# UCirKitBreadboardTop2.net
KiCad netlist of a schematic drawn in EAGLE
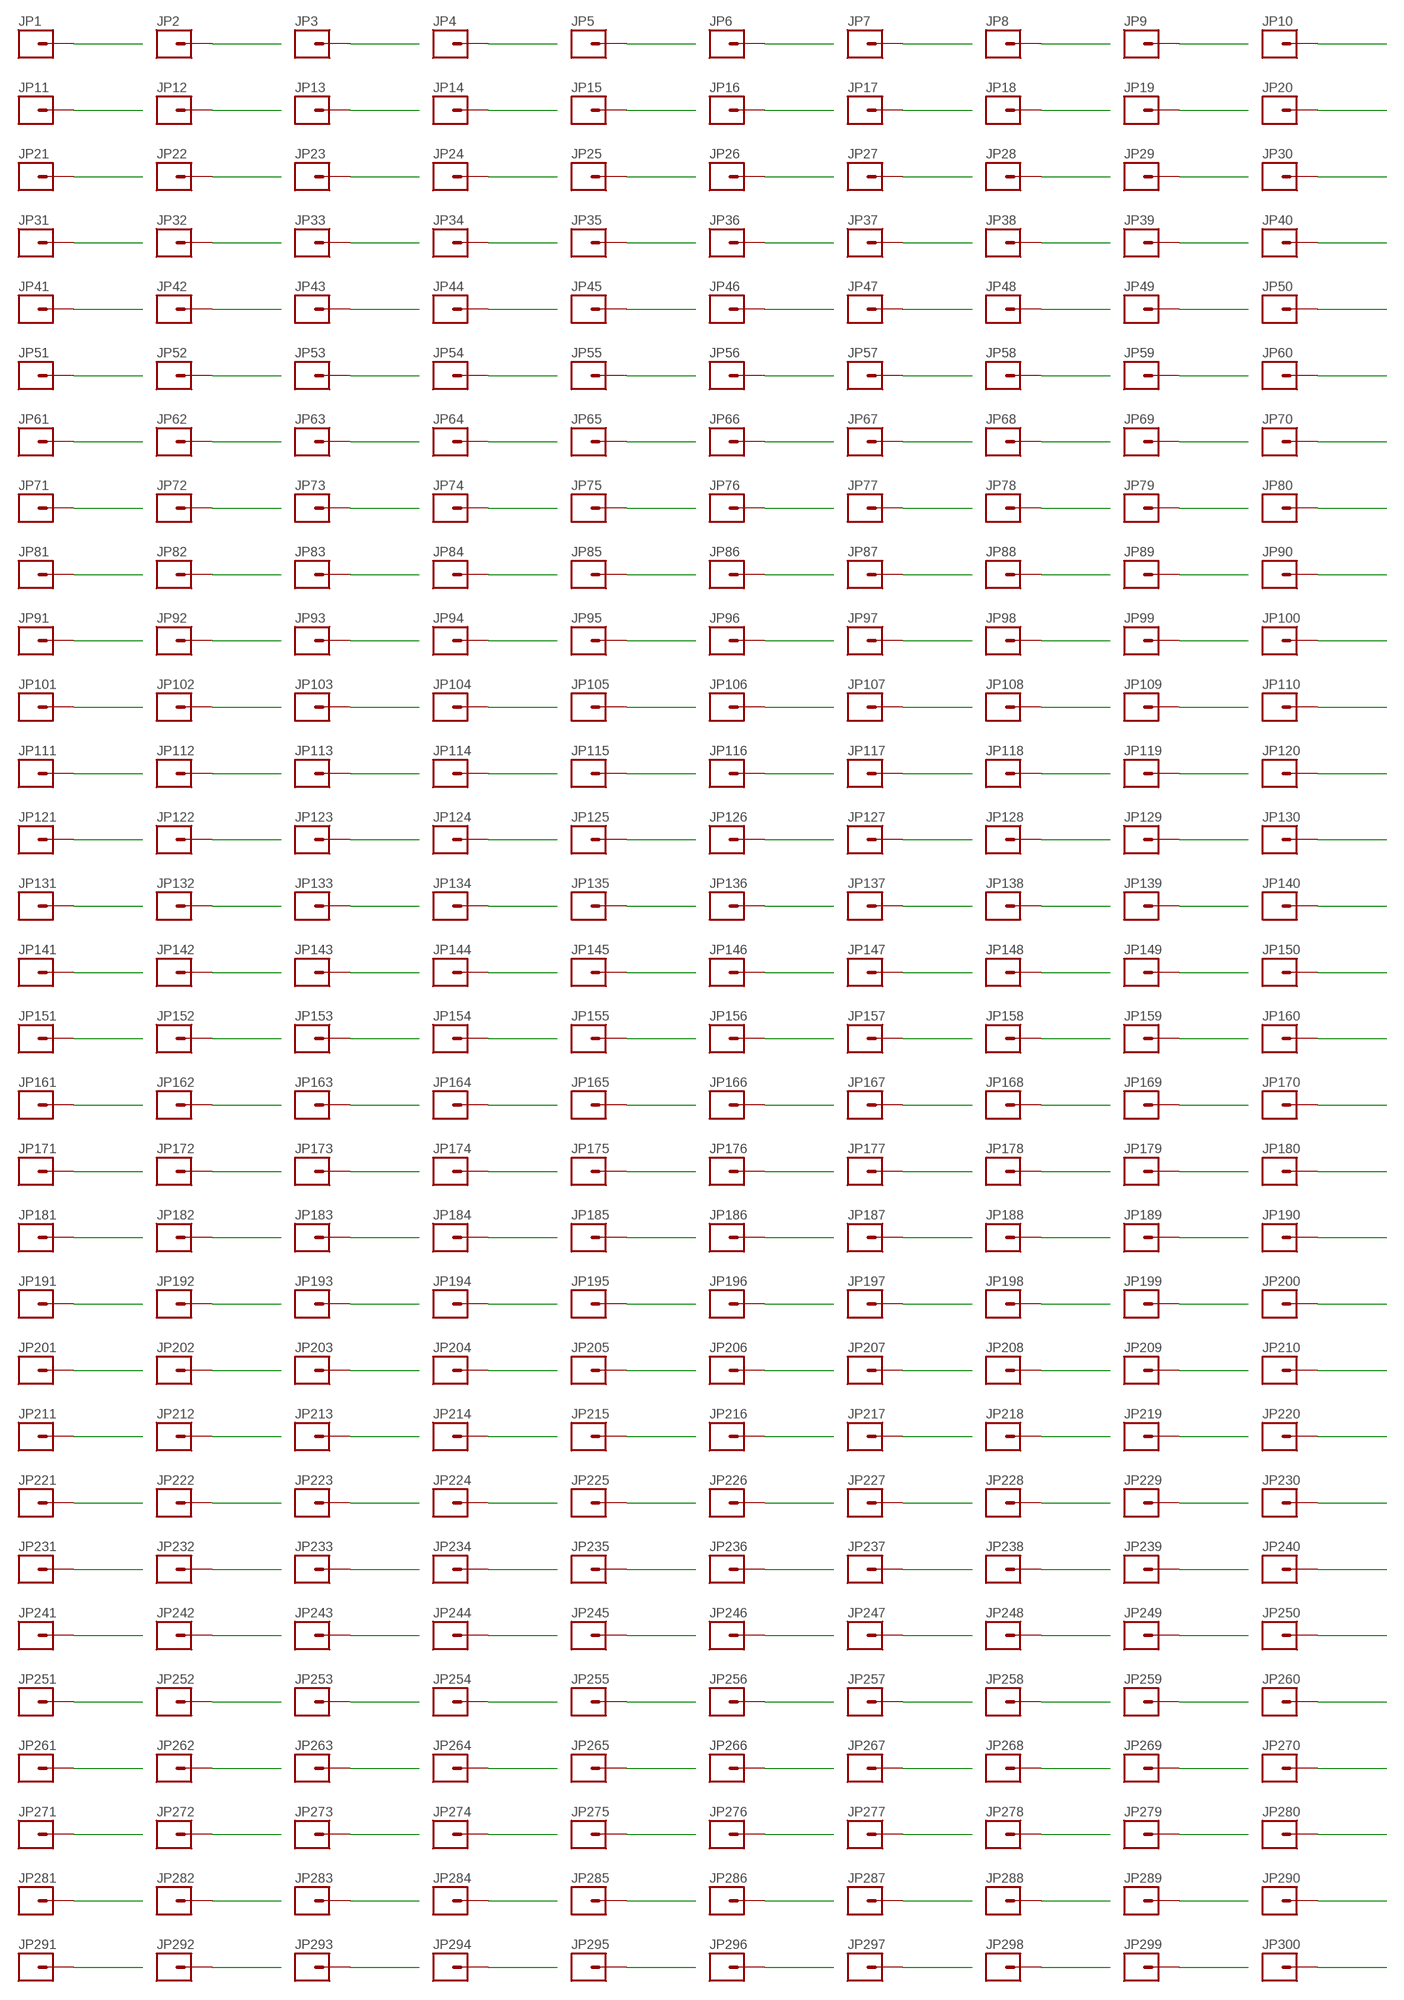
[diagram p0: schematic, sheet 1, part 1 of 2]
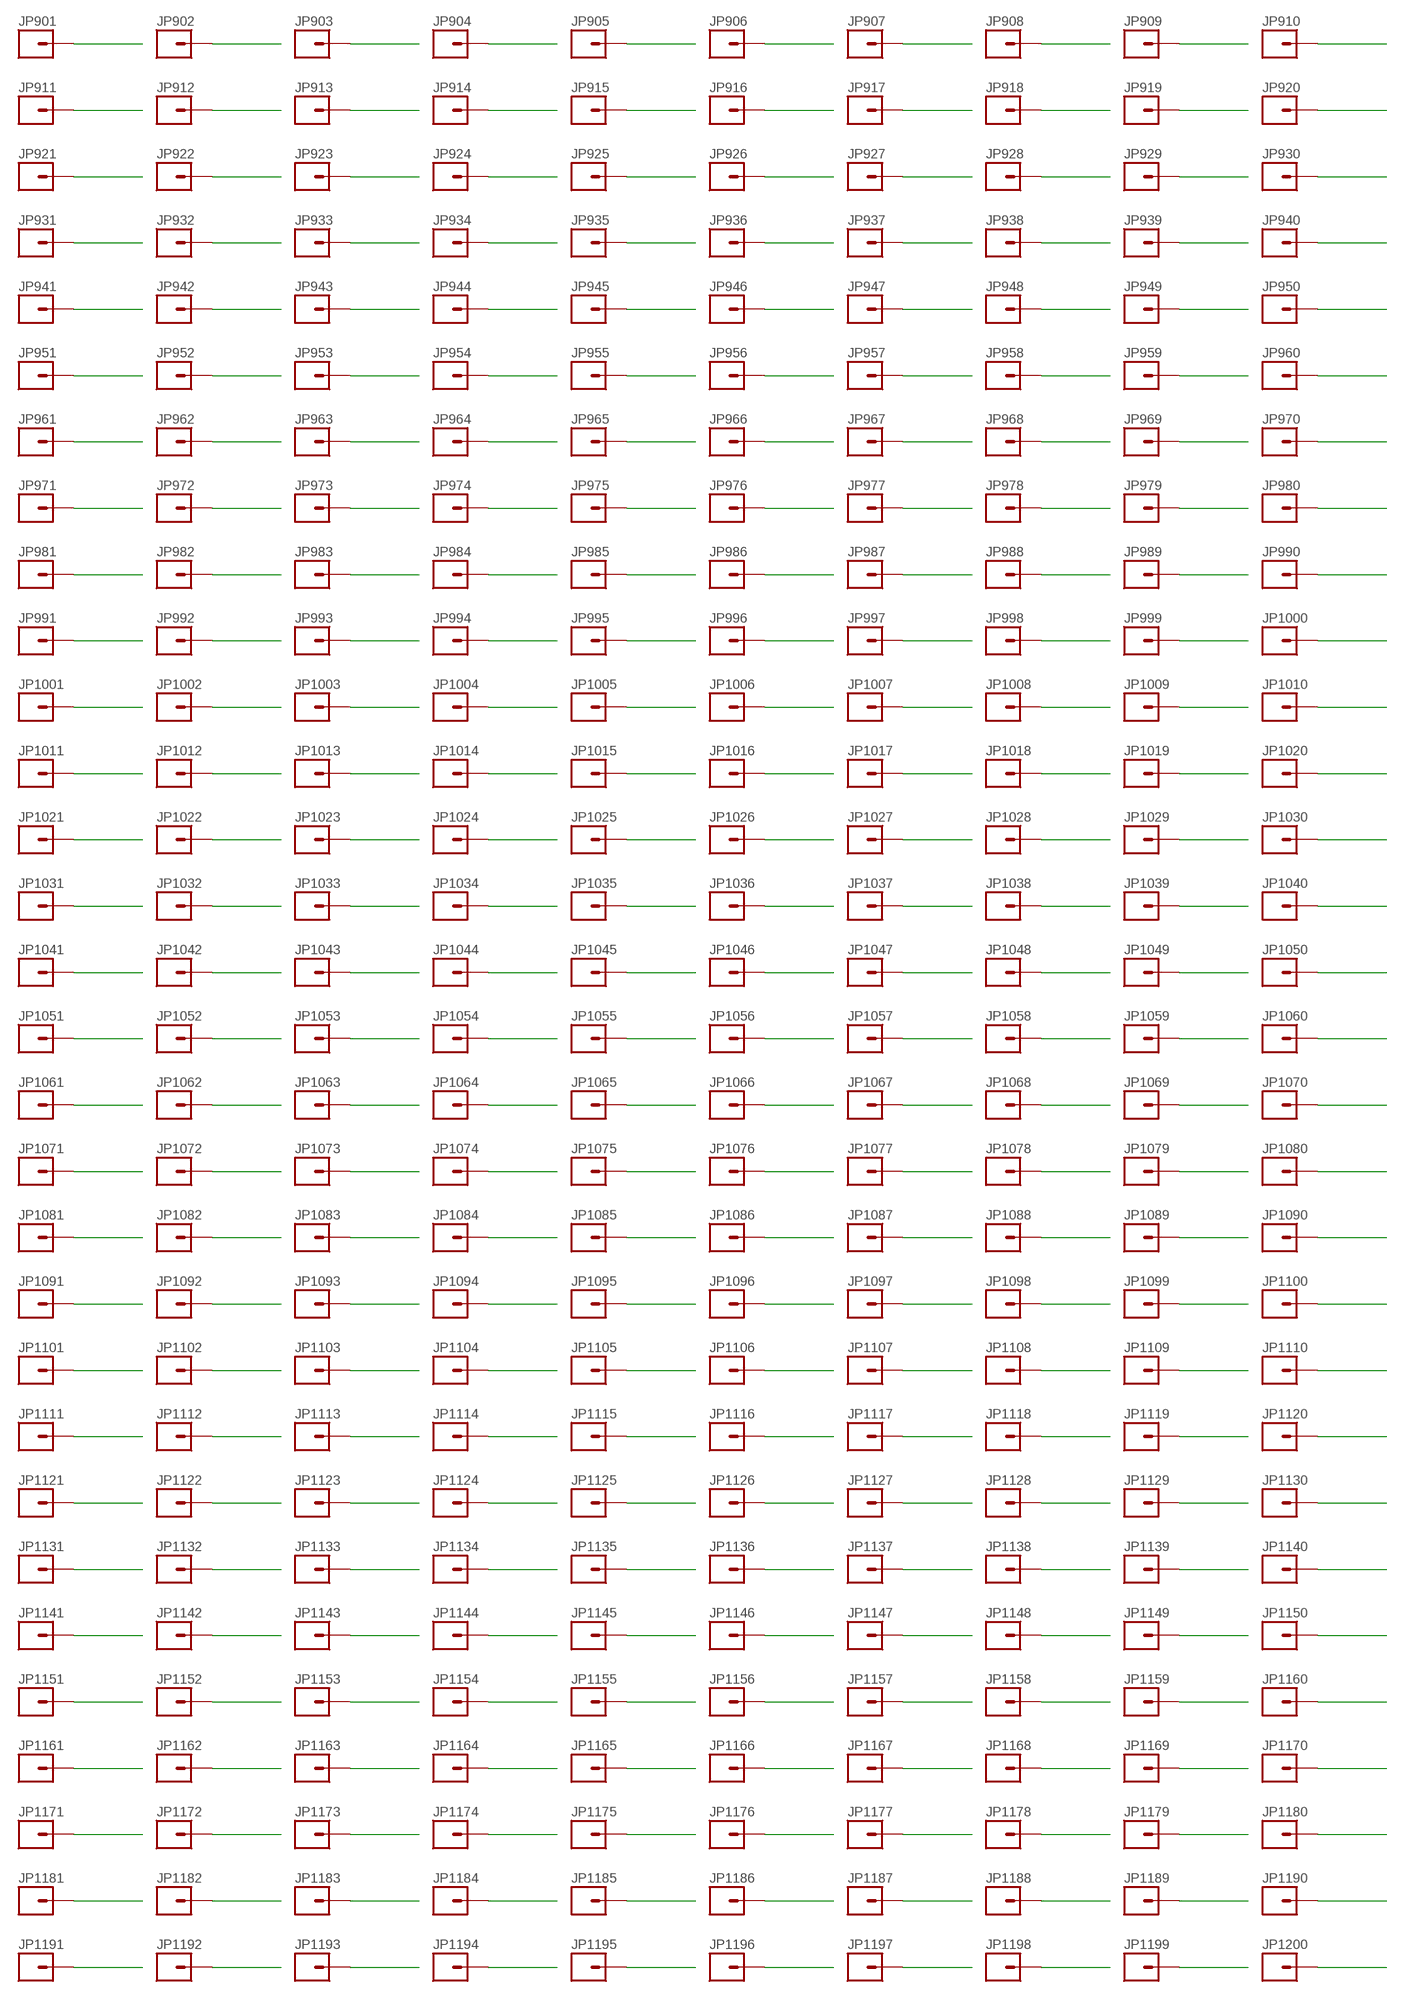
[diagram p1: schematic, sheet 1, part 2 of 2]

(export (version "E")
  (design (tool "Eeschema 10.0.6"))
  (components
    (comp (ref "JP1")
      (value "M01PTH_WITHOUT_TEXT")
      (footprint "eagle-import:1X01_WITHOUT_TEXT")
      (libsource (lib "eagle-import") (part "M01PTH_WITHOUT_TEXT"))
    )
    (comp (ref "JP2")
      (value "M01PTH_WITHOUT_TEXT")
      (footprint "eagle-import:1X01_WITHOUT_TEXT")
      (libsource (lib "eagle-import") (part "M01PTH_WITHOUT_TEXT"))
    )
    (comp (ref "JP3")
      (value "M01PTH_WITHOUT_TEXT")
      (footprint "eagle-import:1X01_WITHOUT_TEXT")
      (libsource (lib "eagle-import") (part "M01PTH_WITHOUT_TEXT"))
    )
    (comp (ref "JP4")
      (value "M01PTH_WITHOUT_TEXT")
      (footprint "eagle-import:1X01_WITHOUT_TEXT")
      (libsource (lib "eagle-import") (part "M01PTH_WITHOUT_TEXT"))
    )
    (comp (ref "JP5")
      (value "M01PTH_WITHOUT_TEXT")
      (footprint "eagle-import:1X01_WITHOUT_TEXT")
      (libsource (lib "eagle-import") (part "M01PTH_WITHOUT_TEXT"))
    )
    (comp (ref "JP6")
      (value "M01PTH_WITHOUT_TEXT")
      (footprint "eagle-import:1X01_WITHOUT_TEXT")
      (libsource (lib "eagle-import") (part "M01PTH_WITHOUT_TEXT"))
    )
    (comp (ref "JP7")
      (value "M01PTH_WITHOUT_TEXT")
      (footprint "eagle-import:1X01_WITHOUT_TEXT")
      (libsource (lib "eagle-import") (part "M01PTH_WITHOUT_TEXT"))
    )
    (comp (ref "JP8")
      (value "M01PTH_WITHOUT_TEXT")
      (footprint "eagle-import:1X01_WITHOUT_TEXT")
      (libsource (lib "eagle-import") (part "M01PTH_WITHOUT_TEXT"))
    )
    (comp (ref "JP9")
      (value "M01PTH_WITHOUT_TEXT")
      (footprint "eagle-import:1X01_WITHOUT_TEXT")
      (libsource (lib "eagle-import") (part "M01PTH_WITHOUT_TEXT"))
    )
    (comp (ref "JP10")
      (value "M01PTH_WITHOUT_TEXT")
      (footprint "eagle-import:1X01_WITHOUT_TEXT")
      (libsource (lib "eagle-import") (part "M01PTH_WITHOUT_TEXT"))
    )
    (comp (ref "JP11")
      (value "M01PTH_WITHOUT_TEXT")
      (footprint "eagle-import:1X01_WITHOUT_TEXT")
      (libsource (lib "eagle-import") (part "M01PTH_WITHOUT_TEXT"))
    )
    (comp (ref "JP12")
      (value "M01PTH_WITHOUT_TEXT")
      (footprint "eagle-import:1X01_WITHOUT_TEXT")
      (libsource (lib "eagle-import") (part "M01PTH_WITHOUT_TEXT"))
    )
    (comp (ref "JP13")
      (value "M01PTH_WITHOUT_TEXT")
      (footprint "eagle-import:1X01_WITHOUT_TEXT")
      (libsource (lib "eagle-import") (part "M01PTH_WITHOUT_TEXT"))
    )
    (comp (ref "JP14")
      (value "M01PTH_WITHOUT_TEXT")
      (footprint "eagle-import:1X01_WITHOUT_TEXT")
      (libsource (lib "eagle-import") (part "M01PTH_WITHOUT_TEXT"))
    )
    (comp (ref "JP15")
      (value "M01PTH_WITHOUT_TEXT")
      (footprint "eagle-import:1X01_WITHOUT_TEXT")
      (libsource (lib "eagle-import") (part "M01PTH_WITHOUT_TEXT"))
    )
    (comp (ref "JP16")
      (value "M01PTH_WITHOUT_TEXT")
      (footprint "eagle-import:1X01_WITHOUT_TEXT")
      (libsource (lib "eagle-import") (part "M01PTH_WITHOUT_TEXT"))
    )
    (comp (ref "JP17")
      (value "M01PTH_WITHOUT_TEXT")
      (footprint "eagle-import:1X01_WITHOUT_TEXT")
      (libsource (lib "eagle-import") (part "M01PTH_WITHOUT_TEXT"))
    )
    (comp (ref "JP18")
      (value "M01PTH_WITHOUT_TEXT")
      (footprint "eagle-import:1X01_WITHOUT_TEXT")
      (libsource (lib "eagle-import") (part "M01PTH_WITHOUT_TEXT"))
    )
    (comp (ref "JP19")
      (value "M01PTH_WITHOUT_TEXT")
      (footprint "eagle-import:1X01_WITHOUT_TEXT")
      (libsource (lib "eagle-import") (part "M01PTH_WITHOUT_TEXT"))
    )
    (comp (ref "JP20")
      (value "M01PTH_WITHOUT_TEXT")
      (footprint "eagle-import:1X01_WITHOUT_TEXT")
      (libsource (lib "eagle-import") (part "M01PTH_WITHOUT_TEXT"))
    )
    (comp (ref "JP21")
      (value "M01PTH_WITHOUT_TEXT")
      (footprint "eagle-import:1X01_WITHOUT_TEXT")
      (libsource (lib "eagle-import") (part "M01PTH_WITHOUT_TEXT"))
    )
    (comp (ref "JP22")
      (value "M01PTH_WITHOUT_TEXT")
      (footprint "eagle-import:1X01_WITHOUT_TEXT")
      (libsource (lib "eagle-import") (part "M01PTH_WITHOUT_TEXT"))
    )
    (comp (ref "JP23")
      (value "M01PTH_WITHOUT_TEXT")
      (footprint "eagle-import:1X01_WITHOUT_TEXT")
      (libsource (lib "eagle-import") (part "M01PTH_WITHOUT_TEXT"))
    )
    (comp (ref "JP24")
      (value "M01PTH_WITHOUT_TEXT")
      (footprint "eagle-import:1X01_WITHOUT_TEXT")
      (libsource (lib "eagle-import") (part "M01PTH_WITHOUT_TEXT"))
    )
    (comp (ref "JP25")
      (value "M01PTH_WITHOUT_TEXT")
      (footprint "eagle-import:1X01_WITHOUT_TEXT")
      (libsource (lib "eagle-import") (part "M01PTH_WITHOUT_TEXT"))
    )
    (comp (ref "JP26")
      (value "M01PTH_WITHOUT_TEXT")
      (footprint "eagle-import:1X01_WITHOUT_TEXT")
      (libsource (lib "eagle-import") (part "M01PTH_WITHOUT_TEXT"))
    )
    (comp (ref "JP27")
      (value "M01PTH_WITHOUT_TEXT")
      (footprint "eagle-import:1X01_WITHOUT_TEXT")
      (libsource (lib "eagle-import") (part "M01PTH_WITHOUT_TEXT"))
    )
    (comp (ref "JP28")
      (value "M01PTH_WITHOUT_TEXT")
      (footprint "eagle-import:1X01_WITHOUT_TEXT")
      (libsource (lib "eagle-import") (part "M01PTH_WITHOUT_TEXT"))
    )
    (comp (ref "JP29")
      (value "M01PTH_WITHOUT_TEXT")
      (footprint "eagle-import:1X01_WITHOUT_TEXT")
      (libsource (lib "eagle-import") (part "M01PTH_WITHOUT_TEXT"))
    )
    (comp (ref "JP30")
      (value "M01PTH_WITHOUT_TEXT")
      (footprint "eagle-import:1X01_WITHOUT_TEXT")
      (libsource (lib "eagle-import") (part "M01PTH_WITHOUT_TEXT"))
    )
    (comp (ref "JP31")
      (value "M01PTH_WITHOUT_TEXT")
      (footprint "eagle-import:1X01_WITHOUT_TEXT")
      (libsource (lib "eagle-import") (part "M01PTH_WITHOUT_TEXT"))
    )
    (comp (ref "JP32")
      (value "M01PTH_WITHOUT_TEXT")
      (footprint "eagle-import:1X01_WITHOUT_TEXT")
      (libsource (lib "eagle-import") (part "M01PTH_WITHOUT_TEXT"))
    )
    (comp (ref "JP33")
      (value "M01PTH_WITHOUT_TEXT")
      (footprint "eagle-import:1X01_WITHOUT_TEXT")
      (libsource (lib "eagle-import") (part "M01PTH_WITHOUT_TEXT"))
    )
    (comp (ref "JP34")
      (value "M01PTH_WITHOUT_TEXT")
      (footprint "eagle-import:1X01_WITHOUT_TEXT")
      (libsource (lib "eagle-import") (part "M01PTH_WITHOUT_TEXT"))
    )
    (comp (ref "JP35")
      (value "M01PTH_WITHOUT_TEXT")
      (footprint "eagle-import:1X01_WITHOUT_TEXT")
      (libsource (lib "eagle-import") (part "M01PTH_WITHOUT_TEXT"))
    )
    (comp (ref "JP36")
      (value "M01PTH_WITHOUT_TEXT")
      (footprint "eagle-import:1X01_WITHOUT_TEXT")
      (libsource (lib "eagle-import") (part "M01PTH_WITHOUT_TEXT"))
    )
    (comp (ref "JP37")
      (value "M01PTH_WITHOUT_TEXT")
      (footprint "eagle-import:1X01_WITHOUT_TEXT")
      (libsource (lib "eagle-import") (part "M01PTH_WITHOUT_TEXT"))
    )
    (comp (ref "JP38")
      (value "M01PTH_WITHOUT_TEXT")
      (footprint "eagle-import:1X01_WITHOUT_TEXT")
      (libsource (lib "eagle-import") (part "M01PTH_WITHOUT_TEXT"))
    )
    (comp (ref "JP39")
      (value "M01PTH_WITHOUT_TEXT")
      (footprint "eagle-import:1X01_WITHOUT_TEXT")
      (libsource (lib "eagle-import") (part "M01PTH_WITHOUT_TEXT"))
    )
    (comp (ref "JP40")
      (value "M01PTH_WITHOUT_TEXT")
      (footprint "eagle-import:1X01_WITHOUT_TEXT")
      (libsource (lib "eagle-import") (part "M01PTH_WITHOUT_TEXT"))
    )
    (comp (ref "JP41")
      (value "M01PTH_WITHOUT_TEXT")
      (footprint "eagle-import:1X01_WITHOUT_TEXT")
      (libsource (lib "eagle-import") (part "M01PTH_WITHOUT_TEXT"))
    )
    (comp (ref "JP42")
      (value "M01PTH_WITHOUT_TEXT")
      (footprint "eagle-import:1X01_WITHOUT_TEXT")
      (libsource (lib "eagle-import") (part "M01PTH_WITHOUT_TEXT"))
    )
    (comp (ref "JP43")
      (value "M01PTH_WITHOUT_TEXT")
      (footprint "eagle-import:1X01_WITHOUT_TEXT")
      (libsource (lib "eagle-import") (part "M01PTH_WITHOUT_TEXT"))
    )
    (comp (ref "JP44")
      (value "M01PTH_WITHOUT_TEXT")
      (footprint "eagle-import:1X01_WITHOUT_TEXT")
      (libsource (lib "eagle-import") (part "M01PTH_WITHOUT_TEXT"))
    )
    (comp (ref "JP45")
      (value "M01PTH_WITHOUT_TEXT")
      (footprint "eagle-import:1X01_WITHOUT_TEXT")
      (libsource (lib "eagle-import") (part "M01PTH_WITHOUT_TEXT"))
    )
    (comp (ref "JP46")
      (value "M01PTH_WITHOUT_TEXT")
      (footprint "eagle-import:1X01_WITHOUT_TEXT")
      (libsource (lib "eagle-import") (part "M01PTH_WITHOUT_TEXT"))
    )
    (comp (ref "JP47")
      (value "M01PTH_WITHOUT_TEXT")
      (footprint "eagle-import:1X01_WITHOUT_TEXT")
      (libsource (lib "eagle-import") (part "M01PTH_WITHOUT_TEXT"))
    )
    (comp (ref "JP48")
      (value "M01PTH_WITHOUT_TEXT")
      (footprint "eagle-import:1X01_WITHOUT_TEXT")
      (libsource (lib "eagle-import") (part "M01PTH_WITHOUT_TEXT"))
    )
    (comp (ref "JP49")
      (value "M01PTH_WITHOUT_TEXT")
      (footprint "eagle-import:1X01_WITHOUT_TEXT")
      (libsource (lib "eagle-import") (part "M01PTH_WITHOUT_TEXT"))
    )
    (comp (ref "JP50")
      (value "M01PTH_WITHOUT_TEXT")
      (footprint "eagle-import:1X01_WITHOUT_TEXT")
      (libsource (lib "eagle-import") (part "M01PTH_WITHOUT_TEXT"))
    )
    (comp (ref "JP51")
      (value "M01PTH_WITHOUT_TEXT")
      (footprint "eagle-import:1X01_WITHOUT_TEXT")
      (libsource (lib "eagle-import") (part "M01PTH_WITHOUT_TEXT"))
    )
    (comp (ref "JP52")
      (value "M01PTH_WITHOUT_TEXT")
      (footprint "eagle-import:1X01_WITHOUT_TEXT")
      (libsource (lib "eagle-import") (part "M01PTH_WITHOUT_TEXT"))
    )
    (comp (ref "JP53")
      (value "M01PTH_WITHOUT_TEXT")
      (footprint "eagle-import:1X01_WITHOUT_TEXT")
      (libsource (lib "eagle-import") (part "M01PTH_WITHOUT_TEXT"))
    )
    (comp (ref "JP54")
      (value "M01PTH_WITHOUT_TEXT")
      (footprint "eagle-import:1X01_WITHOUT_TEXT")
      (libsource (lib "eagle-import") (part "M01PTH_WITHOUT_TEXT"))
    )
    (comp (ref "JP55")
      (value "M01PTH_WITHOUT_TEXT")
      (footprint "eagle-import:1X01_WITHOUT_TEXT")
      (libsource (lib "eagle-import") (part "M01PTH_WITHOUT_TEXT"))
    )
    (comp (ref "JP56")
      (value "M01PTH_WITHOUT_TEXT")
      (footprint "eagle-import:1X01_WITHOUT_TEXT")
      (libsource (lib "eagle-import") (part "M01PTH_WITHOUT_TEXT"))
    )
    (comp (ref "JP57")
      (value "M01PTH_WITHOUT_TEXT")
      (footprint "eagle-import:1X01_WITHOUT_TEXT")
      (libsource (lib "eagle-import") (part "M01PTH_WITHOUT_TEXT"))
    )
    (comp (ref "JP58")
      (value "M01PTH_WITHOUT_TEXT")
      (footprint "eagle-import:1X01_WITHOUT_TEXT")
      (libsource (lib "eagle-import") (part "M01PTH_WITHOUT_TEXT"))
    )
    (comp (ref "JP59")
      (value "M01PTH_WITHOUT_TEXT")
      (footprint "eagle-import:1X01_WITHOUT_TEXT")
      (libsource (lib "eagle-import") (part "M01PTH_WITHOUT_TEXT"))
    )
    (comp (ref "JP60")
      (value "M01PTH_WITHOUT_TEXT")
      (footprint "eagle-import:1X01_WITHOUT_TEXT")
      (libsource (lib "eagle-import") (part "M01PTH_WITHOUT_TEXT"))
    )
    (comp (ref "JP61")
      (value "M01PTH_WITHOUT_TEXT")
      (footprint "eagle-import:1X01_WITHOUT_TEXT")
      (libsource (lib "eagle-import") (part "M01PTH_WITHOUT_TEXT"))
    )
    (comp (ref "JP62")
      (value "M01PTH_WITHOUT_TEXT")
      (footprint "eagle-import:1X01_WITHOUT_TEXT")
      (libsource (lib "eagle-import") (part "M01PTH_WITHOUT_TEXT"))
    )
    (comp (ref "JP63")
      (value "M01PTH_WITHOUT_TEXT")
      (footprint "eagle-import:1X01_WITHOUT_TEXT")
      (libsource (lib "eagle-import") (part "M01PTH_WITHOUT_TEXT"))
    )
    (comp (ref "JP64")
      (value "M01PTH_WITHOUT_TEXT")
      (footprint "eagle-import:1X01_WITHOUT_TEXT")
      (libsource (lib "eagle-import") (part "M01PTH_WITHOUT_TEXT"))
    )
    (comp (ref "JP65")
      (value "M01PTH_WITHOUT_TEXT")
      (footprint "eagle-import:1X01_WITHOUT_TEXT")
      (libsource (lib "eagle-import") (part "M01PTH_WITHOUT_TEXT"))
    )
    (comp (ref "JP66")
      (value "M01PTH_WITHOUT_TEXT")
      (footprint "eagle-import:1X01_WITHOUT_TEXT")
      (libsource (lib "eagle-import") (part "M01PTH_WITHOUT_TEXT"))
    )
    (comp (ref "JP67")
      (value "M01PTH_WITHOUT_TEXT")
      (footprint "eagle-import:1X01_WITHOUT_TEXT")
      (libsource (lib "eagle-import") (part "M01PTH_WITHOUT_TEXT"))
    )
    (comp (ref "JP68")
      (value "M01PTH_WITHOUT_TEXT")
      (footprint "eagle-import:1X01_WITHOUT_TEXT")
      (libsource (lib "eagle-import") (part "M01PTH_WITHOUT_TEXT"))
    )
    (comp (ref "JP69")
      (value "M01PTH_WITHOUT_TEXT")
      (footprint "eagle-import:1X01_WITHOUT_TEXT")
      (libsource (lib "eagle-import") (part "M01PTH_WITHOUT_TEXT"))
    )
    (comp (ref "JP70")
      (value "M01PTH_WITHOUT_TEXT")
      (footprint "eagle-import:1X01_WITHOUT_TEXT")
      (libsource (lib "eagle-import") (part "M01PTH_WITHOUT_TEXT"))
    )
    (comp (ref "JP71")
      (value "M01PTH_WITHOUT_TEXT")
      (footprint "eagle-import:1X01_WITHOUT_TEXT")
      (libsource (lib "eagle-import") (part "M01PTH_WITHOUT_TEXT"))
    )
    (comp (ref "JP72")
      (value "M01PTH_WITHOUT_TEXT")
      (footprint "eagle-import:1X01_WITHOUT_TEXT")
      (libsource (lib "eagle-import") (part "M01PTH_WITHOUT_TEXT"))
    )
    (comp (ref "JP73")
      (value "M01PTH_WITHOUT_TEXT")
      (footprint "eagle-import:1X01_WITHOUT_TEXT")
      (libsource (lib "eagle-import") (part "M01PTH_WITHOUT_TEXT"))
    )
    (comp (ref "JP74")
      (value "M01PTH_WITHOUT_TEXT")
      (footprint "eagle-import:1X01_WITHOUT_TEXT")
      (libsource (lib "eagle-import") (part "M01PTH_WITHOUT_TEXT"))
    )
    (comp (ref "JP75")
      (value "M01PTH_WITHOUT_TEXT")
      (footprint "eagle-import:1X01_WITHOUT_TEXT")
      (libsource (lib "eagle-import") (part "M01PTH_WITHOUT_TEXT"))
    )
    (comp (ref "JP76")
      (value "M01PTH_WITHOUT_TEXT")
      (footprint "eagle-import:1X01_WITHOUT_TEXT")
      (libsource (lib "eagle-import") (part "M01PTH_WITHOUT_TEXT"))
    )
    (comp (ref "JP77")
      (value "M01PTH_WITHOUT_TEXT")
      (footprint "eagle-import:1X01_WITHOUT_TEXT")
      (libsource (lib "eagle-import") (part "M01PTH_WITHOUT_TEXT"))
    )
    (comp (ref "JP78")
      (value "M01PTH_WITHOUT_TEXT")
      (footprint "eagle-import:1X01_WITHOUT_TEXT")
      (libsource (lib "eagle-import") (part "M01PTH_WITHOUT_TEXT"))
    )
    (comp (ref "JP79")
      (value "M01PTH_WITHOUT_TEXT")
      (footprint "eagle-import:1X01_WITHOUT_TEXT")
      (libsource (lib "eagle-import") (part "M01PTH_WITHOUT_TEXT"))
    )
    (comp (ref "JP80")
      (value "M01PTH_WITHOUT_TEXT")
      (footprint "eagle-import:1X01_WITHOUT_TEXT")
      (libsource (lib "eagle-import") (part "M01PTH_WITHOUT_TEXT"))
    )
    (comp (ref "JP81")
      (value "M01PTH_WITHOUT_TEXT")
      (footprint "eagle-import:1X01_WITHOUT_TEXT")
      (libsource (lib "eagle-import") (part "M01PTH_WITHOUT_TEXT"))
    )
    (comp (ref "JP82")
      (value "M01PTH_WITHOUT_TEXT")
      (footprint "eagle-import:1X01_WITHOUT_TEXT")
      (libsource (lib "eagle-import") (part "M01PTH_WITHOUT_TEXT"))
    )
    (comp (ref "JP83")
      (value "M01PTH_WITHOUT_TEXT")
      (footprint "eagle-import:1X01_WITHOUT_TEXT")
      (libsource (lib "eagle-import") (part "M01PTH_WITHOUT_TEXT"))
    )
    (comp (ref "JP84")
      (value "M01PTH_WITHOUT_TEXT")
      (footprint "eagle-import:1X01_WITHOUT_TEXT")
      (libsource (lib "eagle-import") (part "M01PTH_WITHOUT_TEXT"))
    )
    (comp (ref "JP85")
      (value "M01PTH_WITHOUT_TEXT")
      (footprint "eagle-import:1X01_WITHOUT_TEXT")
      (libsource (lib "eagle-import") (part "M01PTH_WITHOUT_TEXT"))
    )
    (comp (ref "JP86")
      (value "M01PTH_WITHOUT_TEXT")
      (footprint "eagle-import:1X01_WITHOUT_TEXT")
      (libsource (lib "eagle-import") (part "M01PTH_WITHOUT_TEXT"))
    )
    (comp (ref "JP87")
      (value "M01PTH_WITHOUT_TEXT")
      (footprint "eagle-import:1X01_WITHOUT_TEXT")
      (libsource (lib "eagle-import") (part "M01PTH_WITHOUT_TEXT"))
    )
    (comp (ref "JP88")
      (value "M01PTH_WITHOUT_TEXT")
      (footprint "eagle-import:1X01_WITHOUT_TEXT")
      (libsource (lib "eagle-import") (part "M01PTH_WITHOUT_TEXT"))
    )
    (comp (ref "JP89")
      (value "M01PTH_WITHOUT_TEXT")
      (footprint "eagle-import:1X01_WITHOUT_TEXT")
      (libsource (lib "eagle-import") (part "M01PTH_WITHOUT_TEXT"))
    )
    (comp (ref "JP90")
      (value "M01PTH_WITHOUT_TEXT")
      (footprint "eagle-import:1X01_WITHOUT_TEXT")
      (libsource (lib "eagle-import") (part "M01PTH_WITHOUT_TEXT"))
    )
    (comp (ref "JP91")
      (value "M01PTH_WITHOUT_TEXT")
      (footprint "eagle-import:1X01_WITHOUT_TEXT")
      (libsource (lib "eagle-import") (part "M01PTH_WITHOUT_TEXT"))
    )
    (comp (ref "JP92")
      (value "M01PTH_WITHOUT_TEXT")
      (footprint "eagle-import:1X01_WITHOUT_TEXT")
      (libsource (lib "eagle-import") (part "M01PTH_WITHOUT_TEXT"))
    )
    (comp (ref "JP93")
      (value "M01PTH_WITHOUT_TEXT")
      (footprint "eagle-import:1X01_WITHOUT_TEXT")
      (libsource (lib "eagle-import") (part "M01PTH_WITHOUT_TEXT"))
    )
    (comp (ref "JP94")
      (value "M01PTH_WITHOUT_TEXT")
      (footprint "eagle-import:1X01_WITHOUT_TEXT")
      (libsource (lib "eagle-import") (part "M01PTH_WITHOUT_TEXT"))
    )
    (comp (ref "JP95")
      (value "M01PTH_WITHOUT_TEXT")
      (footprint "eagle-import:1X01_WITHOUT_TEXT")
      (libsource (lib "eagle-import") (part "M01PTH_WITHOUT_TEXT"))
    )
    (comp (ref "JP96")
      (value "M01PTH_WITHOUT_TEXT")
      (footprint "eagle-import:1X01_WITHOUT_TEXT")
      (libsource (lib "eagle-import") (part "M01PTH_WITHOUT_TEXT"))
    )
    (comp (ref "JP97")
      (value "M01PTH_WITHOUT_TEXT")
      (footprint "eagle-import:1X01_WITHOUT_TEXT")
      (libsource (lib "eagle-import") (part "M01PTH_WITHOUT_TEXT"))
    )
    (comp (ref "JP98")
      (value "M01PTH_WITHOUT_TEXT")
      (footprint "eagle-import:1X01_WITHOUT_TEXT")
      (libsource (lib "eagle-import") (part "M01PTH_WITHOUT_TEXT"))
    )
    (comp (ref "JP99")
      (value "M01PTH_WITHOUT_TEXT")
      (footprint "eagle-import:1X01_WITHOUT_TEXT")
      (libsource (lib "eagle-import") (part "M01PTH_WITHOUT_TEXT"))
    )
    (comp (ref "JP100")
      (value "M01PTH_WITHOUT_TEXT")
      (footprint "eagle-import:1X01_WITHOUT_TEXT")
      (libsource (lib "eagle-import") (part "M01PTH_WITHOUT_TEXT"))
    )
    (comp (ref "JP101")
      (value "M01PTH_WITHOUT_TEXT")
      (footprint "eagle-import:1X01_WITHOUT_TEXT")
      (libsource (lib "eagle-import") (part "M01PTH_WITHOUT_TEXT"))
    )
    (comp (ref "JP102")
      (value "M01PTH_WITHOUT_TEXT")
      (footprint "eagle-import:1X01_WITHOUT_TEXT")
      (libsource (lib "eagle-import") (part "M01PTH_WITHOUT_TEXT"))
    )
    (comp (ref "JP103")
      (value "M01PTH_WITHOUT_TEXT")
      (footprint "eagle-import:1X01_WITHOUT_TEXT")
      (libsource (lib "eagle-import") (part "M01PTH_WITHOUT_TEXT"))
    )
    (comp (ref "JP104")
      (value "M01PTH_WITHOUT_TEXT")
      (footprint "eagle-import:1X01_WITHOUT_TEXT")
      (libsource (lib "eagle-import") (part "M01PTH_WITHOUT_TEXT"))
    )
    (comp (ref "JP105")
      (value "M01PTH_WITHOUT_TEXT")
      (footprint "eagle-import:1X01_WITHOUT_TEXT")
      (libsource (lib "eagle-import") (part "M01PTH_WITHOUT_TEXT"))
    )
    (comp (ref "JP106")
      (value "M01PTH_WITHOUT_TEXT")
      (footprint "eagle-import:1X01_WITHOUT_TEXT")
      (libsource (lib "eagle-import") (part "M01PTH_WITHOUT_TEXT"))
    )
    (comp (ref "JP107")
      (value "M01PTH_WITHOUT_TEXT")
      (footprint "eagle-import:1X01_WITHOUT_TEXT")
      (libsource (lib "eagle-import") (part "M01PTH_WITHOUT_TEXT"))
    )
    (comp (ref "JP108")
      (value "M01PTH_WITHOUT_TEXT")
      (footprint "eagle-import:1X01_WITHOUT_TEXT")
      (libsource (lib "eagle-import") (part "M01PTH_WITHOUT_TEXT"))
    )
    (comp (ref "JP109")
      (value "M01PTH_WITHOUT_TEXT")
      (footprint "eagle-import:1X01_WITHOUT_TEXT")
      (libsource (lib "eagle-import") (part "M01PTH_WITHOUT_TEXT"))
    )
    (comp (ref "JP110")
      (value "M01PTH_WITHOUT_TEXT")
      (footprint "eagle-import:1X01_WITHOUT_TEXT")
      (libsource (lib "eagle-import") (part "M01PTH_WITHOUT_TEXT"))
    )
    (comp (ref "JP111")
      (value "M01PTH_WITHOUT_TEXT")
      (footprint "eagle-import:1X01_WITHOUT_TEXT")
      (libsource (lib "eagle-import") (part "M01PTH_WITHOUT_TEXT"))
    )
    (comp (ref "JP112")
      (value "M01PTH_WITHOUT_TEXT")
      (footprint "eagle-import:1X01_WITHOUT_TEXT")
      (libsource (lib "eagle-import") (part "M01PTH_WITHOUT_TEXT"))
    )
    (comp (ref "JP113")
      (value "M01PTH_WITHOUT_TEXT")
      (footprint "eagle-import:1X01_WITHOUT_TEXT")
      (libsource (lib "eagle-import") (part "M01PTH_WITHOUT_TEXT"))
    )
    (comp (ref "JP114")
      (value "M01PTH_WITHOUT_TEXT")
      (footprint "eagle-import:1X01_WITHOUT_TEXT")
      (libsource (lib "eagle-import") (part "M01PTH_WITHOUT_TEXT"))
    )
    (comp (ref "JP115")
      (value "M01PTH_WITHOUT_TEXT")
      (footprint "eagle-import:1X01_WITHOUT_TEXT")
      (libsource (lib "eagle-import") (part "M01PTH_WITHOUT_TEXT"))
    )
    (comp (ref "JP116")
      (value "M01PTH_WITHOUT_TEXT")
      (footprint "eagle-import:1X01_WITHOUT_TEXT")
      (libsource (lib "eagle-import") (part "M01PTH_WITHOUT_TEXT"))
    )
    (comp (ref "JP117")
      (value "M01PTH_WITHOUT_TEXT")
      (footprint "eagle-import:1X01_WITHOUT_TEXT")
      (libsource (lib "eagle-import") (part "M01PTH_WITHOUT_TEXT"))
    )
    (comp (ref "JP118")
      (value "M01PTH_WITHOUT_TEXT")
      (footprint "eagle-import:1X01_WITHOUT_TEXT")
      (libsource (lib "eagle-import") (part "M01PTH_WITHOUT_TEXT"))
    )
    (comp (ref "JP119")
      (value "M01PTH_WITHOUT_TEXT")
      (footprint "eagle-import:1X01_WITHOUT_TEXT")
      (libsource (lib "eagle-import") (part "M01PTH_WITHOUT_TEXT"))
    )
    (comp (ref "JP120")
      (value "M01PTH_WITHOUT_TEXT")
      (footprint "eagle-import:1X01_WITHOUT_TEXT")
      (libsource (lib "eagle-import") (part "M01PTH_WITHOUT_TEXT"))
    )
    (comp (ref "JP121")
      (value "M01PTH_WITHOUT_TEXT")
      (footprint "eagle-import:1X01_WITHOUT_TEXT")
      (libsource (lib "eagle-import") (part "M01PTH_WITHOUT_TEXT"))
    )
    (comp (ref "JP122")
      (value "M01PTH_WITHOUT_TEXT")
      (footprint "eagle-import:1X01_WITHOUT_TEXT")
      (libsource (lib "eagle-import") (part "M01PTH_WITHOUT_TEXT"))
    )
    (comp (ref "JP123")
      (value "M01PTH_WITHOUT_TEXT")
      (footprint "eagle-import:1X01_WITHOUT_TEXT")
      (libsource (lib "eagle-import") (part "M01PTH_WITHOUT_TEXT"))
    )
    (comp (ref "JP124")
      (value "M01PTH_WITHOUT_TEXT")
      (footprint "eagle-import:1X01_WITHOUT_TEXT")
      (libsource (lib "eagle-import") (part "M01PTH_WITHOUT_TEXT"))
    )
    (comp (ref "JP125")
      (value "M01PTH_WITHOUT_TEXT")
      (footprint "eagle-import:1X01_WITHOUT_TEXT")
      (libsource (lib "eagle-import") (part "M01PTH_WITHOUT_TEXT"))
    )
    (comp (ref "JP126")
      (value "M01PTH_WITHOUT_TEXT")
      (footprint "eagle-import:1X01_WITHOUT_TEXT")
      (libsource (lib "eagle-import") (part "M01PTH_WITHOUT_TEXT"))
    )
    (comp (ref "JP127")
      (value "M01PTH_WITHOUT_TEXT")
      (footprint "eagle-import:1X01_WITHOUT_TEXT")
      (libsource (lib "eagle-import") (part "M01PTH_WITHOUT_TEXT"))
    )
    (comp (ref "JP128")
      (value "M01PTH_WITHOUT_TEXT")
      (footprint "eagle-import:1X01_WITHOUT_TEXT")
      (libsource (lib "eagle-import") (part "M01PTH_WITHOUT_TEXT"))
    )
    (comp (ref "JP129")
      (value "M01PTH_WITHOUT_TEXT")
      (footprint "eagle-import:1X01_WITHOUT_TEXT")
      (libsource (lib "eagle-import") (part "M01PTH_WITHOUT_TEXT"))
    )
    (comp (ref "JP130")
      (value "M01PTH_WITHOUT_TEXT")
      (footprint "eagle-import:1X01_WITHOUT_TEXT")
      (libsource (lib "eagle-import") (part "M01PTH_WITHOUT_TEXT"))
    )
    (comp (ref "JP131")
      (value "M01PTH_WITHOUT_TEXT")
      (footprint "eagle-import:1X01_WITHOUT_TEXT")
      (libsource (lib "eagle-import") (part "M01PTH_WITHOUT_TEXT"))
    )
    (comp (ref "JP132")
      (value "M01PTH_WITHOUT_TEXT")
      (footprint "eagle-import:1X01_WITHOUT_TEXT")
      (libsource (lib "eagle-import") (part "M01PTH_WITHOUT_TEXT"))
    )
    (comp (ref "JP133")
      (value "M01PTH_WITHOUT_TEXT")
      (footprint "eagle-import:1X01_WITHOUT_TEXT")
      (libsource (lib "eagle-import") (part "M01PTH_WITHOUT_TEXT"))
    )
    (comp (ref "JP134")
      (value "M01PTH_WITHOUT_TEXT")
      (footprint "eagle-import:1X01_WITHOUT_TEXT")
      (libsource (lib "eagle-import") (part "M01PTH_WITHOUT_TEXT"))
    )
    (comp (ref "JP135")
      (value "M01PTH_WITHOUT_TEXT")
      (footprint "eagle-import:1X01_WITHOUT_TEXT")
      (libsource (lib "eagle-import") (part "M01PTH_WITHOUT_TEXT"))
    )
    (comp (ref "JP136")
      (value "M01PTH_WITHOUT_TEXT")
      (footprint "eagle-import:1X01_WITHOUT_TEXT")
      (libsource (lib "eagle-import") (part "M01PTH_WITHOUT_TEXT"))
    )
    (comp (ref "JP137")
      (value "M01PTH_WITHOUT_TEXT")
      (footprint "eagle-import:1X01_WITHOUT_TEXT")
      (libsource (lib "eagle-import") (part "M01PTH_WITHOUT_TEXT"))
    )
    (comp (ref "JP138")
      (value "M01PTH_WITHOUT_TEXT")
      (footprint "eagle-import:1X01_WITHOUT_TEXT")
      (libsource (lib "eagle-import") (part "M01PTH_WITHOUT_TEXT"))
    )
    (comp (ref "JP139")
      (value "M01PTH_WITHOUT_TEXT")
      (footprint "eagle-import:1X01_WITHOUT_TEXT")
      (libsource (lib "eagle-import") (part "M01PTH_WITHOUT_TEXT"))
    )
    (comp (ref "JP140")
      (value "M01PTH_WITHOUT_TEXT")
      (footprint "eagle-import:1X01_WITHOUT_TEXT")
      (libsource (lib "eagle-import") (part "M01PTH_WITHOUT_TEXT"))
    )
    (comp (ref "JP141")
      (value "M01PTH_WITHOUT_TEXT")
      (footprint "eagle-import:1X01_WITHOUT_TEXT")
      (libsource (lib "eagle-import") (part "M01PTH_WITHOUT_TEXT"))
    )
    (comp (ref "JP142")
      (value "M01PTH_WITHOUT_TEXT")
      (footprint "eagle-import:1X01_WITHOUT_TEXT")
      (libsource (lib "eagle-import") (part "M01PTH_WITHOUT_TEXT"))
    )
    (comp (ref "JP143")
      (value "M01PTH_WITHOUT_TEXT")
      (footprint "eagle-import:1X01_WITHOUT_TEXT")
      (libsource (lib "eagle-import") (part "M01PTH_WITHOUT_TEXT"))
    )
    (comp (ref "JP144")
      (value "M01PTH_WITHOUT_TEXT")
      (footprint "eagle-import:1X01_WITHOUT_TEXT")
      (libsource (lib "eagle-import") (part "M01PTH_WITHOUT_TEXT"))
    )
    (comp (ref "JP145")
      (value "M01PTH_WITHOUT_TEXT")
      (footprint "eagle-import:1X01_WITHOUT_TEXT")
      (libsource (lib "eagle-import") (part "M01PTH_WITHOUT_TEXT"))
    )
    (comp (ref "JP146")
      (value "M01PTH_WITHOUT_TEXT")
      (footprint "eagle-import:1X01_WITHOUT_TEXT")
      (libsource (lib "eagle-import") (part "M01PTH_WITHOUT_TEXT"))
    )
    (comp (ref "JP147")
      (value "M01PTH_WITHOUT_TEXT")
      (footprint "eagle-import:1X01_WITHOUT_TEXT")
      (libsource (lib "eagle-import") (part "M01PTH_WITHOUT_TEXT"))
    )
    (comp (ref "JP148")
      (value "M01PTH_WITHOUT_TEXT")
      (footprint "eagle-import:1X01_WITHOUT_TEXT")
      (libsource (lib "eagle-import") (part "M01PTH_WITHOUT_TEXT"))
    )
    (comp (ref "JP149")
      (value "M01PTH_WITHOUT_TEXT")
      (footprint "eagle-import:1X01_WITHOUT_TEXT")
      (libsource (lib "eagle-import") (part "M01PTH_WITHOUT_TEXT"))
    )
    (comp (ref "JP150")
      (value "M01PTH_WITHOUT_TEXT")
      (footprint "eagle-import:1X01_WITHOUT_TEXT")
      (libsource (lib "eagle-import") (part "M01PTH_WITHOUT_TEXT"))
    )
    (comp (ref "JP151")
      (value "M01PTH_WITHOUT_TEXT")
      (footprint "eagle-import:1X01_WITHOUT_TEXT")
      (libsource (lib "eagle-import") (part "M01PTH_WITHOUT_TEXT"))
    )
    (comp (ref "JP152")
      (value "M01PTH_WITHOUT_TEXT")
      (footprint "eagle-import:1X01_WITHOUT_TEXT")
      (libsource (lib "eagle-import") (part "M01PTH_WITHOUT_TEXT"))
    )
    (comp (ref "JP153")
      (value "M01PTH_WITHOUT_TEXT")
      (footprint "eagle-import:1X01_WITHOUT_TEXT")
      (libsource (lib "eagle-import") (part "M01PTH_WITHOUT_TEXT"))
    )
    (comp (ref "JP154")
      (value "M01PTH_WITHOUT_TEXT")
      (footprint "eagle-import:1X01_WITHOUT_TEXT")
      (libsource (lib "eagle-import") (part "M01PTH_WITHOUT_TEXT"))
    )
    (comp (ref "JP155")
      (value "M01PTH_WITHOUT_TEXT")
      (footprint "eagle-import:1X01_WITHOUT_TEXT")
      (libsource (lib "eagle-import") (part "M01PTH_WITHOUT_TEXT"))
    )
    (comp (ref "JP156")
      (value "M01PTH_WITHOUT_TEXT")
      (footprint "eagle-import:1X01_WITHOUT_TEXT")
      (libsource (lib "eagle-import") (part "M01PTH_WITHOUT_TEXT"))
    )
    (comp (ref "JP157")
      (value "M01PTH_WITHOUT_TEXT")
      (footprint "eagle-import:1X01_WITHOUT_TEXT")
      (libsource (lib "eagle-import") (part "M01PTH_WITHOUT_TEXT"))
    )
    (comp (ref "JP158")
      (value "M01PTH_WITHOUT_TEXT")
      (footprint "eagle-import:1X01_WITHOUT_TEXT")
      (libsource (lib "eagle-import") (part "M01PTH_WITHOUT_TEXT"))
    )
    (comp (ref "JP159")
      (value "M01PTH_WITHOUT_TEXT")
      (footprint "eagle-import:1X01_WITHOUT_TEXT")
      (libsource (lib "eagle-import") (part "M01PTH_WITHOUT_TEXT"))
    )
    (comp (ref "JP160")
      (value "M01PTH_WITHOUT_TEXT")
      (footprint "eagle-import:1X01_WITHOUT_TEXT")
      (libsource (lib "eagle-import") (part "M01PTH_WITHOUT_TEXT"))
    )
    (comp (ref "JP161")
      (value "M01PTH_WITHOUT_TEXT")
      (footprint "eagle-import:1X01_WITHOUT_TEXT")
      (libsource (lib "eagle-import") (part "M01PTH_WITHOUT_TEXT"))
    )
    (comp (ref "JP162")
      (value "M01PTH_WITHOUT_TEXT")
      (footprint "eagle-import:1X01_WITHOUT_TEXT")
      (libsource (lib "eagle-import") (part "M01PTH_WITHOUT_TEXT"))
    )
    (comp (ref "JP163")
      (value "M01PTH_WITHOUT_TEXT")
      (footprint "eagle-import:1X01_WITHOUT_TEXT")
      (libsource (lib "eagle-import") (part "M01PTH_WITHOUT_TEXT"))
    )
    (comp (ref "JP164")
      (value "M01PTH_WITHOUT_TEXT")
      (footprint "eagle-import:1X01_WITHOUT_TEXT")
      (libsource (lib "eagle-import") (part "M01PTH_WITHOUT_TEXT"))
    )
    (comp (ref "JP165")
      (value "M01PTH_WITHOUT_TEXT")
      (footprint "eagle-import:1X01_WITHOUT_TEXT")
      (libsource (lib "eagle-import") (part "M01PTH_WITHOUT_TEXT"))
    )
    (comp (ref "JP166")
      (value "M01PTH_WITHOUT_TEXT")
      (footprint "eagle-import:1X01_WITHOUT_TEXT")
      (libsource (lib "eagle-import") (part "M01PTH_WITHOUT_TEXT"))
    )
    (comp (ref "JP167")
      (value "M01PTH_WITHOUT_TEXT")
      (footprint "eagle-import:1X01_WITHOUT_TEXT")
      (libsource (lib "eagle-import") (part "M01PTH_WITHOUT_TEXT"))
    )
    (comp (ref "JP168")
      (value "M01PTH_WITHOUT_TEXT")
      (footprint "eagle-import:1X01_WITHOUT_TEXT")
      (libsource (lib "eagle-import") (part "M01PTH_WITHOUT_TEXT"))
    )
    (comp (ref "JP169")
      (value "M01PTH_WITHOUT_TEXT")
      (footprint "eagle-import:1X01_WITHOUT_TEXT")
      (libsource (lib "eagle-import") (part "M01PTH_WITHOUT_TEXT"))
    )
    (comp (ref "JP170")
      (value "M01PTH_WITHOUT_TEXT")
      (footprint "eagle-import:1X01_WITHOUT_TEXT")
      (libsource (lib "eagle-import") (part "M01PTH_WITHOUT_TEXT"))
    )
    (comp (ref "JP171")
      (value "M01PTH_WITHOUT_TEXT")
      (footprint "eagle-import:1X01_WITHOUT_TEXT")
      (libsource (lib "eagle-import") (part "M01PTH_WITHOUT_TEXT"))
    )
    (comp (ref "JP172")
      (value "M01PTH_WITHOUT_TEXT")
      (footprint "eagle-import:1X01_WITHOUT_TEXT")
      (libsource (lib "eagle-import") (part "M01PTH_WITHOUT_TEXT"))
    )
    (comp (ref "JP173")
      (value "M01PTH_WITHOUT_TEXT")
      (footprint "eagle-import:1X01_WITHOUT_TEXT")
      (libsource (lib "eagle-import") (part "M01PTH_WITHOUT_TEXT"))
    )
    (comp (ref "JP174")
      (value "M01PTH_WITHOUT_TEXT")
      (footprint "eagle-import:1X01_WITHOUT_TEXT")
      (libsource (lib "eagle-import") (part "M01PTH_WITHOUT_TEXT"))
    )
    (comp (ref "JP175")
      (value "M01PTH_WITHOUT_TEXT")
      (footprint "eagle-import:1X01_WITHOUT_TEXT")
      (libsource (lib "eagle-import") (part "M01PTH_WITHOUT_TEXT"))
    )
    (comp (ref "JP176")
      (value "M01PTH_WITHOUT_TEXT")
      (footprint "eagle-import:1X01_WITHOUT_TEXT")
      (libsource (lib "eagle-import") (part "M01PTH_WITHOUT_TEXT"))
    )
    (comp (ref "JP177")
      (value "M01PTH_WITHOUT_TEXT")
      (footprint "eagle-import:1X01_WITHOUT_TEXT")
      (libsource (lib "eagle-import") (part "M01PTH_WITHOUT_TEXT"))
    )
    (comp (ref "JP178")
      (value "M01PTH_WITHOUT_TEXT")
      (footprint "eagle-import:1X01_WITHOUT_TEXT")
      (libsource (lib "eagle-import") (part "M01PTH_WITHOUT_TEXT"))
    )
    (comp (ref "JP179")
      (value "M01PTH_WITHOUT_TEXT")
      (footprint "eagle-import:1X01_WITHOUT_TEXT")
      (libsource (lib "eagle-import") (part "M01PTH_WITHOUT_TEXT"))
    )
    (comp (ref "JP180")
      (value "M01PTH_WITHOUT_TEXT")
      (footprint "eagle-import:1X01_WITHOUT_TEXT")
      (libsource (lib "eagle-import") (part "M01PTH_WITHOUT_TEXT"))
    )
    (comp (ref "JP181")
      (value "M01PTH_WITHOUT_TEXT")
      (footprint "eagle-import:1X01_WITHOUT_TEXT")
      (libsource (lib "eagle-import") (part "M01PTH_WITHOUT_TEXT"))
    )
    (comp (ref "JP182")
      (value "M01PTH_WITHOUT_TEXT")
      (footprint "eagle-import:1X01_WITHOUT_TEXT")
      (libsource (lib "eagle-import") (part "M01PTH_WITHOUT_TEXT"))
    )
    (comp (ref "JP183")
      (value "M01PTH_WITHOUT_TEXT")
      (footprint "eagle-import:1X01_WITHOUT_TEXT")
      (libsource (lib "eagle-import") (part "M01PTH_WITHOUT_TEXT"))
    )
    (comp (ref "JP184")
      (value "M01PTH_WITHOUT_TEXT")
      (footprint "eagle-import:1X01_WITHOUT_TEXT")
      (libsource (lib "eagle-import") (part "M01PTH_WITHOUT_TEXT"))
    )
    (comp (ref "JP185")
      (value "M01PTH_WITHOUT_TEXT")
      (footprint "eagle-import:1X01_WITHOUT_TEXT")
      (libsource (lib "eagle-import") (part "M01PTH_WITHOUT_TEXT"))
    )
    (comp (ref "JP186")
      (value "M01PTH_WITHOUT_TEXT")
      (footprint "eagle-import:1X01_WITHOUT_TEXT")
      (libsource (lib "eagle-import") (part "M01PTH_WITHOUT_TEXT"))
    )
    (comp (ref "JP187")
      (value "M01PTH_WITHOUT_TEXT")
      (footprint "eagle-import:1X01_WITHOUT_TEXT")
      (libsource (lib "eagle-import") (part "M01PTH_WITHOUT_TEXT"))
    )
    (comp (ref "JP188")
      (value "M01PTH_WITHOUT_TEXT")
      (footprint "eagle-import:1X01_WITHOUT_TEXT")
      (libsource (lib "eagle-import") (part "M01PTH_WITHOUT_TEXT"))
    )
    (comp (ref "JP189")
      (value "M01PTH_WITHOUT_TEXT")
      (footprint "eagle-import:1X01_WITHOUT_TEXT")
      (libsource (lib "eagle-import") (part "M01PTH_WITHOUT_TEXT"))
    )
    (comp (ref "JP190")
      (value "M01PTH_WITHOUT_TEXT")
      (footprint "eagle-import:1X01_WITHOUT_TEXT")
      (libsource (lib "eagle-import") (part "M01PTH_WITHOUT_TEXT"))
    )
    (comp (ref "JP191")
      (value "M01PTH_WITHOUT_TEXT")
      (footprint "eagle-import:1X01_WITHOUT_TEXT")
      (libsource (lib "eagle-import") (part "M01PTH_WITHOUT_TEXT"))
    )
    (comp (ref "JP192")
      (value "M01PTH_WITHOUT_TEXT")
      (footprint "eagle-import:1X01_WITHOUT_TEXT")
      (libsource (lib "eagle-import") (part "M01PTH_WITHOUT_TEXT"))
    )
    (comp (ref "JP193")
      (value "M01PTH_WITHOUT_TEXT")
      (footprint "eagle-import:1X01_WITHOUT_TEXT")
      (libsource (lib "eagle-import") (part "M01PTH_WITHOUT_TEXT"))
    )
    (comp (ref "JP194")
      (value "M01PTH_WITHOUT_TEXT")
      (footprint "eagle-import:1X01_WITHOUT_TEXT")
      (libsource (lib "eagle-import") (part "M01PTH_WITHOUT_TEXT"))
    )
    (comp (ref "JP195")
      (value "M01PTH_WITHOUT_TEXT")
      (footprint "eagle-import:1X01_WITHOUT_TEXT")
      (libsource (lib "eagle-import") (part "M01PTH_WITHOUT_TEXT"))
    )
    (comp (ref "JP196")
      (value "M01PTH_WITHOUT_TEXT")
      (footprint "eagle-import:1X01_WITHOUT_TEXT")
      (libsource (lib "eagle-import") (part "M01PTH_WITHOUT_TEXT"))
    )
    (comp (ref "JP197")
      (value "M01PTH_WITHOUT_TEXT")
      (footprint "eagle-import:1X01_WITHOUT_TEXT")
      (libsource (lib "eagle-import") (part "M01PTH_WITHOUT_TEXT"))
    )
    (comp (ref "JP198")
      (value "M01PTH_WITHOUT_TEXT")
      (footprint "eagle-import:1X01_WITHOUT_TEXT")
      (libsource (lib "eagle-import") (part "M01PTH_WITHOUT_TEXT"))
    )
    (comp (ref "JP199")
      (value "M01PTH_WITHOUT_TEXT")
      (footprint "eagle-import:1X01_WITHOUT_TEXT")
      (libsource (lib "eagle-import") (part "M01PTH_WITHOUT_TEXT"))
    )
    (comp (ref "JP200")
      (value "M01PTH_WITHOUT_TEXT")
      (footprint "eagle-import:1X01_WITHOUT_TEXT")
      (libsource (lib "eagle-import") (part "M01PTH_WITHOUT_TEXT"))
    )
    (comp (ref "JP201")
      (value "M01PTH_WITHOUT_TEXT")
      (footprint "eagle-import:1X01_WITHOUT_TEXT")
      (libsource (lib "eagle-import") (part "M01PTH_WITHOUT_TEXT"))
    )
    (comp (ref "JP202")
      (value "M01PTH_WITHOUT_TEXT")
      (footprint "eagle-import:1X01_WITHOUT_TEXT")
      (libsource (lib "eagle-import") (part "M01PTH_WITHOUT_TEXT"))
    )
    (comp (ref "JP203")
      (value "M01PTH_WITHOUT_TEXT")
      (footprint "eagle-import:1X01_WITHOUT_TEXT")
      (libsource (lib "eagle-import") (part "M01PTH_WITHOUT_TEXT"))
    )
    (comp (ref "JP204")
      (value "M01PTH_WITHOUT_TEXT")
      (footprint "eagle-import:1X01_WITHOUT_TEXT")
      (libsource (lib "eagle-import") (part "M01PTH_WITHOUT_TEXT"))
    )
    (comp (ref "JP205")
      (value "M01PTH_WITHOUT_TEXT")
      (footprint "eagle-import:1X01_WITHOUT_TEXT")
      (libsource (lib "eagle-import") (part "M01PTH_WITHOUT_TEXT"))
    )
    (comp (ref "JP206")
      (value "M01PTH_WITHOUT_TEXT")
      (footprint "eagle-import:1X01_WITHOUT_TEXT")
      (libsource (lib "eagle-import") (part "M01PTH_WITHOUT_TEXT"))
    )
    (comp (ref "JP207")
      (value "M01PTH_WITHOUT_TEXT")
      (footprint "eagle-import:1X01_WITHOUT_TEXT")
      (libsource (lib "eagle-import") (part "M01PTH_WITHOUT_TEXT"))
    )
    (comp (ref "JP208")
      (value "M01PTH_WITHOUT_TEXT")
      (footprint "eagle-import:1X01_WITHOUT_TEXT")
      (libsource (lib "eagle-import") (part "M01PTH_WITHOUT_TEXT"))
    )
    (comp (ref "JP209")
      (value "M01PTH_WITHOUT_TEXT")
      (footprint "eagle-import:1X01_WITHOUT_TEXT")
      (libsource (lib "eagle-import") (part "M01PTH_WITHOUT_TEXT"))
    )
    (comp (ref "JP210")
      (value "M01PTH_WITHOUT_TEXT")
      (footprint "eagle-import:1X01_WITHOUT_TEXT")
      (libsource (lib "eagle-import") (part "M01PTH_WITHOUT_TEXT"))
    )
    (comp (ref "JP211")
      (value "M01PTH_WITHOUT_TEXT")
      (footprint "eagle-import:1X01_WITHOUT_TEXT")
      (libsource (lib "eagle-import") (part "M01PTH_WITHOUT_TEXT"))
    )
    (comp (ref "JP212")
      (value "M01PTH_WITHOUT_TEXT")
      (footprint "eagle-import:1X01_WITHOUT_TEXT")
      (libsource (lib "eagle-import") (part "M01PTH_WITHOUT_TEXT"))
    )
    (comp (ref "JP213")
      (value "M01PTH_WITHOUT_TEXT")
      (footprint "eagle-import:1X01_WITHOUT_TEXT")
      (libsource (lib "eagle-import") (part "M01PTH_WITHOUT_TEXT"))
    )
    (comp (ref "JP214")
      (value "M01PTH_WITHOUT_TEXT")
      (footprint "eagle-import:1X01_WITHOUT_TEXT")
      (libsource (lib "eagle-import") (part "M01PTH_WITHOUT_TEXT"))
    )
    (comp (ref "JP215")
      (value "M01PTH_WITHOUT_TEXT")
      (footprint "eagle-import:1X01_WITHOUT_TEXT")
      (libsource (lib "eagle-import") (part "M01PTH_WITHOUT_TEXT"))
    )
    (comp (ref "JP216")
      (value "M01PTH_WITHOUT_TEXT")
      (footprint "eagle-import:1X01_WITHOUT_TEXT")
      (libsource (lib "eagle-import") (part "M01PTH_WITHOUT_TEXT"))
    )
    (comp (ref "JP217")
      (value "M01PTH_WITHOUT_TEXT")
      (footprint "eagle-import:1X01_WITHOUT_TEXT")
      (libsource (lib "eagle-import") (part "M01PTH_WITHOUT_TEXT"))
    )
    (comp (ref "JP218")
      (value "M01PTH_WITHOUT_TEXT")
      (footprint "eagle-import:1X01_WITHOUT_TEXT")
      (libsource (lib "eagle-import") (part "M01PTH_WITHOUT_TEXT"))
    )
    (comp (ref "JP219")
      (value "M01PTH_WITHOUT_TEXT")
      (footprint "eagle-import:1X01_WITHOUT_TEXT")
      (libsource (lib "eagle-import") (part "M01PTH_WITHOUT_TEXT"))
    )
    (comp (ref "JP220")
      (value "M01PTH_WITHOUT_TEXT")
      (footprint "eagle-import:1X01_WITHOUT_TEXT")
      (libsource (lib "eagle-import") (part "M01PTH_WITHOUT_TEXT"))
    )
    (comp (ref "JP221")
      (value "M01PTH_WITHOUT_TEXT")
      (footprint "eagle-import:1X01_WITHOUT_TEXT")
      (libsource (lib "eagle-import") (part "M01PTH_WITHOUT_TEXT"))
    )
    (comp (ref "JP222")
      (value "M01PTH_WITHOUT_TEXT")
      (footprint "eagle-import:1X01_WITHOUT_TEXT")
      (libsource (lib "eagle-import") (part "M01PTH_WITHOUT_TEXT"))
    )
    (comp (ref "JP223")
      (value "M01PTH_WITHOUT_TEXT")
      (footprint "eagle-import:1X01_WITHOUT_TEXT")
      (libsource (lib "eagle-import") (part "M01PTH_WITHOUT_TEXT"))
    )
    (comp (ref "JP224")
      (value "M01PTH_WITHOUT_TEXT")
      (footprint "eagle-import:1X01_WITHOUT_TEXT")
      (libsource (lib "eagle-import") (part "M01PTH_WITHOUT_TEXT"))
    )
    (comp (ref "JP225")
      (value "M01PTH_WITHOUT_TEXT")
      (footprint "eagle-import:1X01_WITHOUT_TEXT")
      (libsource (lib "eagle-import") (part "M01PTH_WITHOUT_TEXT"))
    )
    (comp (ref "JP226")
      (value "M01PTH_WITHOUT_TEXT")
      (footprint "eagle-import:1X01_WITHOUT_TEXT")
      (libsource (lib "eagle-import") (part "M01PTH_WITHOUT_TEXT"))
    )
    (comp (ref "JP227")
      (value "M01PTH_WITHOUT_TEXT")
      (footprint "eagle-import:1X01_WITHOUT_TEXT")
      (libsource (lib "eagle-import") (part "M01PTH_WITHOUT_TEXT"))
    )
    (comp (ref "JP228")
      (value "M01PTH_WITHOUT_TEXT")
      (footprint "eagle-import:1X01_WITHOUT_TEXT")
      (libsource (lib "eagle-import") (part "M01PTH_WITHOUT_TEXT"))
    )
    (comp (ref "JP229")
      (value "M01PTH_WITHOUT_TEXT")
      (footprint "eagle-import:1X01_WITHOUT_TEXT")
      (libsource (lib "eagle-import") (part "M01PTH_WITHOUT_TEXT"))
    )
    (comp (ref "JP230")
      (value "M01PTH_WITHOUT_TEXT")
      (footprint "eagle-import:1X01_WITHOUT_TEXT")
      (libsource (lib "eagle-import") (part "M01PTH_WITHOUT_TEXT"))
    )
    (comp (ref "JP231")
      (value "M01PTH_WITHOUT_TEXT")
      (footprint "eagle-import:1X01_WITHOUT_TEXT")
      (libsource (lib "eagle-import") (part "M01PTH_WITHOUT_TEXT"))
    )
    (comp (ref "JP232")
      (value "M01PTH_WITHOUT_TEXT")
      (footprint "eagle-import:1X01_WITHOUT_TEXT")
      (libsource (lib "eagle-import") (part "M01PTH_WITHOUT_TEXT"))
    )
    (comp (ref "JP233")
      (value "M01PTH_WITHOUT_TEXT")
      (footprint "eagle-import:1X01_WITHOUT_TEXT")
      (libsource (lib "eagle-import") (part "M01PTH_WITHOUT_TEXT"))
    )
    (comp (ref "JP234")
      (value "M01PTH_WITHOUT_TEXT")
      (footprint "eagle-import:1X01_WITHOUT_TEXT")
      (libsource (lib "eagle-import") (part "M01PTH_WITHOUT_TEXT"))
    )
    (comp (ref "JP235")
      (value "M01PTH_WITHOUT_TEXT")
      (footprint "eagle-import:1X01_WITHOUT_TEXT")
      (libsource (lib "eagle-import") (part "M01PTH_WITHOUT_TEXT"))
    )
    (comp (ref "JP236")
      (value "M01PTH_WITHOUT_TEXT")
      (footprint "eagle-import:1X01_WITHOUT_TEXT")
      (libsource (lib "eagle-import") (part "M01PTH_WITHOUT_TEXT"))
    )
    (comp (ref "JP237")
      (value "M01PTH_WITHOUT_TEXT")
      (footprint "eagle-import:1X01_WITHOUT_TEXT")
      (libsource (lib "eagle-import") (part "M01PTH_WITHOUT_TEXT"))
    )
    (comp (ref "JP238")
      (value "M01PTH_WITHOUT_TEXT")
      (footprint "eagle-import:1X01_WITHOUT_TEXT")
      (libsource (lib "eagle-import") (part "M01PTH_WITHOUT_TEXT"))
    )
    (comp (ref "JP239")
      (value "M01PTH_WITHOUT_TEXT")
      (footprint "eagle-import:1X01_WITHOUT_TEXT")
      (libsource (lib "eagle-import") (part "M01PTH_WITHOUT_TEXT"))
    )
    (comp (ref "JP240")
      (value "M01PTH_WITHOUT_TEXT")
      (footprint "eagle-import:1X01_WITHOUT_TEXT")
      (libsource (lib "eagle-import") (part "M01PTH_WITHOUT_TEXT"))
    )
    (comp (ref "JP241")
      (value "M01PTH_WITHOUT_TEXT")
      (footprint "eagle-import:1X01_WITHOUT_TEXT")
      (libsource (lib "eagle-import") (part "M01PTH_WITHOUT_TEXT"))
    )
    (comp (ref "JP242")
      (value "M01PTH_WITHOUT_TEXT")
      (footprint "eagle-import:1X01_WITHOUT_TEXT")
      (libsource (lib "eagle-import") (part "M01PTH_WITHOUT_TEXT"))
    )
    (comp (ref "JP243")
      (value "M01PTH_WITHOUT_TEXT")
      (footprint "eagle-import:1X01_WITHOUT_TEXT")
      (libsource (lib "eagle-import") (part "M01PTH_WITHOUT_TEXT"))
    )
    (comp (ref "JP244")
      (value "M01PTH_WITHOUT_TEXT")
      (footprint "eagle-import:1X01_WITHOUT_TEXT")
      (libsource (lib "eagle-import") (part "M01PTH_WITHOUT_TEXT"))
    )
    (comp (ref "JP245")
      (value "M01PTH_WITHOUT_TEXT")
      (footprint "eagle-import:1X01_WITHOUT_TEXT")
      (libsource (lib "eagle-import") (part "M01PTH_WITHOUT_TEXT"))
    )
    (comp (ref "JP246")
      (value "M01PTH_WITHOUT_TEXT")
      (footprint "eagle-import:1X01_WITHOUT_TEXT")
      (libsource (lib "eagle-import") (part "M01PTH_WITHOUT_TEXT"))
    )
    (comp (ref "JP247")
      (value "M01PTH_WITHOUT_TEXT")
      (footprint "eagle-import:1X01_WITHOUT_TEXT")
      (libsource (lib "eagle-import") (part "M01PTH_WITHOUT_TEXT"))
    )
    (comp (ref "JP248")
      (value "M01PTH_WITHOUT_TEXT")
      (footprint "eagle-import:1X01_WITHOUT_TEXT")
      (libsource (lib "eagle-import") (part "M01PTH_WITHOUT_TEXT"))
    )
    (comp (ref "JP249")
      (value "M01PTH_WITHOUT_TEXT")
      (footprint "eagle-import:1X01_WITHOUT_TEXT")
      (libsource (lib "eagle-import") (part "M01PTH_WITHOUT_TEXT"))
    )
    (comp (ref "JP250")
      (value "M01PTH_WITHOUT_TEXT")
      (footprint "eagle-import:1X01_WITHOUT_TEXT")
      (libsource (lib "eagle-import") (part "M01PTH_WITHOUT_TEXT"))
    )
    (comp (ref "JP251")
      (value "M01PTH_WITHOUT_TEXT")
      (footprint "eagle-import:1X01_WITHOUT_TEXT")
      (libsource (lib "eagle-import") (part "M01PTH_WITHOUT_TEXT"))
    )
    (comp (ref "JP252")
      (value "M01PTH_WITHOUT_TEXT")
      (footprint "eagle-import:1X01_WITHOUT_TEXT")
      (libsource (lib "eagle-import") (part "M01PTH_WITHOUT_TEXT"))
    )
    (comp (ref "JP253")
      (value "M01PTH_WITHOUT_TEXT")
      (footprint "eagle-import:1X01_WITHOUT_TEXT")
      (libsource (lib "eagle-import") (part "M01PTH_WITHOUT_TEXT"))
    )
    (comp (ref "JP254")
      (value "M01PTH_WITHOUT_TEXT")
      (footprint "eagle-import:1X01_WITHOUT_TEXT")
      (libsource (lib "eagle-import") (part "M01PTH_WITHOUT_TEXT"))
    )
    (comp (ref "JP255")
      (value "M01PTH_WITHOUT_TEXT")
      (footprint "eagle-import:1X01_WITHOUT_TEXT")
      (libsource (lib "eagle-import") (part "M01PTH_WITHOUT_TEXT"))
    )
    (comp (ref "JP256")
      (value "M01PTH_WITHOUT_TEXT")
      (footprint "eagle-import:1X01_WITHOUT_TEXT")
      (libsource (lib "eagle-import") (part "M01PTH_WITHOUT_TEXT"))
    )
    (comp (ref "JP257")
      (value "M01PTH_WITHOUT_TEXT")
      (footprint "eagle-import:1X01_WITHOUT_TEXT")
      (libsource (lib "eagle-import") (part "M01PTH_WITHOUT_TEXT"))
    )
    (comp (ref "JP258")
      (value "M01PTH_WITHOUT_TEXT")
      (footprint "eagle-import:1X01_WITHOUT_TEXT")
      (libsource (lib "eagle-import") (part "M01PTH_WITHOUT_TEXT"))
    )
    (comp (ref "JP259")
      (value "M01PTH_WITHOUT_TEXT")
      (footprint "eagle-import:1X01_WITHOUT_TEXT")
      (libsource (lib "eagle-import") (part "M01PTH_WITHOUT_TEXT"))
    )
    (comp (ref "JP260")
      (value "M01PTH_WITHOUT_TEXT")
      (footprint "eagle-import:1X01_WITHOUT_TEXT")
      (libsource (lib "eagle-import") (part "M01PTH_WITHOUT_TEXT"))
    )
    (comp (ref "JP261")
      (value "M01PTH_WITHOUT_TEXT")
      (footprint "eagle-import:1X01_WITHOUT_TEXT")
      (libsource (lib "eagle-import") (part "M01PTH_WITHOUT_TEXT"))
    )
    (comp (ref "JP262")
      (value "M01PTH_WITHOUT_TEXT")
      (footprint "eagle-import:1X01_WITHOUT_TEXT")
      (libsource (lib "eagle-import") (part "M01PTH_WITHOUT_TEXT"))
    )
    (comp (ref "JP263")
      (value "M01PTH_WITHOUT_TEXT")
      (footprint "eagle-import:1X01_WITHOUT_TEXT")
      (libsource (lib "eagle-import") (part "M01PTH_WITHOUT_TEXT"))
    )
    (comp (ref "JP264")
      (value "M01PTH_WITHOUT_TEXT")
      (footprint "eagle-import:1X01_WITHOUT_TEXT")
      (libsource (lib "eagle-import") (part "M01PTH_WITHOUT_TEXT"))
    )
    (comp (ref "JP265")
      (value "M01PTH_WITHOUT_TEXT")
      (footprint "eagle-import:1X01_WITHOUT_TEXT")
      (libsource (lib "eagle-import") (part "M01PTH_WITHOUT_TEXT"))
    )
    (comp (ref "JP266")
      (value "M01PTH_WITHOUT_TEXT")
      (footprint "eagle-import:1X01_WITHOUT_TEXT")
      (libsource (lib "eagle-import") (part "M01PTH_WITHOUT_TEXT"))
    )
    (comp (ref "JP267")
      (value "M01PTH_WITHOUT_TEXT")
      (footprint "eagle-import:1X01_WITHOUT_TEXT")
      (libsource (lib "eagle-import") (part "M01PTH_WITHOUT_TEXT"))
    )
    (comp (ref "JP268")
      (value "M01PTH_WITHOUT_TEXT")
      (footprint "eagle-import:1X01_WITHOUT_TEXT")
      (libsource (lib "eagle-import") (part "M01PTH_WITHOUT_TEXT"))
    )
    (comp (ref "JP269")
      (value "M01PTH_WITHOUT_TEXT")
      (footprint "eagle-import:1X01_WITHOUT_TEXT")
      (libsource (lib "eagle-import") (part "M01PTH_WITHOUT_TEXT"))
    )
    (comp (ref "JP270")
      (value "M01PTH_WITHOUT_TEXT")
      (footprint "eagle-import:1X01_WITHOUT_TEXT")
      (libsource (lib "eagle-import") (part "M01PTH_WITHOUT_TEXT"))
    )
    (comp (ref "JP271")
      (value "M01PTH_WITHOUT_TEXT")
      (footprint "eagle-import:1X01_WITHOUT_TEXT")
      (libsource (lib "eagle-import") (part "M01PTH_WITHOUT_TEXT"))
    )
    (comp (ref "JP272")
      (value "M01PTH_WITHOUT_TEXT")
      (footprint "eagle-import:1X01_WITHOUT_TEXT")
      (libsource (lib "eagle-import") (part "M01PTH_WITHOUT_TEXT"))
    )
    (comp (ref "JP273")
      (value "M01PTH_WITHOUT_TEXT")
      (footprint "eagle-import:1X01_WITHOUT_TEXT")
      (libsource (lib "eagle-import") (part "M01PTH_WITHOUT_TEXT"))
    )
    (comp (ref "JP274")
      (value "M01PTH_WITHOUT_TEXT")
      (footprint "eagle-import:1X01_WITHOUT_TEXT")
      (libsource (lib "eagle-import") (part "M01PTH_WITHOUT_TEXT"))
    )
    (comp (ref "JP275")
      (value "M01PTH_WITHOUT_TEXT")
      (footprint "eagle-import:1X01_WITHOUT_TEXT")
      (libsource (lib "eagle-import") (part "M01PTH_WITHOUT_TEXT"))
    )
    (comp (ref "JP276")
      (value "M01PTH_WITHOUT_TEXT")
      (footprint "eagle-import:1X01_WITHOUT_TEXT")
      (libsource (lib "eagle-import") (part "M01PTH_WITHOUT_TEXT"))
    )
    (comp (ref "JP277")
      (value "M01PTH_WITHOUT_TEXT")
      (footprint "eagle-import:1X01_WITHOUT_TEXT")
      (libsource (lib "eagle-import") (part "M01PTH_WITHOUT_TEXT"))
    )
    (comp (ref "JP278")
      (value "M01PTH_WITHOUT_TEXT")
      (footprint "eagle-import:1X01_WITHOUT_TEXT")
      (libsource (lib "eagle-import") (part "M01PTH_WITHOUT_TEXT"))
    )
    (comp (ref "JP279")
      (value "M01PTH_WITHOUT_TEXT")
      (footprint "eagle-import:1X01_WITHOUT_TEXT")
      (libsource (lib "eagle-import") (part "M01PTH_WITHOUT_TEXT"))
    )
    (comp (ref "JP280")
      (value "M01PTH_WITHOUT_TEXT")
      (footprint "eagle-import:1X01_WITHOUT_TEXT")
      (libsource (lib "eagle-import") (part "M01PTH_WITHOUT_TEXT"))
    )
    (comp (ref "JP281")
      (value "M01PTH_WITHOUT_TEXT")
      (footprint "eagle-import:1X01_WITHOUT_TEXT")
      (libsource (lib "eagle-import") (part "M01PTH_WITHOUT_TEXT"))
    )
    (comp (ref "JP282")
      (value "M01PTH_WITHOUT_TEXT")
      (footprint "eagle-import:1X01_WITHOUT_TEXT")
      (libsource (lib "eagle-import") (part "M01PTH_WITHOUT_TEXT"))
    )
    (comp (ref "JP283")
      (value "M01PTH_WITHOUT_TEXT")
      (footprint "eagle-import:1X01_WITHOUT_TEXT")
      (libsource (lib "eagle-import") (part "M01PTH_WITHOUT_TEXT"))
    )
    (comp (ref "JP284")
      (value "M01PTH_WITHOUT_TEXT")
      (footprint "eagle-import:1X01_WITHOUT_TEXT")
      (libsource (lib "eagle-import") (part "M01PTH_WITHOUT_TEXT"))
    )
    (comp (ref "JP285")
      (value "M01PTH_WITHOUT_TEXT")
      (footprint "eagle-import:1X01_WITHOUT_TEXT")
      (libsource (lib "eagle-import") (part "M01PTH_WITHOUT_TEXT"))
    )
    (comp (ref "JP286")
      (value "M01PTH_WITHOUT_TEXT")
      (footprint "eagle-import:1X01_WITHOUT_TEXT")
      (libsource (lib "eagle-import") (part "M01PTH_WITHOUT_TEXT"))
    )
    (comp (ref "JP287")
      (value "M01PTH_WITHOUT_TEXT")
      (footprint "eagle-import:1X01_WITHOUT_TEXT")
      (libsource (lib "eagle-import") (part "M01PTH_WITHOUT_TEXT"))
    )
    (comp (ref "JP288")
      (value "M01PTH_WITHOUT_TEXT")
      (footprint "eagle-import:1X01_WITHOUT_TEXT")
      (libsource (lib "eagle-import") (part "M01PTH_WITHOUT_TEXT"))
    )
    (comp (ref "JP289")
      (value "M01PTH_WITHOUT_TEXT")
      (footprint "eagle-import:1X01_WITHOUT_TEXT")
      (libsource (lib "eagle-import") (part "M01PTH_WITHOUT_TEXT"))
    )
    (comp (ref "JP290")
      (value "M01PTH_WITHOUT_TEXT")
      (footprint "eagle-import:1X01_WITHOUT_TEXT")
      (libsource (lib "eagle-import") (part "M01PTH_WITHOUT_TEXT"))
    )
    (comp (ref "JP291")
      (value "M01PTH_WITHOUT_TEXT")
      (footprint "eagle-import:1X01_WITHOUT_TEXT")
      (libsource (lib "eagle-import") (part "M01PTH_WITHOUT_TEXT"))
    )
    (comp (ref "JP292")
      (value "M01PTH_WITHOUT_TEXT")
      (footprint "eagle-import:1X01_WITHOUT_TEXT")
      (libsource (lib "eagle-import") (part "M01PTH_WITHOUT_TEXT"))
    )
    (comp (ref "JP293")
      (value "M01PTH_WITHOUT_TEXT")
      (footprint "eagle-import:1X01_WITHOUT_TEXT")
      (libsource (lib "eagle-import") (part "M01PTH_WITHOUT_TEXT"))
    )
    (comp (ref "JP294")
      (value "M01PTH_WITHOUT_TEXT")
      (footprint "eagle-import:1X01_WITHOUT_TEXT")
      (libsource (lib "eagle-import") (part "M01PTH_WITHOUT_TEXT"))
    )
    (comp (ref "JP295")
      (value "M01PTH_WITHOUT_TEXT")
      (footprint "eagle-import:1X01_WITHOUT_TEXT")
      (libsource (lib "eagle-import") (part "M01PTH_WITHOUT_TEXT"))
    )
    (comp (ref "JP296")
      (value "M01PTH_WITHOUT_TEXT")
      (footprint "eagle-import:1X01_WITHOUT_TEXT")
      (libsource (lib "eagle-import") (part "M01PTH_WITHOUT_TEXT"))
    )
    (comp (ref "JP297")
      (value "M01PTH_WITHOUT_TEXT")
      (footprint "eagle-import:1X01_WITHOUT_TEXT")
      (libsource (lib "eagle-import") (part "M01PTH_WITHOUT_TEXT"))
    )
    (comp (ref "JP298")
      (value "M01PTH_WITHOUT_TEXT")
      (footprint "eagle-import:1X01_WITHOUT_TEXT")
      (libsource (lib "eagle-import") (part "M01PTH_WITHOUT_TEXT"))
    )
    (comp (ref "JP299")
      (value "M01PTH_WITHOUT_TEXT")
      (footprint "eagle-import:1X01_WITHOUT_TEXT")
      (libsource (lib "eagle-import") (part "M01PTH_WITHOUT_TEXT"))
    )
    (comp (ref "JP300")
      (value "M01PTH_WITHOUT_TEXT")
      (footprint "eagle-import:1X01_WITHOUT_TEXT")
      (libsource (lib "eagle-import") (part "M01PTH_WITHOUT_TEXT"))
    )
    (comp (ref "JP901")
      (value "M01PTH_SMD_1.27X0.635MM_NO_SILK")
      (footprint "eagle-import:1X01_SMD_1.27X0.635MM_NO_SILK")
      (libsource (lib "eagle-import") (part "M01PTH_SMD_1.27X0.635MM_NO_SILK"))
    )
    (comp (ref "JP902")
      (value "M01PTH_SMD_1.27X0.635MM_NO_SILK")
      (footprint "eagle-import:1X01_SMD_1.27X0.635MM_NO_SILK")
      (libsource (lib "eagle-import") (part "M01PTH_SMD_1.27X0.635MM_NO_SILK"))
    )
    (comp (ref "JP903")
      (value "M01PTH_SMD_1.27X0.635MM_NO_SILK")
      (footprint "eagle-import:1X01_SMD_1.27X0.635MM_NO_SILK")
      (libsource (lib "eagle-import") (part "M01PTH_SMD_1.27X0.635MM_NO_SILK"))
    )
    (comp (ref "JP904")
      (value "M01PTH_SMD_1.27X0.635MM_NO_SILK")
      (footprint "eagle-import:1X01_SMD_1.27X0.635MM_NO_SILK")
      (libsource (lib "eagle-import") (part "M01PTH_SMD_1.27X0.635MM_NO_SILK"))
    )
    (comp (ref "JP905")
      (value "M01PTH_SMD_1.27X0.635MM_NO_SILK")
      (footprint "eagle-import:1X01_SMD_1.27X0.635MM_NO_SILK")
      (libsource (lib "eagle-import") (part "M01PTH_SMD_1.27X0.635MM_NO_SILK"))
    )
    (comp (ref "JP906")
      (value "M01PTH_SMD_1.27X0.635MM_NO_SILK")
      (footprint "eagle-import:1X01_SMD_1.27X0.635MM_NO_SILK")
      (libsource (lib "eagle-import") (part "M01PTH_SMD_1.27X0.635MM_NO_SILK"))
    )
    (comp (ref "JP907")
      (value "M01PTH_SMD_1.27X0.635MM_NO_SILK")
      (footprint "eagle-import:1X01_SMD_1.27X0.635MM_NO_SILK")
      (libsource (lib "eagle-import") (part "M01PTH_SMD_1.27X0.635MM_NO_SILK"))
    )
    (comp (ref "JP908")
      (value "M01PTH_SMD_1.27X0.635MM_NO_SILK")
      (footprint "eagle-import:1X01_SMD_1.27X0.635MM_NO_SILK")
      (libsource (lib "eagle-import") (part "M01PTH_SMD_1.27X0.635MM_NO_SILK"))
    )
    (comp (ref "JP909")
      (value "M01PTH_SMD_1.27X0.635MM_NO_SILK")
      (footprint "eagle-import:1X01_SMD_1.27X0.635MM_NO_SILK")
      (libsource (lib "eagle-import") (part "M01PTH_SMD_1.27X0.635MM_NO_SILK"))
    )
    (comp (ref "JP910")
      (value "M01PTH_SMD_1.27X0.635MM_NO_SILK")
      (footprint "eagle-import:1X01_SMD_1.27X0.635MM_NO_SILK")
      (libsource (lib "eagle-import") (part "M01PTH_SMD_1.27X0.635MM_NO_SILK"))
    )
    (comp (ref "JP911")
      (value "M01PTH_SMD_1.27X0.635MM_NO_SILK")
      (footprint "eagle-import:1X01_SMD_1.27X0.635MM_NO_SILK")
      (libsource (lib "eagle-import") (part "M01PTH_SMD_1.27X0.635MM_NO_SILK"))
    )
    (comp (ref "JP912")
      (value "M01PTH_SMD_1.27X0.635MM_NO_SILK")
      (footprint "eagle-import:1X01_SMD_1.27X0.635MM_NO_SILK")
      (libsource (lib "eagle-import") (part "M01PTH_SMD_1.27X0.635MM_NO_SILK"))
    )
    (comp (ref "JP913")
      (value "M01PTH_SMD_1.27X0.635MM_NO_SILK")
      (footprint "eagle-import:1X01_SMD_1.27X0.635MM_NO_SILK")
      (libsource (lib "eagle-import") (part "M01PTH_SMD_1.27X0.635MM_NO_SILK"))
    )
    (comp (ref "JP914")
      (value "M01PTH_SMD_1.27X0.635MM_NO_SILK")
      (footprint "eagle-import:1X01_SMD_1.27X0.635MM_NO_SILK")
      (libsource (lib "eagle-import") (part "M01PTH_SMD_1.27X0.635MM_NO_SILK"))
    )
    (comp (ref "JP915")
      (value "M01PTH_SMD_1.27X0.635MM_NO_SILK")
      (footprint "eagle-import:1X01_SMD_1.27X0.635MM_NO_SILK")
      (libsource (lib "eagle-import") (part "M01PTH_SMD_1.27X0.635MM_NO_SILK"))
    )
    (comp (ref "JP916")
      (value "M01PTH_SMD_1.27X0.635MM_NO_SILK")
      (footprint "eagle-import:1X01_SMD_1.27X0.635MM_NO_SILK")
      (libsource (lib "eagle-import") (part "M01PTH_SMD_1.27X0.635MM_NO_SILK"))
    )
    (comp (ref "JP917")
      (value "M01PTH_SMD_1.27X0.635MM_NO_SILK")
      (footprint "eagle-import:1X01_SMD_1.27X0.635MM_NO_SILK")
      (libsource (lib "eagle-import") (part "M01PTH_SMD_1.27X0.635MM_NO_SILK"))
    )
    (comp (ref "JP918")
      (value "M01PTH_SMD_1.27X0.635MM_NO_SILK")
      (footprint "eagle-import:1X01_SMD_1.27X0.635MM_NO_SILK")
      (libsource (lib "eagle-import") (part "M01PTH_SMD_1.27X0.635MM_NO_SILK"))
    )
    (comp (ref "JP919")
      (value "M01PTH_SMD_1.27X0.635MM_NO_SILK")
      (footprint "eagle-import:1X01_SMD_1.27X0.635MM_NO_SILK")
      (libsource (lib "eagle-import") (part "M01PTH_SMD_1.27X0.635MM_NO_SILK"))
    )
    (comp (ref "JP920")
      (value "M01PTH_SMD_1.27X0.635MM_NO_SILK")
      (footprint "eagle-import:1X01_SMD_1.27X0.635MM_NO_SILK")
      (libsource (lib "eagle-import") (part "M01PTH_SMD_1.27X0.635MM_NO_SILK"))
    )
    (comp (ref "JP921")
      (value "M01PTH_SMD_1.27X0.635MM_NO_SILK")
      (footprint "eagle-import:1X01_SMD_1.27X0.635MM_NO_SILK")
      (libsource (lib "eagle-import") (part "M01PTH_SMD_1.27X0.635MM_NO_SILK"))
    )
    (comp (ref "JP922")
      (value "M01PTH_SMD_1.27X0.635MM_NO_SILK")
      (footprint "eagle-import:1X01_SMD_1.27X0.635MM_NO_SILK")
      (libsource (lib "eagle-import") (part "M01PTH_SMD_1.27X0.635MM_NO_SILK"))
    )
    (comp (ref "JP923")
      (value "M01PTH_SMD_1.27X0.635MM_NO_SILK")
      (footprint "eagle-import:1X01_SMD_1.27X0.635MM_NO_SILK")
      (libsource (lib "eagle-import") (part "M01PTH_SMD_1.27X0.635MM_NO_SILK"))
    )
    (comp (ref "JP924")
      (value "M01PTH_SMD_1.27X0.635MM_NO_SILK")
      (footprint "eagle-import:1X01_SMD_1.27X0.635MM_NO_SILK")
      (libsource (lib "eagle-import") (part "M01PTH_SMD_1.27X0.635MM_NO_SILK"))
    )
    (comp (ref "JP925")
      (value "M01PTH_SMD_1.27X0.635MM_NO_SILK")
      (footprint "eagle-import:1X01_SMD_1.27X0.635MM_NO_SILK")
      (libsource (lib "eagle-import") (part "M01PTH_SMD_1.27X0.635MM_NO_SILK"))
    )
    (comp (ref "JP926")
      (value "M01PTH_SMD_1.27X0.635MM_NO_SILK")
      (footprint "eagle-import:1X01_SMD_1.27X0.635MM_NO_SILK")
      (libsource (lib "eagle-import") (part "M01PTH_SMD_1.27X0.635MM_NO_SILK"))
    )
    (comp (ref "JP927")
      (value "M01PTH_SMD_1.27X0.635MM_NO_SILK")
      (footprint "eagle-import:1X01_SMD_1.27X0.635MM_NO_SILK")
      (libsource (lib "eagle-import") (part "M01PTH_SMD_1.27X0.635MM_NO_SILK"))
    )
    (comp (ref "JP928")
      (value "M01PTH_SMD_1.27X0.635MM_NO_SILK")
      (footprint "eagle-import:1X01_SMD_1.27X0.635MM_NO_SILK")
      (libsource (lib "eagle-import") (part "M01PTH_SMD_1.27X0.635MM_NO_SILK"))
    )
    (comp (ref "JP929")
      (value "M01PTH_SMD_1.27X0.635MM_NO_SILK")
      (footprint "eagle-import:1X01_SMD_1.27X0.635MM_NO_SILK")
      (libsource (lib "eagle-import") (part "M01PTH_SMD_1.27X0.635MM_NO_SILK"))
    )
    (comp (ref "JP930")
      (value "M01PTH_SMD_1.27X0.635MM_NO_SILK")
      (footprint "eagle-import:1X01_SMD_1.27X0.635MM_NO_SILK")
      (libsource (lib "eagle-import") (part "M01PTH_SMD_1.27X0.635MM_NO_SILK"))
    )
    (comp (ref "JP931")
      (value "M01PTH_SMD_1.27X0.635MM_NO_SILK")
      (footprint "eagle-import:1X01_SMD_1.27X0.635MM_NO_SILK")
      (libsource (lib "eagle-import") (part "M01PTH_SMD_1.27X0.635MM_NO_SILK"))
    )
    (comp (ref "JP932")
      (value "M01PTH_SMD_1.27X0.635MM_NO_SILK")
      (footprint "eagle-import:1X01_SMD_1.27X0.635MM_NO_SILK")
      (libsource (lib "eagle-import") (part "M01PTH_SMD_1.27X0.635MM_NO_SILK"))
    )
    (comp (ref "JP933")
      (value "M01PTH_SMD_1.27X0.635MM_NO_SILK")
      (footprint "eagle-import:1X01_SMD_1.27X0.635MM_NO_SILK")
      (libsource (lib "eagle-import") (part "M01PTH_SMD_1.27X0.635MM_NO_SILK"))
    )
    (comp (ref "JP934")
      (value "M01PTH_SMD_1.27X0.635MM_NO_SILK")
      (footprint "eagle-import:1X01_SMD_1.27X0.635MM_NO_SILK")
      (libsource (lib "eagle-import") (part "M01PTH_SMD_1.27X0.635MM_NO_SILK"))
    )
    (comp (ref "JP935")
      (value "M01PTH_SMD_1.27X0.635MM_NO_SILK")
      (footprint "eagle-import:1X01_SMD_1.27X0.635MM_NO_SILK")
      (libsource (lib "eagle-import") (part "M01PTH_SMD_1.27X0.635MM_NO_SILK"))
    )
    (comp (ref "JP936")
      (value "M01PTH_SMD_1.27X0.635MM_NO_SILK")
      (footprint "eagle-import:1X01_SMD_1.27X0.635MM_NO_SILK")
      (libsource (lib "eagle-import") (part "M01PTH_SMD_1.27X0.635MM_NO_SILK"))
    )
    (comp (ref "JP937")
      (value "M01PTH_SMD_1.27X0.635MM_NO_SILK")
      (footprint "eagle-import:1X01_SMD_1.27X0.635MM_NO_SILK")
      (libsource (lib "eagle-import") (part "M01PTH_SMD_1.27X0.635MM_NO_SILK"))
    )
    (comp (ref "JP938")
      (value "M01PTH_SMD_1.27X0.635MM_NO_SILK")
      (footprint "eagle-import:1X01_SMD_1.27X0.635MM_NO_SILK")
      (libsource (lib "eagle-import") (part "M01PTH_SMD_1.27X0.635MM_NO_SILK"))
    )
    (comp (ref "JP939")
      (value "M01PTH_SMD_1.27X0.635MM_NO_SILK")
      (footprint "eagle-import:1X01_SMD_1.27X0.635MM_NO_SILK")
      (libsource (lib "eagle-import") (part "M01PTH_SMD_1.27X0.635MM_NO_SILK"))
    )
    (comp (ref "JP940")
      (value "M01PTH_SMD_1.27X0.635MM_NO_SILK")
      (footprint "eagle-import:1X01_SMD_1.27X0.635MM_NO_SILK")
      (libsource (lib "eagle-import") (part "M01PTH_SMD_1.27X0.635MM_NO_SILK"))
    )
    (comp (ref "JP941")
      (value "M01PTH_SMD_1.27X0.635MM_NO_SILK")
      (footprint "eagle-import:1X01_SMD_1.27X0.635MM_NO_SILK")
      (libsource (lib "eagle-import") (part "M01PTH_SMD_1.27X0.635MM_NO_SILK"))
    )
    (comp (ref "JP942")
      (value "M01PTH_SMD_1.27X0.635MM_NO_SILK")
      (footprint "eagle-import:1X01_SMD_1.27X0.635MM_NO_SILK")
      (libsource (lib "eagle-import") (part "M01PTH_SMD_1.27X0.635MM_NO_SILK"))
    )
    (comp (ref "JP943")
      (value "M01PTH_SMD_1.27X0.635MM_NO_SILK")
      (footprint "eagle-import:1X01_SMD_1.27X0.635MM_NO_SILK")
      (libsource (lib "eagle-import") (part "M01PTH_SMD_1.27X0.635MM_NO_SILK"))
    )
    (comp (ref "JP944")
      (value "M01PTH_SMD_1.27X0.635MM_NO_SILK")
      (footprint "eagle-import:1X01_SMD_1.27X0.635MM_NO_SILK")
      (libsource (lib "eagle-import") (part "M01PTH_SMD_1.27X0.635MM_NO_SILK"))
    )
    (comp (ref "JP945")
      (value "M01PTH_SMD_1.27X0.635MM_NO_SILK")
      (footprint "eagle-import:1X01_SMD_1.27X0.635MM_NO_SILK")
      (libsource (lib "eagle-import") (part "M01PTH_SMD_1.27X0.635MM_NO_SILK"))
    )
    (comp (ref "JP946")
      (value "M01PTH_SMD_1.27X0.635MM_NO_SILK")
      (footprint "eagle-import:1X01_SMD_1.27X0.635MM_NO_SILK")
      (libsource (lib "eagle-import") (part "M01PTH_SMD_1.27X0.635MM_NO_SILK"))
    )
    (comp (ref "JP947")
      (value "M01PTH_SMD_1.27X0.635MM_NO_SILK")
      (footprint "eagle-import:1X01_SMD_1.27X0.635MM_NO_SILK")
      (libsource (lib "eagle-import") (part "M01PTH_SMD_1.27X0.635MM_NO_SILK"))
    )
    (comp (ref "JP948")
      (value "M01PTH_SMD_1.27X0.635MM_NO_SILK")
      (footprint "eagle-import:1X01_SMD_1.27X0.635MM_NO_SILK")
      (libsource (lib "eagle-import") (part "M01PTH_SMD_1.27X0.635MM_NO_SILK"))
    )
    (comp (ref "JP949")
      (value "M01PTH_SMD_1.27X0.635MM_NO_SILK")
      (footprint "eagle-import:1X01_SMD_1.27X0.635MM_NO_SILK")
      (libsource (lib "eagle-import") (part "M01PTH_SMD_1.27X0.635MM_NO_SILK"))
    )
    (comp (ref "JP950")
      (value "M01PTH_SMD_1.27X0.635MM_NO_SILK")
      (footprint "eagle-import:1X01_SMD_1.27X0.635MM_NO_SILK")
      (libsource (lib "eagle-import") (part "M01PTH_SMD_1.27X0.635MM_NO_SILK"))
    )
    (comp (ref "JP951")
      (value "M01PTH_SMD_1.27X0.635MM_NO_SILK")
      (footprint "eagle-import:1X01_SMD_1.27X0.635MM_NO_SILK")
      (libsource (lib "eagle-import") (part "M01PTH_SMD_1.27X0.635MM_NO_SILK"))
    )
    (comp (ref "JP952")
      (value "M01PTH_SMD_1.27X0.635MM_NO_SILK")
      (footprint "eagle-import:1X01_SMD_1.27X0.635MM_NO_SILK")
      (libsource (lib "eagle-import") (part "M01PTH_SMD_1.27X0.635MM_NO_SILK"))
    )
    (comp (ref "JP953")
      (value "M01PTH_SMD_1.27X0.635MM_NO_SILK")
      (footprint "eagle-import:1X01_SMD_1.27X0.635MM_NO_SILK")
      (libsource (lib "eagle-import") (part "M01PTH_SMD_1.27X0.635MM_NO_SILK"))
    )
    (comp (ref "JP954")
      (value "M01PTH_SMD_1.27X0.635MM_NO_SILK")
      (footprint "eagle-import:1X01_SMD_1.27X0.635MM_NO_SILK")
      (libsource (lib "eagle-import") (part "M01PTH_SMD_1.27X0.635MM_NO_SILK"))
    )
    (comp (ref "JP955")
      (value "M01PTH_SMD_1.27X0.635MM_NO_SILK")
      (footprint "eagle-import:1X01_SMD_1.27X0.635MM_NO_SILK")
      (libsource (lib "eagle-import") (part "M01PTH_SMD_1.27X0.635MM_NO_SILK"))
    )
    (comp (ref "JP956")
      (value "M01PTH_SMD_1.27X0.635MM_NO_SILK")
      (footprint "eagle-import:1X01_SMD_1.27X0.635MM_NO_SILK")
      (libsource (lib "eagle-import") (part "M01PTH_SMD_1.27X0.635MM_NO_SILK"))
    )
    (comp (ref "JP957")
      (value "M01PTH_SMD_1.27X0.635MM_NO_SILK")
      (footprint "eagle-import:1X01_SMD_1.27X0.635MM_NO_SILK")
      (libsource (lib "eagle-import") (part "M01PTH_SMD_1.27X0.635MM_NO_SILK"))
    )
    (comp (ref "JP958")
      (value "M01PTH_SMD_1.27X0.635MM_NO_SILK")
      (footprint "eagle-import:1X01_SMD_1.27X0.635MM_NO_SILK")
      (libsource (lib "eagle-import") (part "M01PTH_SMD_1.27X0.635MM_NO_SILK"))
    )
    (comp (ref "JP959")
      (value "M01PTH_SMD_1.27X0.635MM_NO_SILK")
      (footprint "eagle-import:1X01_SMD_1.27X0.635MM_NO_SILK")
      (libsource (lib "eagle-import") (part "M01PTH_SMD_1.27X0.635MM_NO_SILK"))
    )
    (comp (ref "JP960")
      (value "M01PTH_SMD_1.27X0.635MM_NO_SILK")
      (footprint "eagle-import:1X01_SMD_1.27X0.635MM_NO_SILK")
      (libsource (lib "eagle-import") (part "M01PTH_SMD_1.27X0.635MM_NO_SILK"))
    )
    (comp (ref "JP961")
      (value "M01PTH_SMD_1.27X0.635MM_NO_SILK")
      (footprint "eagle-import:1X01_SMD_1.27X0.635MM_NO_SILK")
      (libsource (lib "eagle-import") (part "M01PTH_SMD_1.27X0.635MM_NO_SILK"))
    )
    (comp (ref "JP962")
      (value "M01PTH_SMD_1.27X0.635MM_NO_SILK")
      (footprint "eagle-import:1X01_SMD_1.27X0.635MM_NO_SILK")
      (libsource (lib "eagle-import") (part "M01PTH_SMD_1.27X0.635MM_NO_SILK"))
    )
    (comp (ref "JP963")
      (value "M01PTH_SMD_1.27X0.635MM_NO_SILK")
      (footprint "eagle-import:1X01_SMD_1.27X0.635MM_NO_SILK")
      (libsource (lib "eagle-import") (part "M01PTH_SMD_1.27X0.635MM_NO_SILK"))
    )
    (comp (ref "JP964")
      (value "M01PTH_SMD_1.27X0.635MM_NO_SILK")
      (footprint "eagle-import:1X01_SMD_1.27X0.635MM_NO_SILK")
      (libsource (lib "eagle-import") (part "M01PTH_SMD_1.27X0.635MM_NO_SILK"))
    )
    (comp (ref "JP965")
      (value "M01PTH_SMD_1.27X0.635MM_NO_SILK")
      (footprint "eagle-import:1X01_SMD_1.27X0.635MM_NO_SILK")
      (libsource (lib "eagle-import") (part "M01PTH_SMD_1.27X0.635MM_NO_SILK"))
    )
    (comp (ref "JP966")
      (value "M01PTH_SMD_1.27X0.635MM_NO_SILK")
      (footprint "eagle-import:1X01_SMD_1.27X0.635MM_NO_SILK")
      (libsource (lib "eagle-import") (part "M01PTH_SMD_1.27X0.635MM_NO_SILK"))
    )
    (comp (ref "JP967")
      (value "M01PTH_SMD_1.27X0.635MM_NO_SILK")
      (footprint "eagle-import:1X01_SMD_1.27X0.635MM_NO_SILK")
      (libsource (lib "eagle-import") (part "M01PTH_SMD_1.27X0.635MM_NO_SILK"))
    )
    (comp (ref "JP968")
      (value "M01PTH_SMD_1.27X0.635MM_NO_SILK")
      (footprint "eagle-import:1X01_SMD_1.27X0.635MM_NO_SILK")
      (libsource (lib "eagle-import") (part "M01PTH_SMD_1.27X0.635MM_NO_SILK"))
    )
    (comp (ref "JP969")
      (value "M01PTH_SMD_1.27X0.635MM_NO_SILK")
      (footprint "eagle-import:1X01_SMD_1.27X0.635MM_NO_SILK")
      (libsource (lib "eagle-import") (part "M01PTH_SMD_1.27X0.635MM_NO_SILK"))
    )
    (comp (ref "JP970")
      (value "M01PTH_SMD_1.27X0.635MM_NO_SILK")
      (footprint "eagle-import:1X01_SMD_1.27X0.635MM_NO_SILK")
      (libsource (lib "eagle-import") (part "M01PTH_SMD_1.27X0.635MM_NO_SILK"))
    )
    (comp (ref "JP971")
      (value "M01PTH_SMD_1.27X0.635MM_NO_SILK")
      (footprint "eagle-import:1X01_SMD_1.27X0.635MM_NO_SILK")
      (libsource (lib "eagle-import") (part "M01PTH_SMD_1.27X0.635MM_NO_SILK"))
    )
    (comp (ref "JP972")
      (value "M01PTH_SMD_1.27X0.635MM_NO_SILK")
      (footprint "eagle-import:1X01_SMD_1.27X0.635MM_NO_SILK")
      (libsource (lib "eagle-import") (part "M01PTH_SMD_1.27X0.635MM_NO_SILK"))
    )
    (comp (ref "JP973")
      (value "M01PTH_SMD_1.27X0.635MM_NO_SILK")
      (footprint "eagle-import:1X01_SMD_1.27X0.635MM_NO_SILK")
      (libsource (lib "eagle-import") (part "M01PTH_SMD_1.27X0.635MM_NO_SILK"))
    )
    (comp (ref "JP974")
      (value "M01PTH_SMD_1.27X0.635MM_NO_SILK")
      (footprint "eagle-import:1X01_SMD_1.27X0.635MM_NO_SILK")
      (libsource (lib "eagle-import") (part "M01PTH_SMD_1.27X0.635MM_NO_SILK"))
    )
    (comp (ref "JP975")
      (value "M01PTH_SMD_1.27X0.635MM_NO_SILK")
      (footprint "eagle-import:1X01_SMD_1.27X0.635MM_NO_SILK")
      (libsource (lib "eagle-import") (part "M01PTH_SMD_1.27X0.635MM_NO_SILK"))
    )
    (comp (ref "JP976")
      (value "M01PTH_SMD_1.27X0.635MM_NO_SILK")
      (footprint "eagle-import:1X01_SMD_1.27X0.635MM_NO_SILK")
      (libsource (lib "eagle-import") (part "M01PTH_SMD_1.27X0.635MM_NO_SILK"))
    )
    (comp (ref "JP977")
      (value "M01PTH_SMD_1.27X0.635MM_NO_SILK")
      (footprint "eagle-import:1X01_SMD_1.27X0.635MM_NO_SILK")
      (libsource (lib "eagle-import") (part "M01PTH_SMD_1.27X0.635MM_NO_SILK"))
    )
    (comp (ref "JP978")
      (value "M01PTH_SMD_1.27X0.635MM_NO_SILK")
      (footprint "eagle-import:1X01_SMD_1.27X0.635MM_NO_SILK")
      (libsource (lib "eagle-import") (part "M01PTH_SMD_1.27X0.635MM_NO_SILK"))
    )
    (comp (ref "JP979")
      (value "M01PTH_SMD_1.27X0.635MM_NO_SILK")
      (footprint "eagle-import:1X01_SMD_1.27X0.635MM_NO_SILK")
      (libsource (lib "eagle-import") (part "M01PTH_SMD_1.27X0.635MM_NO_SILK"))
    )
    (comp (ref "JP980")
      (value "M01PTH_SMD_1.27X0.635MM_NO_SILK")
      (footprint "eagle-import:1X01_SMD_1.27X0.635MM_NO_SILK")
      (libsource (lib "eagle-import") (part "M01PTH_SMD_1.27X0.635MM_NO_SILK"))
    )
    (comp (ref "JP981")
      (value "M01PTH_SMD_1.27X0.635MM_NO_SILK")
      (footprint "eagle-import:1X01_SMD_1.27X0.635MM_NO_SILK")
      (libsource (lib "eagle-import") (part "M01PTH_SMD_1.27X0.635MM_NO_SILK"))
    )
    (comp (ref "JP982")
      (value "M01PTH_SMD_1.27X0.635MM_NO_SILK")
      (footprint "eagle-import:1X01_SMD_1.27X0.635MM_NO_SILK")
      (libsource (lib "eagle-import") (part "M01PTH_SMD_1.27X0.635MM_NO_SILK"))
    )
    (comp (ref "JP983")
      (value "M01PTH_SMD_1.27X0.635MM_NO_SILK")
      (footprint "eagle-import:1X01_SMD_1.27X0.635MM_NO_SILK")
      (libsource (lib "eagle-import") (part "M01PTH_SMD_1.27X0.635MM_NO_SILK"))
    )
    (comp (ref "JP984")
      (value "M01PTH_SMD_1.27X0.635MM_NO_SILK")
      (footprint "eagle-import:1X01_SMD_1.27X0.635MM_NO_SILK")
      (libsource (lib "eagle-import") (part "M01PTH_SMD_1.27X0.635MM_NO_SILK"))
    )
    (comp (ref "JP985")
      (value "M01PTH_SMD_1.27X0.635MM_NO_SILK")
      (footprint "eagle-import:1X01_SMD_1.27X0.635MM_NO_SILK")
      (libsource (lib "eagle-import") (part "M01PTH_SMD_1.27X0.635MM_NO_SILK"))
    )
    (comp (ref "JP986")
      (value "M01PTH_SMD_1.27X0.635MM_NO_SILK")
      (footprint "eagle-import:1X01_SMD_1.27X0.635MM_NO_SILK")
      (libsource (lib "eagle-import") (part "M01PTH_SMD_1.27X0.635MM_NO_SILK"))
    )
    (comp (ref "JP987")
      (value "M01PTH_SMD_1.27X0.635MM_NO_SILK")
      (footprint "eagle-import:1X01_SMD_1.27X0.635MM_NO_SILK")
      (libsource (lib "eagle-import") (part "M01PTH_SMD_1.27X0.635MM_NO_SILK"))
    )
    (comp (ref "JP988")
      (value "M01PTH_SMD_1.27X0.635MM_NO_SILK")
      (footprint "eagle-import:1X01_SMD_1.27X0.635MM_NO_SILK")
      (libsource (lib "eagle-import") (part "M01PTH_SMD_1.27X0.635MM_NO_SILK"))
    )
    (comp (ref "JP989")
      (value "M01PTH_SMD_1.27X0.635MM_NO_SILK")
      (footprint "eagle-import:1X01_SMD_1.27X0.635MM_NO_SILK")
      (libsource (lib "eagle-import") (part "M01PTH_SMD_1.27X0.635MM_NO_SILK"))
    )
    (comp (ref "JP990")
      (value "M01PTH_SMD_1.27X0.635MM_NO_SILK")
      (footprint "eagle-import:1X01_SMD_1.27X0.635MM_NO_SILK")
      (libsource (lib "eagle-import") (part "M01PTH_SMD_1.27X0.635MM_NO_SILK"))
    )
    (comp (ref "JP991")
      (value "M01PTH_SMD_1.27X0.635MM_NO_SILK")
      (footprint "eagle-import:1X01_SMD_1.27X0.635MM_NO_SILK")
      (libsource (lib "eagle-import") (part "M01PTH_SMD_1.27X0.635MM_NO_SILK"))
    )
    (comp (ref "JP992")
      (value "M01PTH_SMD_1.27X0.635MM_NO_SILK")
      (footprint "eagle-import:1X01_SMD_1.27X0.635MM_NO_SILK")
      (libsource (lib "eagle-import") (part "M01PTH_SMD_1.27X0.635MM_NO_SILK"))
    )
    (comp (ref "JP993")
      (value "M01PTH_SMD_1.27X0.635MM_NO_SILK")
      (footprint "eagle-import:1X01_SMD_1.27X0.635MM_NO_SILK")
      (libsource (lib "eagle-import") (part "M01PTH_SMD_1.27X0.635MM_NO_SILK"))
    )
    (comp (ref "JP994")
      (value "M01PTH_SMD_1.27X0.635MM_NO_SILK")
      (footprint "eagle-import:1X01_SMD_1.27X0.635MM_NO_SILK")
      (libsource (lib "eagle-import") (part "M01PTH_SMD_1.27X0.635MM_NO_SILK"))
    )
    (comp (ref "JP995")
      (value "M01PTH_SMD_1.27X0.635MM_NO_SILK")
      (footprint "eagle-import:1X01_SMD_1.27X0.635MM_NO_SILK")
      (libsource (lib "eagle-import") (part "M01PTH_SMD_1.27X0.635MM_NO_SILK"))
    )
    (comp (ref "JP996")
      (value "M01PTH_SMD_1.27X0.635MM_NO_SILK")
      (footprint "eagle-import:1X01_SMD_1.27X0.635MM_NO_SILK")
      (libsource (lib "eagle-import") (part "M01PTH_SMD_1.27X0.635MM_NO_SILK"))
    )
    (comp (ref "JP997")
      (value "M01PTH_SMD_1.27X0.635MM_NO_SILK")
      (footprint "eagle-import:1X01_SMD_1.27X0.635MM_NO_SILK")
      (libsource (lib "eagle-import") (part "M01PTH_SMD_1.27X0.635MM_NO_SILK"))
    )
    (comp (ref "JP998")
      (value "M01PTH_SMD_1.27X0.635MM_NO_SILK")
      (footprint "eagle-import:1X01_SMD_1.27X0.635MM_NO_SILK")
      (libsource (lib "eagle-import") (part "M01PTH_SMD_1.27X0.635MM_NO_SILK"))
    )
    (comp (ref "JP999")
      (value "M01PTH_SMD_1.27X0.635MM_NO_SILK")
      (footprint "eagle-import:1X01_SMD_1.27X0.635MM_NO_SILK")
      (libsource (lib "eagle-import") (part "M01PTH_SMD_1.27X0.635MM_NO_SILK"))
    )
    (comp (ref "JP1000")
      (value "M01PTH_SMD_1.27X0.635MM_NO_SILK")
      (footprint "eagle-import:1X01_SMD_1.27X0.635MM_NO_SILK")
      (libsource (lib "eagle-import") (part "M01PTH_SMD_1.27X0.635MM_NO_SILK"))
    )
    (comp (ref "JP1001")
      (value "M01PTH_SMD_1.27X0.635MM_NO_SILK")
      (footprint "eagle-import:1X01_SMD_1.27X0.635MM_NO_SILK")
      (libsource (lib "eagle-import") (part "M01PTH_SMD_1.27X0.635MM_NO_SILK"))
    )
    (comp (ref "JP1002")
      (value "M01PTH_SMD_1.27X0.635MM_NO_SILK")
      (footprint "eagle-import:1X01_SMD_1.27X0.635MM_NO_SILK")
      (libsource (lib "eagle-import") (part "M01PTH_SMD_1.27X0.635MM_NO_SILK"))
    )
    (comp (ref "JP1003")
      (value "M01PTH_SMD_1.27X0.635MM_NO_SILK")
      (footprint "eagle-import:1X01_SMD_1.27X0.635MM_NO_SILK")
      (libsource (lib "eagle-import") (part "M01PTH_SMD_1.27X0.635MM_NO_SILK"))
    )
    (comp (ref "JP1004")
      (value "M01PTH_SMD_1.27X0.635MM_NO_SILK")
      (footprint "eagle-import:1X01_SMD_1.27X0.635MM_NO_SILK")
      (libsource (lib "eagle-import") (part "M01PTH_SMD_1.27X0.635MM_NO_SILK"))
    )
    (comp (ref "JP1005")
      (value "M01PTH_SMD_1.27X0.635MM_NO_SILK")
      (footprint "eagle-import:1X01_SMD_1.27X0.635MM_NO_SILK")
      (libsource (lib "eagle-import") (part "M01PTH_SMD_1.27X0.635MM_NO_SILK"))
    )
    (comp (ref "JP1006")
      (value "M01PTH_SMD_1.27X0.635MM_NO_SILK")
      (footprint "eagle-import:1X01_SMD_1.27X0.635MM_NO_SILK")
      (libsource (lib "eagle-import") (part "M01PTH_SMD_1.27X0.635MM_NO_SILK"))
    )
    (comp (ref "JP1007")
      (value "M01PTH_SMD_1.27X0.635MM_NO_SILK")
      (footprint "eagle-import:1X01_SMD_1.27X0.635MM_NO_SILK")
      (libsource (lib "eagle-import") (part "M01PTH_SMD_1.27X0.635MM_NO_SILK"))
    )
    (comp (ref "JP1008")
      (value "M01PTH_SMD_1.27X0.635MM_NO_SILK")
      (footprint "eagle-import:1X01_SMD_1.27X0.635MM_NO_SILK")
      (libsource (lib "eagle-import") (part "M01PTH_SMD_1.27X0.635MM_NO_SILK"))
    )
    (comp (ref "JP1009")
      (value "M01PTH_SMD_1.27X0.635MM_NO_SILK")
      (footprint "eagle-import:1X01_SMD_1.27X0.635MM_NO_SILK")
      (libsource (lib "eagle-import") (part "M01PTH_SMD_1.27X0.635MM_NO_SILK"))
    )
    (comp (ref "JP1010")
      (value "M01PTH_SMD_1.27X0.635MM_NO_SILK")
      (footprint "eagle-import:1X01_SMD_1.27X0.635MM_NO_SILK")
      (libsource (lib "eagle-import") (part "M01PTH_SMD_1.27X0.635MM_NO_SILK"))
    )
    (comp (ref "JP1011")
      (value "M01PTH_SMD_1.27X0.635MM_NO_SILK")
      (footprint "eagle-import:1X01_SMD_1.27X0.635MM_NO_SILK")
      (libsource (lib "eagle-import") (part "M01PTH_SMD_1.27X0.635MM_NO_SILK"))
    )
    (comp (ref "JP1012")
      (value "M01PTH_SMD_1.27X0.635MM_NO_SILK")
      (footprint "eagle-import:1X01_SMD_1.27X0.635MM_NO_SILK")
      (libsource (lib "eagle-import") (part "M01PTH_SMD_1.27X0.635MM_NO_SILK"))
    )
    (comp (ref "JP1013")
      (value "M01PTH_SMD_1.27X0.635MM_NO_SILK")
      (footprint "eagle-import:1X01_SMD_1.27X0.635MM_NO_SILK")
      (libsource (lib "eagle-import") (part "M01PTH_SMD_1.27X0.635MM_NO_SILK"))
    )
    (comp (ref "JP1014")
      (value "M01PTH_SMD_1.27X0.635MM_NO_SILK")
      (footprint "eagle-import:1X01_SMD_1.27X0.635MM_NO_SILK")
      (libsource (lib "eagle-import") (part "M01PTH_SMD_1.27X0.635MM_NO_SILK"))
    )
    (comp (ref "JP1015")
      (value "M01PTH_SMD_1.27X0.635MM_NO_SILK")
      (footprint "eagle-import:1X01_SMD_1.27X0.635MM_NO_SILK")
      (libsource (lib "eagle-import") (part "M01PTH_SMD_1.27X0.635MM_NO_SILK"))
    )
    (comp (ref "JP1016")
      (value "M01PTH_SMD_1.27X0.635MM_NO_SILK")
      (footprint "eagle-import:1X01_SMD_1.27X0.635MM_NO_SILK")
      (libsource (lib "eagle-import") (part "M01PTH_SMD_1.27X0.635MM_NO_SILK"))
    )
    (comp (ref "JP1017")
      (value "M01PTH_SMD_1.27X0.635MM_NO_SILK")
      (footprint "eagle-import:1X01_SMD_1.27X0.635MM_NO_SILK")
      (libsource (lib "eagle-import") (part "M01PTH_SMD_1.27X0.635MM_NO_SILK"))
    )
    (comp (ref "JP1018")
      (value "M01PTH_SMD_1.27X0.635MM_NO_SILK")
      (footprint "eagle-import:1X01_SMD_1.27X0.635MM_NO_SILK")
      (libsource (lib "eagle-import") (part "M01PTH_SMD_1.27X0.635MM_NO_SILK"))
    )
    (comp (ref "JP1019")
      (value "M01PTH_SMD_1.27X0.635MM_NO_SILK")
      (footprint "eagle-import:1X01_SMD_1.27X0.635MM_NO_SILK")
      (libsource (lib "eagle-import") (part "M01PTH_SMD_1.27X0.635MM_NO_SILK"))
    )
    (comp (ref "JP1020")
      (value "M01PTH_SMD_1.27X0.635MM_NO_SILK")
      (footprint "eagle-import:1X01_SMD_1.27X0.635MM_NO_SILK")
      (libsource (lib "eagle-import") (part "M01PTH_SMD_1.27X0.635MM_NO_SILK"))
    )
    (comp (ref "JP1021")
      (value "M01PTH_SMD_1.27X0.635MM_NO_SILK")
      (footprint "eagle-import:1X01_SMD_1.27X0.635MM_NO_SILK")
      (libsource (lib "eagle-import") (part "M01PTH_SMD_1.27X0.635MM_NO_SILK"))
    )
    (comp (ref "JP1022")
      (value "M01PTH_SMD_1.27X0.635MM_NO_SILK")
      (footprint "eagle-import:1X01_SMD_1.27X0.635MM_NO_SILK")
      (libsource (lib "eagle-import") (part "M01PTH_SMD_1.27X0.635MM_NO_SILK"))
    )
    (comp (ref "JP1023")
      (value "M01PTH_SMD_1.27X0.635MM_NO_SILK")
      (footprint "eagle-import:1X01_SMD_1.27X0.635MM_NO_SILK")
      (libsource (lib "eagle-import") (part "M01PTH_SMD_1.27X0.635MM_NO_SILK"))
    )
    (comp (ref "JP1024")
      (value "M01PTH_SMD_1.27X0.635MM_NO_SILK")
      (footprint "eagle-import:1X01_SMD_1.27X0.635MM_NO_SILK")
      (libsource (lib "eagle-import") (part "M01PTH_SMD_1.27X0.635MM_NO_SILK"))
    )
    (comp (ref "JP1025")
      (value "M01PTH_SMD_1.27X0.635MM_NO_SILK")
      (footprint "eagle-import:1X01_SMD_1.27X0.635MM_NO_SILK")
      (libsource (lib "eagle-import") (part "M01PTH_SMD_1.27X0.635MM_NO_SILK"))
    )
    (comp (ref "JP1026")
      (value "M01PTH_SMD_1.27X0.635MM_NO_SILK")
      (footprint "eagle-import:1X01_SMD_1.27X0.635MM_NO_SILK")
      (libsource (lib "eagle-import") (part "M01PTH_SMD_1.27X0.635MM_NO_SILK"))
    )
    (comp (ref "JP1027")
      (value "M01PTH_SMD_1.27X0.635MM_NO_SILK")
      (footprint "eagle-import:1X01_SMD_1.27X0.635MM_NO_SILK")
      (libsource (lib "eagle-import") (part "M01PTH_SMD_1.27X0.635MM_NO_SILK"))
    )
    (comp (ref "JP1028")
      (value "M01PTH_SMD_1.27X0.635MM_NO_SILK")
      (footprint "eagle-import:1X01_SMD_1.27X0.635MM_NO_SILK")
      (libsource (lib "eagle-import") (part "M01PTH_SMD_1.27X0.635MM_NO_SILK"))
    )
    (comp (ref "JP1029")
      (value "M01PTH_SMD_1.27X0.635MM_NO_SILK")
      (footprint "eagle-import:1X01_SMD_1.27X0.635MM_NO_SILK")
      (libsource (lib "eagle-import") (part "M01PTH_SMD_1.27X0.635MM_NO_SILK"))
    )
    (comp (ref "JP1030")
      (value "M01PTH_SMD_1.27X0.635MM_NO_SILK")
      (footprint "eagle-import:1X01_SMD_1.27X0.635MM_NO_SILK")
      (libsource (lib "eagle-import") (part "M01PTH_SMD_1.27X0.635MM_NO_SILK"))
    )
    (comp (ref "JP1031")
      (value "M01PTH_SMD_1.27X0.635MM_NO_SILK")
      (footprint "eagle-import:1X01_SMD_1.27X0.635MM_NO_SILK")
      (libsource (lib "eagle-import") (part "M01PTH_SMD_1.27X0.635MM_NO_SILK"))
    )
    (comp (ref "JP1032")
      (value "M01PTH_SMD_1.27X0.635MM_NO_SILK")
      (footprint "eagle-import:1X01_SMD_1.27X0.635MM_NO_SILK")
      (libsource (lib "eagle-import") (part "M01PTH_SMD_1.27X0.635MM_NO_SILK"))
    )
    (comp (ref "JP1033")
      (value "M01PTH_SMD_1.27X0.635MM_NO_SILK")
      (footprint "eagle-import:1X01_SMD_1.27X0.635MM_NO_SILK")
      (libsource (lib "eagle-import") (part "M01PTH_SMD_1.27X0.635MM_NO_SILK"))
    )
    (comp (ref "JP1034")
      (value "M01PTH_SMD_1.27X0.635MM_NO_SILK")
      (footprint "eagle-import:1X01_SMD_1.27X0.635MM_NO_SILK")
      (libsource (lib "eagle-import") (part "M01PTH_SMD_1.27X0.635MM_NO_SILK"))
    )
    (comp (ref "JP1035")
      (value "M01PTH_SMD_1.27X0.635MM_NO_SILK")
      (footprint "eagle-import:1X01_SMD_1.27X0.635MM_NO_SILK")
      (libsource (lib "eagle-import") (part "M01PTH_SMD_1.27X0.635MM_NO_SILK"))
    )
    (comp (ref "JP1036")
      (value "M01PTH_SMD_1.27X0.635MM_NO_SILK")
      (footprint "eagle-import:1X01_SMD_1.27X0.635MM_NO_SILK")
      (libsource (lib "eagle-import") (part "M01PTH_SMD_1.27X0.635MM_NO_SILK"))
    )
    (comp (ref "JP1037")
      (value "M01PTH_SMD_1.27X0.635MM_NO_SILK")
      (footprint "eagle-import:1X01_SMD_1.27X0.635MM_NO_SILK")
      (libsource (lib "eagle-import") (part "M01PTH_SMD_1.27X0.635MM_NO_SILK"))
    )
    (comp (ref "JP1038")
      (value "M01PTH_SMD_1.27X0.635MM_NO_SILK")
      (footprint "eagle-import:1X01_SMD_1.27X0.635MM_NO_SILK")
      (libsource (lib "eagle-import") (part "M01PTH_SMD_1.27X0.635MM_NO_SILK"))
    )
    (comp (ref "JP1039")
      (value "M01PTH_SMD_1.27X0.635MM_NO_SILK")
      (footprint "eagle-import:1X01_SMD_1.27X0.635MM_NO_SILK")
      (libsource (lib "eagle-import") (part "M01PTH_SMD_1.27X0.635MM_NO_SILK"))
    )
    (comp (ref "JP1040")
      (value "M01PTH_SMD_1.27X0.635MM_NO_SILK")
      (footprint "eagle-import:1X01_SMD_1.27X0.635MM_NO_SILK")
      (libsource (lib "eagle-import") (part "M01PTH_SMD_1.27X0.635MM_NO_SILK"))
    )
    (comp (ref "JP1041")
      (value "M01PTH_SMD_1.27X0.635MM_NO_SILK")
      (footprint "eagle-import:1X01_SMD_1.27X0.635MM_NO_SILK")
      (libsource (lib "eagle-import") (part "M01PTH_SMD_1.27X0.635MM_NO_SILK"))
    )
    (comp (ref "JP1042")
      (value "M01PTH_SMD_1.27X0.635MM_NO_SILK")
      (footprint "eagle-import:1X01_SMD_1.27X0.635MM_NO_SILK")
      (libsource (lib "eagle-import") (part "M01PTH_SMD_1.27X0.635MM_NO_SILK"))
    )
    (comp (ref "JP1043")
      (value "M01PTH_SMD_1.27X0.635MM_NO_SILK")
      (footprint "eagle-import:1X01_SMD_1.27X0.635MM_NO_SILK")
      (libsource (lib "eagle-import") (part "M01PTH_SMD_1.27X0.635MM_NO_SILK"))
    )
    (comp (ref "JP1044")
      (value "M01PTH_SMD_1.27X0.635MM_NO_SILK")
      (footprint "eagle-import:1X01_SMD_1.27X0.635MM_NO_SILK")
      (libsource (lib "eagle-import") (part "M01PTH_SMD_1.27X0.635MM_NO_SILK"))
    )
    (comp (ref "JP1045")
      (value "M01PTH_SMD_1.27X0.635MM_NO_SILK")
      (footprint "eagle-import:1X01_SMD_1.27X0.635MM_NO_SILK")
      (libsource (lib "eagle-import") (part "M01PTH_SMD_1.27X0.635MM_NO_SILK"))
    )
    (comp (ref "JP1046")
      (value "M01PTH_SMD_1.27X0.635MM_NO_SILK")
      (footprint "eagle-import:1X01_SMD_1.27X0.635MM_NO_SILK")
      (libsource (lib "eagle-import") (part "M01PTH_SMD_1.27X0.635MM_NO_SILK"))
    )
    (comp (ref "JP1047")
      (value "M01PTH_SMD_1.27X0.635MM_NO_SILK")
      (footprint "eagle-import:1X01_SMD_1.27X0.635MM_NO_SILK")
      (libsource (lib "eagle-import") (part "M01PTH_SMD_1.27X0.635MM_NO_SILK"))
    )
    (comp (ref "JP1048")
      (value "M01PTH_SMD_1.27X0.635MM_NO_SILK")
      (footprint "eagle-import:1X01_SMD_1.27X0.635MM_NO_SILK")
      (libsource (lib "eagle-import") (part "M01PTH_SMD_1.27X0.635MM_NO_SILK"))
    )
    (comp (ref "JP1049")
      (value "M01PTH_SMD_1.27X0.635MM_NO_SILK")
      (footprint "eagle-import:1X01_SMD_1.27X0.635MM_NO_SILK")
      (libsource (lib "eagle-import") (part "M01PTH_SMD_1.27X0.635MM_NO_SILK"))
    )
    (comp (ref "JP1050")
      (value "M01PTH_SMD_1.27X0.635MM_NO_SILK")
      (footprint "eagle-import:1X01_SMD_1.27X0.635MM_NO_SILK")
      (libsource (lib "eagle-import") (part "M01PTH_SMD_1.27X0.635MM_NO_SILK"))
    )
    (comp (ref "JP1051")
      (value "M01PTH_SMD_1.27X0.635MM_NO_SILK")
      (footprint "eagle-import:1X01_SMD_1.27X0.635MM_NO_SILK")
      (libsource (lib "eagle-import") (part "M01PTH_SMD_1.27X0.635MM_NO_SILK"))
    )
    (comp (ref "JP1052")
      (value "M01PTH_SMD_1.27X0.635MM_NO_SILK")
      (footprint "eagle-import:1X01_SMD_1.27X0.635MM_NO_SILK")
      (libsource (lib "eagle-import") (part "M01PTH_SMD_1.27X0.635MM_NO_SILK"))
    )
    (comp (ref "JP1053")
      (value "M01PTH_SMD_1.27X0.635MM_NO_SILK")
      (footprint "eagle-import:1X01_SMD_1.27X0.635MM_NO_SILK")
      (libsource (lib "eagle-import") (part "M01PTH_SMD_1.27X0.635MM_NO_SILK"))
    )
    (comp (ref "JP1054")
      (value "M01PTH_SMD_1.27X0.635MM_NO_SILK")
      (footprint "eagle-import:1X01_SMD_1.27X0.635MM_NO_SILK")
      (libsource (lib "eagle-import") (part "M01PTH_SMD_1.27X0.635MM_NO_SILK"))
    )
    (comp (ref "JP1055")
      (value "M01PTH_SMD_1.27X0.635MM_NO_SILK")
      (footprint "eagle-import:1X01_SMD_1.27X0.635MM_NO_SILK")
      (libsource (lib "eagle-import") (part "M01PTH_SMD_1.27X0.635MM_NO_SILK"))
    )
    (comp (ref "JP1056")
      (value "M01PTH_SMD_1.27X0.635MM_NO_SILK")
      (footprint "eagle-import:1X01_SMD_1.27X0.635MM_NO_SILK")
      (libsource (lib "eagle-import") (part "M01PTH_SMD_1.27X0.635MM_NO_SILK"))
    )
    (comp (ref "JP1057")
      (value "M01PTH_SMD_1.27X0.635MM_NO_SILK")
      (footprint "eagle-import:1X01_SMD_1.27X0.635MM_NO_SILK")
      (libsource (lib "eagle-import") (part "M01PTH_SMD_1.27X0.635MM_NO_SILK"))
    )
    (comp (ref "JP1058")
      (value "M01PTH_SMD_1.27X0.635MM_NO_SILK")
      (footprint "eagle-import:1X01_SMD_1.27X0.635MM_NO_SILK")
      (libsource (lib "eagle-import") (part "M01PTH_SMD_1.27X0.635MM_NO_SILK"))
    )
    (comp (ref "JP1059")
      (value "M01PTH_SMD_1.27X0.635MM_NO_SILK")
      (footprint "eagle-import:1X01_SMD_1.27X0.635MM_NO_SILK")
      (libsource (lib "eagle-import") (part "M01PTH_SMD_1.27X0.635MM_NO_SILK"))
    )
    (comp (ref "JP1060")
      (value "M01PTH_SMD_1.27X0.635MM_NO_SILK")
      (footprint "eagle-import:1X01_SMD_1.27X0.635MM_NO_SILK")
      (libsource (lib "eagle-import") (part "M01PTH_SMD_1.27X0.635MM_NO_SILK"))
    )
    (comp (ref "JP1061")
      (value "M01PTH_SMD_1.27X0.635MM_NO_SILK")
      (footprint "eagle-import:1X01_SMD_1.27X0.635MM_NO_SILK")
      (libsource (lib "eagle-import") (part "M01PTH_SMD_1.27X0.635MM_NO_SILK"))
    )
    (comp (ref "JP1062")
      (value "M01PTH_SMD_1.27X0.635MM_NO_SILK")
      (footprint "eagle-import:1X01_SMD_1.27X0.635MM_NO_SILK")
      (libsource (lib "eagle-import") (part "M01PTH_SMD_1.27X0.635MM_NO_SILK"))
    )
    (comp (ref "JP1063")
      (value "M01PTH_SMD_1.27X0.635MM_NO_SILK")
      (footprint "eagle-import:1X01_SMD_1.27X0.635MM_NO_SILK")
      (libsource (lib "eagle-import") (part "M01PTH_SMD_1.27X0.635MM_NO_SILK"))
    )
    (comp (ref "JP1064")
      (value "M01PTH_SMD_1.27X0.635MM_NO_SILK")
      (footprint "eagle-import:1X01_SMD_1.27X0.635MM_NO_SILK")
      (libsource (lib "eagle-import") (part "M01PTH_SMD_1.27X0.635MM_NO_SILK"))
    )
    (comp (ref "JP1065")
      (value "M01PTH_SMD_1.27X0.635MM_NO_SILK")
      (footprint "eagle-import:1X01_SMD_1.27X0.635MM_NO_SILK")
      (libsource (lib "eagle-import") (part "M01PTH_SMD_1.27X0.635MM_NO_SILK"))
    )
    (comp (ref "JP1066")
      (value "M01PTH_SMD_1.27X0.635MM_NO_SILK")
      (footprint "eagle-import:1X01_SMD_1.27X0.635MM_NO_SILK")
      (libsource (lib "eagle-import") (part "M01PTH_SMD_1.27X0.635MM_NO_SILK"))
    )
    (comp (ref "JP1067")
      (value "M01PTH_SMD_1.27X0.635MM_NO_SILK")
      (footprint "eagle-import:1X01_SMD_1.27X0.635MM_NO_SILK")
      (libsource (lib "eagle-import") (part "M01PTH_SMD_1.27X0.635MM_NO_SILK"))
    )
    (comp (ref "JP1068")
      (value "M01PTH_SMD_1.27X0.635MM_NO_SILK")
      (footprint "eagle-import:1X01_SMD_1.27X0.635MM_NO_SILK")
      (libsource (lib "eagle-import") (part "M01PTH_SMD_1.27X0.635MM_NO_SILK"))
    )
    (comp (ref "JP1069")
      (value "M01PTH_SMD_1.27X0.635MM_NO_SILK")
      (footprint "eagle-import:1X01_SMD_1.27X0.635MM_NO_SILK")
      (libsource (lib "eagle-import") (part "M01PTH_SMD_1.27X0.635MM_NO_SILK"))
    )
    (comp (ref "JP1070")
      (value "M01PTH_SMD_1.27X0.635MM_NO_SILK")
      (footprint "eagle-import:1X01_SMD_1.27X0.635MM_NO_SILK")
      (libsource (lib "eagle-import") (part "M01PTH_SMD_1.27X0.635MM_NO_SILK"))
    )
    (comp (ref "JP1071")
      (value "M01PTH_SMD_1.27X0.635MM_NO_SILK")
      (footprint "eagle-import:1X01_SMD_1.27X0.635MM_NO_SILK")
      (libsource (lib "eagle-import") (part "M01PTH_SMD_1.27X0.635MM_NO_SILK"))
    )
    (comp (ref "JP1072")
      (value "M01PTH_SMD_1.27X0.635MM_NO_SILK")
      (footprint "eagle-import:1X01_SMD_1.27X0.635MM_NO_SILK")
      (libsource (lib "eagle-import") (part "M01PTH_SMD_1.27X0.635MM_NO_SILK"))
    )
    (comp (ref "JP1073")
      (value "M01PTH_SMD_1.27X0.635MM_NO_SILK")
      (footprint "eagle-import:1X01_SMD_1.27X0.635MM_NO_SILK")
      (libsource (lib "eagle-import") (part "M01PTH_SMD_1.27X0.635MM_NO_SILK"))
    )
    (comp (ref "JP1074")
      (value "M01PTH_SMD_1.27X0.635MM_NO_SILK")
      (footprint "eagle-import:1X01_SMD_1.27X0.635MM_NO_SILK")
      (libsource (lib "eagle-import") (part "M01PTH_SMD_1.27X0.635MM_NO_SILK"))
    )
    (comp (ref "JP1075")
      (value "M01PTH_SMD_1.27X0.635MM_NO_SILK")
      (footprint "eagle-import:1X01_SMD_1.27X0.635MM_NO_SILK")
      (libsource (lib "eagle-import") (part "M01PTH_SMD_1.27X0.635MM_NO_SILK"))
    )
    (comp (ref "JP1076")
      (value "M01PTH_SMD_1.27X0.635MM_NO_SILK")
      (footprint "eagle-import:1X01_SMD_1.27X0.635MM_NO_SILK")
      (libsource (lib "eagle-import") (part "M01PTH_SMD_1.27X0.635MM_NO_SILK"))
    )
    (comp (ref "JP1077")
      (value "M01PTH_SMD_1.27X0.635MM_NO_SILK")
      (footprint "eagle-import:1X01_SMD_1.27X0.635MM_NO_SILK")
      (libsource (lib "eagle-import") (part "M01PTH_SMD_1.27X0.635MM_NO_SILK"))
    )
    (comp (ref "JP1078")
      (value "M01PTH_SMD_1.27X0.635MM_NO_SILK")
      (footprint "eagle-import:1X01_SMD_1.27X0.635MM_NO_SILK")
      (libsource (lib "eagle-import") (part "M01PTH_SMD_1.27X0.635MM_NO_SILK"))
    )
    (comp (ref "JP1079")
      (value "M01PTH_SMD_1.27X0.635MM_NO_SILK")
      (footprint "eagle-import:1X01_SMD_1.27X0.635MM_NO_SILK")
      (libsource (lib "eagle-import") (part "M01PTH_SMD_1.27X0.635MM_NO_SILK"))
    )
    (comp (ref "JP1080")
      (value "M01PTH_SMD_1.27X0.635MM_NO_SILK")
      (footprint "eagle-import:1X01_SMD_1.27X0.635MM_NO_SILK")
      (libsource (lib "eagle-import") (part "M01PTH_SMD_1.27X0.635MM_NO_SILK"))
    )
    (comp (ref "JP1081")
      (value "M01PTH_SMD_1.27X0.635MM_NO_SILK")
      (footprint "eagle-import:1X01_SMD_1.27X0.635MM_NO_SILK")
      (libsource (lib "eagle-import") (part "M01PTH_SMD_1.27X0.635MM_NO_SILK"))
    )
    (comp (ref "JP1082")
      (value "M01PTH_SMD_1.27X0.635MM_NO_SILK")
      (footprint "eagle-import:1X01_SMD_1.27X0.635MM_NO_SILK")
      (libsource (lib "eagle-import") (part "M01PTH_SMD_1.27X0.635MM_NO_SILK"))
    )
    (comp (ref "JP1083")
      (value "M01PTH_SMD_1.27X0.635MM_NO_SILK")
      (footprint "eagle-import:1X01_SMD_1.27X0.635MM_NO_SILK")
      (libsource (lib "eagle-import") (part "M01PTH_SMD_1.27X0.635MM_NO_SILK"))
    )
    (comp (ref "JP1084")
      (value "M01PTH_SMD_1.27X0.635MM_NO_SILK")
      (footprint "eagle-import:1X01_SMD_1.27X0.635MM_NO_SILK")
      (libsource (lib "eagle-import") (part "M01PTH_SMD_1.27X0.635MM_NO_SILK"))
    )
    (comp (ref "JP1085")
      (value "M01PTH_SMD_1.27X0.635MM_NO_SILK")
      (footprint "eagle-import:1X01_SMD_1.27X0.635MM_NO_SILK")
      (libsource (lib "eagle-import") (part "M01PTH_SMD_1.27X0.635MM_NO_SILK"))
    )
    (comp (ref "JP1086")
      (value "M01PTH_SMD_1.27X0.635MM_NO_SILK")
      (footprint "eagle-import:1X01_SMD_1.27X0.635MM_NO_SILK")
      (libsource (lib "eagle-import") (part "M01PTH_SMD_1.27X0.635MM_NO_SILK"))
    )
    (comp (ref "JP1087")
      (value "M01PTH_SMD_1.27X0.635MM_NO_SILK")
      (footprint "eagle-import:1X01_SMD_1.27X0.635MM_NO_SILK")
      (libsource (lib "eagle-import") (part "M01PTH_SMD_1.27X0.635MM_NO_SILK"))
    )
    (comp (ref "JP1088")
      (value "M01PTH_SMD_1.27X0.635MM_NO_SILK")
      (footprint "eagle-import:1X01_SMD_1.27X0.635MM_NO_SILK")
      (libsource (lib "eagle-import") (part "M01PTH_SMD_1.27X0.635MM_NO_SILK"))
    )
    (comp (ref "JP1089")
      (value "M01PTH_SMD_1.27X0.635MM_NO_SILK")
      (footprint "eagle-import:1X01_SMD_1.27X0.635MM_NO_SILK")
      (libsource (lib "eagle-import") (part "M01PTH_SMD_1.27X0.635MM_NO_SILK"))
    )
    (comp (ref "JP1090")
      (value "M01PTH_SMD_1.27X0.635MM_NO_SILK")
      (footprint "eagle-import:1X01_SMD_1.27X0.635MM_NO_SILK")
      (libsource (lib "eagle-import") (part "M01PTH_SMD_1.27X0.635MM_NO_SILK"))
    )
    (comp (ref "JP1091")
      (value "M01PTH_SMD_1.27X0.635MM_NO_SILK")
      (footprint "eagle-import:1X01_SMD_1.27X0.635MM_NO_SILK")
      (libsource (lib "eagle-import") (part "M01PTH_SMD_1.27X0.635MM_NO_SILK"))
    )
    (comp (ref "JP1092")
      (value "M01PTH_SMD_1.27X0.635MM_NO_SILK")
      (footprint "eagle-import:1X01_SMD_1.27X0.635MM_NO_SILK")
      (libsource (lib "eagle-import") (part "M01PTH_SMD_1.27X0.635MM_NO_SILK"))
    )
    (comp (ref "JP1093")
      (value "M01PTH_SMD_1.27X0.635MM_NO_SILK")
      (footprint "eagle-import:1X01_SMD_1.27X0.635MM_NO_SILK")
      (libsource (lib "eagle-import") (part "M01PTH_SMD_1.27X0.635MM_NO_SILK"))
    )
    (comp (ref "JP1094")
      (value "M01PTH_SMD_1.27X0.635MM_NO_SILK")
      (footprint "eagle-import:1X01_SMD_1.27X0.635MM_NO_SILK")
      (libsource (lib "eagle-import") (part "M01PTH_SMD_1.27X0.635MM_NO_SILK"))
    )
    (comp (ref "JP1095")
      (value "M01PTH_SMD_1.27X0.635MM_NO_SILK")
      (footprint "eagle-import:1X01_SMD_1.27X0.635MM_NO_SILK")
      (libsource (lib "eagle-import") (part "M01PTH_SMD_1.27X0.635MM_NO_SILK"))
    )
    (comp (ref "JP1096")
      (value "M01PTH_SMD_1.27X0.635MM_NO_SILK")
      (footprint "eagle-import:1X01_SMD_1.27X0.635MM_NO_SILK")
      (libsource (lib "eagle-import") (part "M01PTH_SMD_1.27X0.635MM_NO_SILK"))
    )
    (comp (ref "JP1097")
      (value "M01PTH_SMD_1.27X0.635MM_NO_SILK")
      (footprint "eagle-import:1X01_SMD_1.27X0.635MM_NO_SILK")
      (libsource (lib "eagle-import") (part "M01PTH_SMD_1.27X0.635MM_NO_SILK"))
    )
    (comp (ref "JP1098")
      (value "M01PTH_SMD_1.27X0.635MM_NO_SILK")
      (footprint "eagle-import:1X01_SMD_1.27X0.635MM_NO_SILK")
      (libsource (lib "eagle-import") (part "M01PTH_SMD_1.27X0.635MM_NO_SILK"))
    )
    (comp (ref "JP1099")
      (value "M01PTH_SMD_1.27X0.635MM_NO_SILK")
      (footprint "eagle-import:1X01_SMD_1.27X0.635MM_NO_SILK")
      (libsource (lib "eagle-import") (part "M01PTH_SMD_1.27X0.635MM_NO_SILK"))
    )
    (comp (ref "JP1100")
      (value "M01PTH_SMD_1.27X0.635MM_NO_SILK")
      (footprint "eagle-import:1X01_SMD_1.27X0.635MM_NO_SILK")
      (libsource (lib "eagle-import") (part "M01PTH_SMD_1.27X0.635MM_NO_SILK"))
    )
    (comp (ref "JP1101")
      (value "M01PTH_SMD_1.27X0.635MM_NO_SILK")
      (footprint "eagle-import:1X01_SMD_1.27X0.635MM_NO_SILK")
      (libsource (lib "eagle-import") (part "M01PTH_SMD_1.27X0.635MM_NO_SILK"))
    )
    (comp (ref "JP1102")
      (value "M01PTH_SMD_1.27X0.635MM_NO_SILK")
      (footprint "eagle-import:1X01_SMD_1.27X0.635MM_NO_SILK")
      (libsource (lib "eagle-import") (part "M01PTH_SMD_1.27X0.635MM_NO_SILK"))
    )
    (comp (ref "JP1103")
      (value "M01PTH_SMD_1.27X0.635MM_NO_SILK")
      (footprint "eagle-import:1X01_SMD_1.27X0.635MM_NO_SILK")
      (libsource (lib "eagle-import") (part "M01PTH_SMD_1.27X0.635MM_NO_SILK"))
    )
    (comp (ref "JP1104")
      (value "M01PTH_SMD_1.27X0.635MM_NO_SILK")
      (footprint "eagle-import:1X01_SMD_1.27X0.635MM_NO_SILK")
      (libsource (lib "eagle-import") (part "M01PTH_SMD_1.27X0.635MM_NO_SILK"))
    )
    (comp (ref "JP1105")
      (value "M01PTH_SMD_1.27X0.635MM_NO_SILK")
      (footprint "eagle-import:1X01_SMD_1.27X0.635MM_NO_SILK")
      (libsource (lib "eagle-import") (part "M01PTH_SMD_1.27X0.635MM_NO_SILK"))
    )
    (comp (ref "JP1106")
      (value "M01PTH_SMD_1.27X0.635MM_NO_SILK")
      (footprint "eagle-import:1X01_SMD_1.27X0.635MM_NO_SILK")
      (libsource (lib "eagle-import") (part "M01PTH_SMD_1.27X0.635MM_NO_SILK"))
    )
    (comp (ref "JP1107")
      (value "M01PTH_SMD_1.27X0.635MM_NO_SILK")
      (footprint "eagle-import:1X01_SMD_1.27X0.635MM_NO_SILK")
      (libsource (lib "eagle-import") (part "M01PTH_SMD_1.27X0.635MM_NO_SILK"))
    )
    (comp (ref "JP1108")
      (value "M01PTH_SMD_1.27X0.635MM_NO_SILK")
      (footprint "eagle-import:1X01_SMD_1.27X0.635MM_NO_SILK")
      (libsource (lib "eagle-import") (part "M01PTH_SMD_1.27X0.635MM_NO_SILK"))
    )
    (comp (ref "JP1109")
      (value "M01PTH_SMD_1.27X0.635MM_NO_SILK")
      (footprint "eagle-import:1X01_SMD_1.27X0.635MM_NO_SILK")
      (libsource (lib "eagle-import") (part "M01PTH_SMD_1.27X0.635MM_NO_SILK"))
    )
    (comp (ref "JP1110")
      (value "M01PTH_SMD_1.27X0.635MM_NO_SILK")
      (footprint "eagle-import:1X01_SMD_1.27X0.635MM_NO_SILK")
      (libsource (lib "eagle-import") (part "M01PTH_SMD_1.27X0.635MM_NO_SILK"))
    )
    (comp (ref "JP1111")
      (value "M01PTH_SMD_1.27X0.635MM_NO_SILK")
      (footprint "eagle-import:1X01_SMD_1.27X0.635MM_NO_SILK")
      (libsource (lib "eagle-import") (part "M01PTH_SMD_1.27X0.635MM_NO_SILK"))
    )
    (comp (ref "JP1112")
      (value "M01PTH_SMD_1.27X0.635MM_NO_SILK")
      (footprint "eagle-import:1X01_SMD_1.27X0.635MM_NO_SILK")
      (libsource (lib "eagle-import") (part "M01PTH_SMD_1.27X0.635MM_NO_SILK"))
    )
    (comp (ref "JP1113")
      (value "M01PTH_SMD_1.27X0.635MM_NO_SILK")
      (footprint "eagle-import:1X01_SMD_1.27X0.635MM_NO_SILK")
      (libsource (lib "eagle-import") (part "M01PTH_SMD_1.27X0.635MM_NO_SILK"))
    )
    (comp (ref "JP1114")
      (value "M01PTH_SMD_1.27X0.635MM_NO_SILK")
      (footprint "eagle-import:1X01_SMD_1.27X0.635MM_NO_SILK")
      (libsource (lib "eagle-import") (part "M01PTH_SMD_1.27X0.635MM_NO_SILK"))
    )
    (comp (ref "JP1115")
      (value "M01PTH_SMD_1.27X0.635MM_NO_SILK")
      (footprint "eagle-import:1X01_SMD_1.27X0.635MM_NO_SILK")
      (libsource (lib "eagle-import") (part "M01PTH_SMD_1.27X0.635MM_NO_SILK"))
    )
    (comp (ref "JP1116")
      (value "M01PTH_SMD_1.27X0.635MM_NO_SILK")
      (footprint "eagle-import:1X01_SMD_1.27X0.635MM_NO_SILK")
      (libsource (lib "eagle-import") (part "M01PTH_SMD_1.27X0.635MM_NO_SILK"))
    )
    (comp (ref "JP1117")
      (value "M01PTH_SMD_1.27X0.635MM_NO_SILK")
      (footprint "eagle-import:1X01_SMD_1.27X0.635MM_NO_SILK")
      (libsource (lib "eagle-import") (part "M01PTH_SMD_1.27X0.635MM_NO_SILK"))
    )
    (comp (ref "JP1118")
      (value "M01PTH_SMD_1.27X0.635MM_NO_SILK")
      (footprint "eagle-import:1X01_SMD_1.27X0.635MM_NO_SILK")
      (libsource (lib "eagle-import") (part "M01PTH_SMD_1.27X0.635MM_NO_SILK"))
    )
    (comp (ref "JP1119")
      (value "M01PTH_SMD_1.27X0.635MM_NO_SILK")
      (footprint "eagle-import:1X01_SMD_1.27X0.635MM_NO_SILK")
      (libsource (lib "eagle-import") (part "M01PTH_SMD_1.27X0.635MM_NO_SILK"))
    )
    (comp (ref "JP1120")
      (value "M01PTH_SMD_1.27X0.635MM_NO_SILK")
      (footprint "eagle-import:1X01_SMD_1.27X0.635MM_NO_SILK")
      (libsource (lib "eagle-import") (part "M01PTH_SMD_1.27X0.635MM_NO_SILK"))
    )
    (comp (ref "JP1121")
      (value "M01PTH_SMD_1.27X0.635MM_NO_SILK")
      (footprint "eagle-import:1X01_SMD_1.27X0.635MM_NO_SILK")
      (libsource (lib "eagle-import") (part "M01PTH_SMD_1.27X0.635MM_NO_SILK"))
    )
    (comp (ref "JP1122")
      (value "M01PTH_SMD_1.27X0.635MM_NO_SILK")
      (footprint "eagle-import:1X01_SMD_1.27X0.635MM_NO_SILK")
      (libsource (lib "eagle-import") (part "M01PTH_SMD_1.27X0.635MM_NO_SILK"))
    )
    (comp (ref "JP1123")
      (value "M01PTH_SMD_1.27X0.635MM_NO_SILK")
      (footprint "eagle-import:1X01_SMD_1.27X0.635MM_NO_SILK")
      (libsource (lib "eagle-import") (part "M01PTH_SMD_1.27X0.635MM_NO_SILK"))
    )
    (comp (ref "JP1124")
      (value "M01PTH_SMD_1.27X0.635MM_NO_SILK")
      (footprint "eagle-import:1X01_SMD_1.27X0.635MM_NO_SILK")
      (libsource (lib "eagle-import") (part "M01PTH_SMD_1.27X0.635MM_NO_SILK"))
    )
    (comp (ref "JP1125")
      (value "M01PTH_SMD_1.27X0.635MM_NO_SILK")
      (footprint "eagle-import:1X01_SMD_1.27X0.635MM_NO_SILK")
      (libsource (lib "eagle-import") (part "M01PTH_SMD_1.27X0.635MM_NO_SILK"))
    )
    (comp (ref "JP1126")
      (value "M01PTH_SMD_1.27X0.635MM_NO_SILK")
      (footprint "eagle-import:1X01_SMD_1.27X0.635MM_NO_SILK")
      (libsource (lib "eagle-import") (part "M01PTH_SMD_1.27X0.635MM_NO_SILK"))
    )
    (comp (ref "JP1127")
      (value "M01PTH_SMD_1.27X0.635MM_NO_SILK")
      (footprint "eagle-import:1X01_SMD_1.27X0.635MM_NO_SILK")
      (libsource (lib "eagle-import") (part "M01PTH_SMD_1.27X0.635MM_NO_SILK"))
    )
    (comp (ref "JP1128")
      (value "M01PTH_SMD_1.27X0.635MM_NO_SILK")
      (footprint "eagle-import:1X01_SMD_1.27X0.635MM_NO_SILK")
      (libsource (lib "eagle-import") (part "M01PTH_SMD_1.27X0.635MM_NO_SILK"))
    )
    (comp (ref "JP1129")
      (value "M01PTH_SMD_1.27X0.635MM_NO_SILK")
      (footprint "eagle-import:1X01_SMD_1.27X0.635MM_NO_SILK")
      (libsource (lib "eagle-import") (part "M01PTH_SMD_1.27X0.635MM_NO_SILK"))
    )
    (comp (ref "JP1130")
      (value "M01PTH_SMD_1.27X0.635MM_NO_SILK")
      (footprint "eagle-import:1X01_SMD_1.27X0.635MM_NO_SILK")
      (libsource (lib "eagle-import") (part "M01PTH_SMD_1.27X0.635MM_NO_SILK"))
    )
    (comp (ref "JP1131")
      (value "M01PTH_SMD_1.27X0.635MM_NO_SILK")
      (footprint "eagle-import:1X01_SMD_1.27X0.635MM_NO_SILK")
      (libsource (lib "eagle-import") (part "M01PTH_SMD_1.27X0.635MM_NO_SILK"))
    )
    (comp (ref "JP1132")
      (value "M01PTH_SMD_1.27X0.635MM_NO_SILK")
      (footprint "eagle-import:1X01_SMD_1.27X0.635MM_NO_SILK")
      (libsource (lib "eagle-import") (part "M01PTH_SMD_1.27X0.635MM_NO_SILK"))
    )
    (comp (ref "JP1133")
      (value "M01PTH_SMD_1.27X0.635MM_NO_SILK")
      (footprint "eagle-import:1X01_SMD_1.27X0.635MM_NO_SILK")
      (libsource (lib "eagle-import") (part "M01PTH_SMD_1.27X0.635MM_NO_SILK"))
    )
    (comp (ref "JP1134")
      (value "M01PTH_SMD_1.27X0.635MM_NO_SILK")
      (footprint "eagle-import:1X01_SMD_1.27X0.635MM_NO_SILK")
      (libsource (lib "eagle-import") (part "M01PTH_SMD_1.27X0.635MM_NO_SILK"))
    )
    (comp (ref "JP1135")
      (value "M01PTH_SMD_1.27X0.635MM_NO_SILK")
      (footprint "eagle-import:1X01_SMD_1.27X0.635MM_NO_SILK")
      (libsource (lib "eagle-import") (part "M01PTH_SMD_1.27X0.635MM_NO_SILK"))
    )
    (comp (ref "JP1136")
      (value "M01PTH_SMD_1.27X0.635MM_NO_SILK")
      (footprint "eagle-import:1X01_SMD_1.27X0.635MM_NO_SILK")
      (libsource (lib "eagle-import") (part "M01PTH_SMD_1.27X0.635MM_NO_SILK"))
    )
    (comp (ref "JP1137")
      (value "M01PTH_SMD_1.27X0.635MM_NO_SILK")
      (footprint "eagle-import:1X01_SMD_1.27X0.635MM_NO_SILK")
      (libsource (lib "eagle-import") (part "M01PTH_SMD_1.27X0.635MM_NO_SILK"))
    )
    (comp (ref "JP1138")
      (value "M01PTH_SMD_1.27X0.635MM_NO_SILK")
      (footprint "eagle-import:1X01_SMD_1.27X0.635MM_NO_SILK")
      (libsource (lib "eagle-import") (part "M01PTH_SMD_1.27X0.635MM_NO_SILK"))
    )
    (comp (ref "JP1139")
      (value "M01PTH_SMD_1.27X0.635MM_NO_SILK")
      (footprint "eagle-import:1X01_SMD_1.27X0.635MM_NO_SILK")
      (libsource (lib "eagle-import") (part "M01PTH_SMD_1.27X0.635MM_NO_SILK"))
    )
    (comp (ref "JP1140")
      (value "M01PTH_SMD_1.27X0.635MM_NO_SILK")
      (footprint "eagle-import:1X01_SMD_1.27X0.635MM_NO_SILK")
      (libsource (lib "eagle-import") (part "M01PTH_SMD_1.27X0.635MM_NO_SILK"))
    )
    (comp (ref "JP1141")
      (value "M01PTH_SMD_1.27X0.635MM_NO_SILK")
      (footprint "eagle-import:1X01_SMD_1.27X0.635MM_NO_SILK")
      (libsource (lib "eagle-import") (part "M01PTH_SMD_1.27X0.635MM_NO_SILK"))
    )
    (comp (ref "JP1142")
      (value "M01PTH_SMD_1.27X0.635MM_NO_SILK")
      (footprint "eagle-import:1X01_SMD_1.27X0.635MM_NO_SILK")
      (libsource (lib "eagle-import") (part "M01PTH_SMD_1.27X0.635MM_NO_SILK"))
    )
    (comp (ref "JP1143")
      (value "M01PTH_SMD_1.27X0.635MM_NO_SILK")
      (footprint "eagle-import:1X01_SMD_1.27X0.635MM_NO_SILK")
      (libsource (lib "eagle-import") (part "M01PTH_SMD_1.27X0.635MM_NO_SILK"))
    )
    (comp (ref "JP1144")
      (value "M01PTH_SMD_1.27X0.635MM_NO_SILK")
      (footprint "eagle-import:1X01_SMD_1.27X0.635MM_NO_SILK")
      (libsource (lib "eagle-import") (part "M01PTH_SMD_1.27X0.635MM_NO_SILK"))
    )
    (comp (ref "JP1145")
      (value "M01PTH_SMD_1.27X0.635MM_NO_SILK")
      (footprint "eagle-import:1X01_SMD_1.27X0.635MM_NO_SILK")
      (libsource (lib "eagle-import") (part "M01PTH_SMD_1.27X0.635MM_NO_SILK"))
    )
    (comp (ref "JP1146")
      (value "M01PTH_SMD_1.27X0.635MM_NO_SILK")
      (footprint "eagle-import:1X01_SMD_1.27X0.635MM_NO_SILK")
      (libsource (lib "eagle-import") (part "M01PTH_SMD_1.27X0.635MM_NO_SILK"))
    )
    (comp (ref "JP1147")
      (value "M01PTH_SMD_1.27X0.635MM_NO_SILK")
      (footprint "eagle-import:1X01_SMD_1.27X0.635MM_NO_SILK")
      (libsource (lib "eagle-import") (part "M01PTH_SMD_1.27X0.635MM_NO_SILK"))
    )
    (comp (ref "JP1148")
      (value "M01PTH_SMD_1.27X0.635MM_NO_SILK")
      (footprint "eagle-import:1X01_SMD_1.27X0.635MM_NO_SILK")
      (libsource (lib "eagle-import") (part "M01PTH_SMD_1.27X0.635MM_NO_SILK"))
    )
    (comp (ref "JP1149")
      (value "M01PTH_SMD_1.27X0.635MM_NO_SILK")
      (footprint "eagle-import:1X01_SMD_1.27X0.635MM_NO_SILK")
      (libsource (lib "eagle-import") (part "M01PTH_SMD_1.27X0.635MM_NO_SILK"))
    )
    (comp (ref "JP1150")
      (value "M01PTH_SMD_1.27X0.635MM_NO_SILK")
      (footprint "eagle-import:1X01_SMD_1.27X0.635MM_NO_SILK")
      (libsource (lib "eagle-import") (part "M01PTH_SMD_1.27X0.635MM_NO_SILK"))
    )
    (comp (ref "JP1151")
      (value "M01PTH_SMD_1.27X0.635MM_NO_SILK")
      (footprint "eagle-import:1X01_SMD_1.27X0.635MM_NO_SILK")
      (libsource (lib "eagle-import") (part "M01PTH_SMD_1.27X0.635MM_NO_SILK"))
    )
    (comp (ref "JP1152")
      (value "M01PTH_SMD_1.27X0.635MM_NO_SILK")
      (footprint "eagle-import:1X01_SMD_1.27X0.635MM_NO_SILK")
      (libsource (lib "eagle-import") (part "M01PTH_SMD_1.27X0.635MM_NO_SILK"))
    )
    (comp (ref "JP1153")
      (value "M01PTH_SMD_1.27X0.635MM_NO_SILK")
      (footprint "eagle-import:1X01_SMD_1.27X0.635MM_NO_SILK")
      (libsource (lib "eagle-import") (part "M01PTH_SMD_1.27X0.635MM_NO_SILK"))
    )
    (comp (ref "JP1154")
      (value "M01PTH_SMD_1.27X0.635MM_NO_SILK")
      (footprint "eagle-import:1X01_SMD_1.27X0.635MM_NO_SILK")
      (libsource (lib "eagle-import") (part "M01PTH_SMD_1.27X0.635MM_NO_SILK"))
    )
    (comp (ref "JP1155")
      (value "M01PTH_SMD_1.27X0.635MM_NO_SILK")
      (footprint "eagle-import:1X01_SMD_1.27X0.635MM_NO_SILK")
      (libsource (lib "eagle-import") (part "M01PTH_SMD_1.27X0.635MM_NO_SILK"))
    )
    (comp (ref "JP1156")
      (value "M01PTH_SMD_1.27X0.635MM_NO_SILK")
      (footprint "eagle-import:1X01_SMD_1.27X0.635MM_NO_SILK")
      (libsource (lib "eagle-import") (part "M01PTH_SMD_1.27X0.635MM_NO_SILK"))
    )
    (comp (ref "JP1157")
      (value "M01PTH_SMD_1.27X0.635MM_NO_SILK")
      (footprint "eagle-import:1X01_SMD_1.27X0.635MM_NO_SILK")
      (libsource (lib "eagle-import") (part "M01PTH_SMD_1.27X0.635MM_NO_SILK"))
    )
    (comp (ref "JP1158")
      (value "M01PTH_SMD_1.27X0.635MM_NO_SILK")
      (footprint "eagle-import:1X01_SMD_1.27X0.635MM_NO_SILK")
      (libsource (lib "eagle-import") (part "M01PTH_SMD_1.27X0.635MM_NO_SILK"))
    )
    (comp (ref "JP1159")
      (value "M01PTH_SMD_1.27X0.635MM_NO_SILK")
      (footprint "eagle-import:1X01_SMD_1.27X0.635MM_NO_SILK")
      (libsource (lib "eagle-import") (part "M01PTH_SMD_1.27X0.635MM_NO_SILK"))
    )
    (comp (ref "JP1160")
      (value "M01PTH_SMD_1.27X0.635MM_NO_SILK")
      (footprint "eagle-import:1X01_SMD_1.27X0.635MM_NO_SILK")
      (libsource (lib "eagle-import") (part "M01PTH_SMD_1.27X0.635MM_NO_SILK"))
    )
    (comp (ref "JP1161")
      (value "M01PTH_SMD_1.27X0.635MM_NO_SILK")
      (footprint "eagle-import:1X01_SMD_1.27X0.635MM_NO_SILK")
      (libsource (lib "eagle-import") (part "M01PTH_SMD_1.27X0.635MM_NO_SILK"))
    )
    (comp (ref "JP1162")
      (value "M01PTH_SMD_1.27X0.635MM_NO_SILK")
      (footprint "eagle-import:1X01_SMD_1.27X0.635MM_NO_SILK")
      (libsource (lib "eagle-import") (part "M01PTH_SMD_1.27X0.635MM_NO_SILK"))
    )
    (comp (ref "JP1163")
      (value "M01PTH_SMD_1.27X0.635MM_NO_SILK")
      (footprint "eagle-import:1X01_SMD_1.27X0.635MM_NO_SILK")
      (libsource (lib "eagle-import") (part "M01PTH_SMD_1.27X0.635MM_NO_SILK"))
    )
    (comp (ref "JP1164")
      (value "M01PTH_SMD_1.27X0.635MM_NO_SILK")
      (footprint "eagle-import:1X01_SMD_1.27X0.635MM_NO_SILK")
      (libsource (lib "eagle-import") (part "M01PTH_SMD_1.27X0.635MM_NO_SILK"))
    )
    (comp (ref "JP1165")
      (value "M01PTH_SMD_1.27X0.635MM_NO_SILK")
      (footprint "eagle-import:1X01_SMD_1.27X0.635MM_NO_SILK")
      (libsource (lib "eagle-import") (part "M01PTH_SMD_1.27X0.635MM_NO_SILK"))
    )
    (comp (ref "JP1166")
      (value "M01PTH_SMD_1.27X0.635MM_NO_SILK")
      (footprint "eagle-import:1X01_SMD_1.27X0.635MM_NO_SILK")
      (libsource (lib "eagle-import") (part "M01PTH_SMD_1.27X0.635MM_NO_SILK"))
    )
    (comp (ref "JP1167")
      (value "M01PTH_SMD_1.27X0.635MM_NO_SILK")
      (footprint "eagle-import:1X01_SMD_1.27X0.635MM_NO_SILK")
      (libsource (lib "eagle-import") (part "M01PTH_SMD_1.27X0.635MM_NO_SILK"))
    )
    (comp (ref "JP1168")
      (value "M01PTH_SMD_1.27X0.635MM_NO_SILK")
      (footprint "eagle-import:1X01_SMD_1.27X0.635MM_NO_SILK")
      (libsource (lib "eagle-import") (part "M01PTH_SMD_1.27X0.635MM_NO_SILK"))
    )
    (comp (ref "JP1169")
      (value "M01PTH_SMD_1.27X0.635MM_NO_SILK")
      (footprint "eagle-import:1X01_SMD_1.27X0.635MM_NO_SILK")
      (libsource (lib "eagle-import") (part "M01PTH_SMD_1.27X0.635MM_NO_SILK"))
    )
    (comp (ref "JP1170")
      (value "M01PTH_SMD_1.27X0.635MM_NO_SILK")
      (footprint "eagle-import:1X01_SMD_1.27X0.635MM_NO_SILK")
      (libsource (lib "eagle-import") (part "M01PTH_SMD_1.27X0.635MM_NO_SILK"))
    )
    (comp (ref "JP1171")
      (value "M01PTH_SMD_1.27X0.635MM_NO_SILK")
      (footprint "eagle-import:1X01_SMD_1.27X0.635MM_NO_SILK")
      (libsource (lib "eagle-import") (part "M01PTH_SMD_1.27X0.635MM_NO_SILK"))
    )
    (comp (ref "JP1172")
      (value "M01PTH_SMD_1.27X0.635MM_NO_SILK")
      (footprint "eagle-import:1X01_SMD_1.27X0.635MM_NO_SILK")
      (libsource (lib "eagle-import") (part "M01PTH_SMD_1.27X0.635MM_NO_SILK"))
    )
    (comp (ref "JP1173")
      (value "M01PTH_SMD_1.27X0.635MM_NO_SILK")
      (footprint "eagle-import:1X01_SMD_1.27X0.635MM_NO_SILK")
      (libsource (lib "eagle-import") (part "M01PTH_SMD_1.27X0.635MM_NO_SILK"))
    )
    (comp (ref "JP1174")
      (value "M01PTH_SMD_1.27X0.635MM_NO_SILK")
      (footprint "eagle-import:1X01_SMD_1.27X0.635MM_NO_SILK")
      (libsource (lib "eagle-import") (part "M01PTH_SMD_1.27X0.635MM_NO_SILK"))
    )
    (comp (ref "JP1175")
      (value "M01PTH_SMD_1.27X0.635MM_NO_SILK")
      (footprint "eagle-import:1X01_SMD_1.27X0.635MM_NO_SILK")
      (libsource (lib "eagle-import") (part "M01PTH_SMD_1.27X0.635MM_NO_SILK"))
    )
    (comp (ref "JP1176")
      (value "M01PTH_SMD_1.27X0.635MM_NO_SILK")
      (footprint "eagle-import:1X01_SMD_1.27X0.635MM_NO_SILK")
      (libsource (lib "eagle-import") (part "M01PTH_SMD_1.27X0.635MM_NO_SILK"))
    )
    (comp (ref "JP1177")
      (value "M01PTH_SMD_1.27X0.635MM_NO_SILK")
      (footprint "eagle-import:1X01_SMD_1.27X0.635MM_NO_SILK")
      (libsource (lib "eagle-import") (part "M01PTH_SMD_1.27X0.635MM_NO_SILK"))
    )
    (comp (ref "JP1178")
      (value "M01PTH_SMD_1.27X0.635MM_NO_SILK")
      (footprint "eagle-import:1X01_SMD_1.27X0.635MM_NO_SILK")
      (libsource (lib "eagle-import") (part "M01PTH_SMD_1.27X0.635MM_NO_SILK"))
    )
    (comp (ref "JP1179")
      (value "M01PTH_SMD_1.27X0.635MM_NO_SILK")
      (footprint "eagle-import:1X01_SMD_1.27X0.635MM_NO_SILK")
      (libsource (lib "eagle-import") (part "M01PTH_SMD_1.27X0.635MM_NO_SILK"))
    )
    (comp (ref "JP1180")
      (value "M01PTH_SMD_1.27X0.635MM_NO_SILK")
      (footprint "eagle-import:1X01_SMD_1.27X0.635MM_NO_SILK")
      (libsource (lib "eagle-import") (part "M01PTH_SMD_1.27X0.635MM_NO_SILK"))
    )
    (comp (ref "JP1181")
      (value "M01PTH_SMD_1.27X0.635MM_NO_SILK")
      (footprint "eagle-import:1X01_SMD_1.27X0.635MM_NO_SILK")
      (libsource (lib "eagle-import") (part "M01PTH_SMD_1.27X0.635MM_NO_SILK"))
    )
    (comp (ref "JP1182")
      (value "M01PTH_SMD_1.27X0.635MM_NO_SILK")
      (footprint "eagle-import:1X01_SMD_1.27X0.635MM_NO_SILK")
      (libsource (lib "eagle-import") (part "M01PTH_SMD_1.27X0.635MM_NO_SILK"))
    )
    (comp (ref "JP1183")
      (value "M01PTH_SMD_1.27X0.635MM_NO_SILK")
      (footprint "eagle-import:1X01_SMD_1.27X0.635MM_NO_SILK")
      (libsource (lib "eagle-import") (part "M01PTH_SMD_1.27X0.635MM_NO_SILK"))
    )
    (comp (ref "JP1184")
      (value "M01PTH_SMD_1.27X0.635MM_NO_SILK")
      (footprint "eagle-import:1X01_SMD_1.27X0.635MM_NO_SILK")
      (libsource (lib "eagle-import") (part "M01PTH_SMD_1.27X0.635MM_NO_SILK"))
    )
    (comp (ref "JP1185")
      (value "M01PTH_SMD_1.27X0.635MM_NO_SILK")
      (footprint "eagle-import:1X01_SMD_1.27X0.635MM_NO_SILK")
      (libsource (lib "eagle-import") (part "M01PTH_SMD_1.27X0.635MM_NO_SILK"))
    )
    (comp (ref "JP1186")
      (value "M01PTH_SMD_1.27X0.635MM_NO_SILK")
      (footprint "eagle-import:1X01_SMD_1.27X0.635MM_NO_SILK")
      (libsource (lib "eagle-import") (part "M01PTH_SMD_1.27X0.635MM_NO_SILK"))
    )
    (comp (ref "JP1187")
      (value "M01PTH_SMD_1.27X0.635MM_NO_SILK")
      (footprint "eagle-import:1X01_SMD_1.27X0.635MM_NO_SILK")
      (libsource (lib "eagle-import") (part "M01PTH_SMD_1.27X0.635MM_NO_SILK"))
    )
    (comp (ref "JP1188")
      (value "M01PTH_SMD_1.27X0.635MM_NO_SILK")
      (footprint "eagle-import:1X01_SMD_1.27X0.635MM_NO_SILK")
      (libsource (lib "eagle-import") (part "M01PTH_SMD_1.27X0.635MM_NO_SILK"))
    )
    (comp (ref "JP1189")
      (value "M01PTH_SMD_1.27X0.635MM_NO_SILK")
      (footprint "eagle-import:1X01_SMD_1.27X0.635MM_NO_SILK")
      (libsource (lib "eagle-import") (part "M01PTH_SMD_1.27X0.635MM_NO_SILK"))
    )
    (comp (ref "JP1190")
      (value "M01PTH_SMD_1.27X0.635MM_NO_SILK")
      (footprint "eagle-import:1X01_SMD_1.27X0.635MM_NO_SILK")
      (libsource (lib "eagle-import") (part "M01PTH_SMD_1.27X0.635MM_NO_SILK"))
    )
    (comp (ref "JP1191")
      (value "M01PTH_SMD_1.27X0.635MM_NO_SILK")
      (footprint "eagle-import:1X01_SMD_1.27X0.635MM_NO_SILK")
      (libsource (lib "eagle-import") (part "M01PTH_SMD_1.27X0.635MM_NO_SILK"))
    )
    (comp (ref "JP1192")
      (value "M01PTH_SMD_1.27X0.635MM_NO_SILK")
      (footprint "eagle-import:1X01_SMD_1.27X0.635MM_NO_SILK")
      (libsource (lib "eagle-import") (part "M01PTH_SMD_1.27X0.635MM_NO_SILK"))
    )
    (comp (ref "JP1193")
      (value "M01PTH_SMD_1.27X0.635MM_NO_SILK")
      (footprint "eagle-import:1X01_SMD_1.27X0.635MM_NO_SILK")
      (libsource (lib "eagle-import") (part "M01PTH_SMD_1.27X0.635MM_NO_SILK"))
    )
    (comp (ref "JP1194")
      (value "M01PTH_SMD_1.27X0.635MM_NO_SILK")
      (footprint "eagle-import:1X01_SMD_1.27X0.635MM_NO_SILK")
      (libsource (lib "eagle-import") (part "M01PTH_SMD_1.27X0.635MM_NO_SILK"))
    )
    (comp (ref "JP1195")
      (value "M01PTH_SMD_1.27X0.635MM_NO_SILK")
      (footprint "eagle-import:1X01_SMD_1.27X0.635MM_NO_SILK")
      (libsource (lib "eagle-import") (part "M01PTH_SMD_1.27X0.635MM_NO_SILK"))
    )
    (comp (ref "JP1196")
      (value "M01PTH_SMD_1.27X0.635MM_NO_SILK")
      (footprint "eagle-import:1X01_SMD_1.27X0.635MM_NO_SILK")
      (libsource (lib "eagle-import") (part "M01PTH_SMD_1.27X0.635MM_NO_SILK"))
    )
    (comp (ref "JP1197")
      (value "M01PTH_SMD_1.27X0.635MM_NO_SILK")
      (footprint "eagle-import:1X01_SMD_1.27X0.635MM_NO_SILK")
      (libsource (lib "eagle-import") (part "M01PTH_SMD_1.27X0.635MM_NO_SILK"))
    )
    (comp (ref "JP1198")
      (value "M01PTH_SMD_1.27X0.635MM_NO_SILK")
      (footprint "eagle-import:1X01_SMD_1.27X0.635MM_NO_SILK")
      (libsource (lib "eagle-import") (part "M01PTH_SMD_1.27X0.635MM_NO_SILK"))
    )
    (comp (ref "JP1199")
      (value "M01PTH_SMD_1.27X0.635MM_NO_SILK")
      (footprint "eagle-import:1X01_SMD_1.27X0.635MM_NO_SILK")
      (libsource (lib "eagle-import") (part "M01PTH_SMD_1.27X0.635MM_NO_SILK"))
    )
    (comp (ref "JP1200")
      (value "M01PTH_SMD_1.27X0.635MM_NO_SILK")
      (footprint "eagle-import:1X01_SMD_1.27X0.635MM_NO_SILK")
      (libsource (lib "eagle-import") (part "M01PTH_SMD_1.27X0.635MM_NO_SILK"))
    )
  )
  (nets
    (net (code "1") (name "/NEW_0") (class "Default")
      (node (ref "JP10") (pin "1") (pinfunction "1_1") (pintype "passive"))
      (node (ref "JP1021") (pin "P$2") (pinfunction "1_P$2") (pintype "passive"))
    )
    (net (code "2") (name "/NEW_1") (class "Default")
      (node (ref "JP1081") (pin "P$2") (pinfunction "1_P$2") (pintype "passive"))
      (node (ref "JP7") (pin "1") (pinfunction "1_1") (pintype "passive"))
    )
    (net (code "3") (name "/NEW_2") (class "Default")
      (node (ref "JP1022") (pin "P$2") (pinfunction "1_P$2") (pintype "passive"))
      (node (ref "JP8") (pin "1") (pinfunction "1_1") (pintype "passive"))
    )
    (net (code "4") (name "/NEW_3") (class "Default")
      (node (ref "JP1082") (pin "P$2") (pinfunction "1_P$2") (pintype "passive"))
      (node (ref "JP9") (pin "1") (pinfunction "1_1") (pintype "passive"))
    )
    (net (code "5") (name "/NEW_4") (class "Default")
      (node (ref "JP1023") (pin "P$2") (pinfunction "1_P$2") (pintype "passive"))
      (node (ref "JP20") (pin "1") (pinfunction "1_1") (pintype "passive"))
    )
    (net (code "6") (name "/NEW_5") (class "Default")
      (node (ref "JP1083") (pin "P$2") (pinfunction "1_P$2") (pintype "passive"))
      (node (ref "JP18") (pin "1") (pinfunction "1_1") (pintype "passive"))
    )
    (net (code "7") (name "/NEW_6") (class "Default")
      (node (ref "JP1024") (pin "P$2") (pinfunction "1_P$2") (pintype "passive"))
      (node (ref "JP19") (pin "1") (pinfunction "1_1") (pintype "passive"))
    )
    (net (code "8") (name "/NEW_7") (class "Default")
      (node (ref "JP1084") (pin "P$2") (pinfunction "1_P$2") (pintype "passive"))
      (node (ref "JP17") (pin "1") (pinfunction "1_1") (pintype "passive"))
    )
    (net (code "9") (name "/NEW_8") (class "Default")
      (node (ref "JP1025") (pin "P$2") (pinfunction "1_P$2") (pintype "passive"))
      (node (ref "JP30") (pin "1") (pinfunction "1_1") (pintype "passive"))
    )
    (net (code "10") (name "/NEW_9") (class "Default")
      (node (ref "JP1085") (pin "P$2") (pinfunction "1_P$2") (pintype "passive"))
      (node (ref "JP29") (pin "1") (pinfunction "1_1") (pintype "passive"))
    )
    (net (code "11") (name "/NEW_10") (class "Default")
      (node (ref "JP1026") (pin "P$2") (pinfunction "1_P$2") (pintype "passive"))
      (node (ref "JP28") (pin "1") (pinfunction "1_1") (pintype "passive"))
    )
    (net (code "12") (name "/NEW_11") (class "Default")
      (node (ref "JP1086") (pin "P$2") (pinfunction "1_P$2") (pintype "passive"))
      (node (ref "JP27") (pin "1") (pinfunction "1_1") (pintype "passive"))
    )
    (net (code "13") (name "/NEW_12") (class "Default")
      (node (ref "JP1027") (pin "P$2") (pinfunction "1_P$2") (pintype "passive"))
      (node (ref "JP40") (pin "1") (pinfunction "1_1") (pintype "passive"))
    )
    (net (code "14") (name "/NEW_13") (class "Default")
      (node (ref "JP1087") (pin "P$2") (pinfunction "1_P$2") (pintype "passive"))
      (node (ref "JP39") (pin "1") (pinfunction "1_1") (pintype "passive"))
    )
    (net (code "15") (name "/NEW_14") (class "Default")
      (node (ref "JP1028") (pin "P$2") (pinfunction "1_P$2") (pintype "passive"))
      (node (ref "JP37") (pin "1") (pinfunction "1_1") (pintype "passive"))
    )
    (net (code "16") (name "/NEW_15") (class "Default")
      (node (ref "JP1088") (pin "P$2") (pinfunction "1_P$2") (pintype "passive"))
      (node (ref "JP38") (pin "1") (pinfunction "1_1") (pintype "passive"))
    )
    (net (code "17") (name "/NEW_16") (class "Default")
      (node (ref "JP1029") (pin "P$2") (pinfunction "1_P$2") (pintype "passive"))
      (node (ref "JP50") (pin "1") (pinfunction "1_1") (pintype "passive"))
    )
    (net (code "18") (name "/NEW_17") (class "Default")
      (node (ref "JP1089") (pin "P$2") (pinfunction "1_P$2") (pintype "passive"))
      (node (ref "JP49") (pin "1") (pinfunction "1_1") (pintype "passive"))
    )
    (net (code "19") (name "/NEW_18") (class "Default")
      (node (ref "JP1030") (pin "P$2") (pinfunction "1_P$2") (pintype "passive"))
      (node (ref "JP48") (pin "1") (pinfunction "1_1") (pintype "passive"))
    )
    (net (code "20") (name "/NEW_19") (class "Default")
      (node (ref "JP1090") (pin "P$2") (pinfunction "1_P$2") (pintype "passive"))
      (node (ref "JP47") (pin "1") (pinfunction "1_1") (pintype "passive"))
    )
    (net (code "21") (name "/NEW_20") (class "Default")
      (node (ref "JP1031") (pin "P$2") (pinfunction "1_P$2") (pintype "passive"))
      (node (ref "JP60") (pin "1") (pinfunction "1_1") (pintype "passive"))
    )
    (net (code "22") (name "/NEW_21") (class "Default")
      (node (ref "JP1091") (pin "P$2") (pinfunction "1_P$2") (pintype "passive"))
      (node (ref "JP59") (pin "1") (pinfunction "1_1") (pintype "passive"))
    )
    (net (code "23") (name "/NEW_22") (class "Default")
      (node (ref "JP1032") (pin "P$2") (pinfunction "1_P$2") (pintype "passive"))
      (node (ref "JP58") (pin "1") (pinfunction "1_1") (pintype "passive"))
    )
    (net (code "24") (name "/NEW_23") (class "Default")
      (node (ref "JP1092") (pin "P$2") (pinfunction "1_P$2") (pintype "passive"))
      (node (ref "JP57") (pin "1") (pinfunction "1_1") (pintype "passive"))
    )
    (net (code "25") (name "/NEW_24") (class "Default")
      (node (ref "JP1033") (pin "P$2") (pinfunction "1_P$2") (pintype "passive"))
      (node (ref "JP68") (pin "1") (pinfunction "1_1") (pintype "passive"))
    )
    (net (code "26") (name "/NEW_25") (class "Default")
      (node (ref "JP1093") (pin "P$2") (pinfunction "1_P$2") (pintype "passive"))
      (node (ref "JP67") (pin "1") (pinfunction "1_1") (pintype "passive"))
    )
    (net (code "27") (name "/NEW_26") (class "Default")
      (node (ref "JP1034") (pin "P$2") (pinfunction "1_P$2") (pintype "passive"))
      (node (ref "JP70") (pin "1") (pinfunction "1_1") (pintype "passive"))
    )
    (net (code "28") (name "/NEW_27") (class "Default")
      (node (ref "JP1094") (pin "P$2") (pinfunction "1_P$2") (pintype "passive"))
      (node (ref "JP69") (pin "1") (pinfunction "1_1") (pintype "passive"))
    )
    (net (code "29") (name "/NEW_28") (class "Default")
      (node (ref "JP1035") (pin "P$2") (pinfunction "1_P$2") (pintype "passive"))
      (node (ref "JP78") (pin "1") (pinfunction "1_1") (pintype "passive"))
    )
    (net (code "30") (name "/NEW_29") (class "Default")
      (node (ref "JP1095") (pin "P$2") (pinfunction "1_P$2") (pintype "passive"))
      (node (ref "JP77") (pin "1") (pinfunction "1_1") (pintype "passive"))
    )
    (net (code "31") (name "/NEW_30") (class "Default")
      (node (ref "JP1036") (pin "P$2") (pinfunction "1_P$2") (pintype "passive"))
      (node (ref "JP80") (pin "1") (pinfunction "1_1") (pintype "passive"))
    )
    (net (code "32") (name "/NEW_31") (class "Default")
      (node (ref "JP1096") (pin "P$2") (pinfunction "1_P$2") (pintype "passive"))
      (node (ref "JP79") (pin "1") (pinfunction "1_1") (pintype "passive"))
    )
    (net (code "33") (name "/NEW_32") (class "Default")
      (node (ref "JP1037") (pin "P$2") (pinfunction "1_P$2") (pintype "passive"))
      (node (ref "JP88") (pin "1") (pinfunction "1_1") (pintype "passive"))
    )
    (net (code "34") (name "/NEW_33") (class "Default")
      (node (ref "JP1097") (pin "P$2") (pinfunction "1_P$2") (pintype "passive"))
      (node (ref "JP87") (pin "1") (pinfunction "1_1") (pintype "passive"))
    )
    (net (code "35") (name "/NEW_34") (class "Default")
      (node (ref "JP1038") (pin "P$2") (pinfunction "1_P$2") (pintype "passive"))
      (node (ref "JP90") (pin "1") (pinfunction "1_1") (pintype "passive"))
    )
    (net (code "36") (name "/NEW_35") (class "Default")
      (node (ref "JP1098") (pin "P$2") (pinfunction "1_P$2") (pintype "passive"))
      (node (ref "JP89") (pin "1") (pinfunction "1_1") (pintype "passive"))
    )
    (net (code "37") (name "/NEW_36") (class "Default")
      (node (ref "JP1039") (pin "P$2") (pinfunction "1_P$2") (pintype "passive"))
      (node (ref "JP98") (pin "1") (pinfunction "1_1") (pintype "passive"))
    )
    (net (code "38") (name "/NEW_37") (class "Default")
      (node (ref "JP1099") (pin "P$2") (pinfunction "1_P$2") (pintype "passive"))
      (node (ref "JP97") (pin "1") (pinfunction "1_1") (pintype "passive"))
    )
    (net (code "39") (name "/NEW_38") (class "Default")
      (node (ref "JP100") (pin "1") (pinfunction "1_1") (pintype "passive"))
      (node (ref "JP1040") (pin "P$2") (pinfunction "1_P$2") (pintype "passive"))
    )
    (net (code "40") (name "/NEW_39") (class "Default")
      (node (ref "JP1100") (pin "P$2") (pinfunction "1_P$2") (pintype "passive"))
      (node (ref "JP99") (pin "1") (pinfunction "1_1") (pintype "passive"))
    )
    (net (code "41") (name "/NEW_40") (class "Default")
      (node (ref "JP1041") (pin "P$2") (pinfunction "1_P$2") (pintype "passive"))
      (node (ref "JP108") (pin "1") (pinfunction "1_1") (pintype "passive"))
    )
    (net (code "42") (name "/NEW_41") (class "Default")
      (node (ref "JP107") (pin "1") (pinfunction "1_1") (pintype "passive"))
      (node (ref "JP1101") (pin "P$2") (pinfunction "1_P$2") (pintype "passive"))
    )
    (net (code "43") (name "/NEW_42") (class "Default")
      (node (ref "JP1042") (pin "P$2") (pinfunction "1_P$2") (pintype "passive"))
      (node (ref "JP110") (pin "1") (pinfunction "1_1") (pintype "passive"))
    )
    (net (code "44") (name "/NEW_43") (class "Default")
      (node (ref "JP109") (pin "1") (pinfunction "1_1") (pintype "passive"))
      (node (ref "JP1102") (pin "P$2") (pinfunction "1_P$2") (pintype "passive"))
    )
    (net (code "45") (name "/NEW_44") (class "Default")
      (node (ref "JP1043") (pin "P$2") (pinfunction "1_P$2") (pintype "passive"))
      (node (ref "JP118") (pin "1") (pinfunction "1_1") (pintype "passive"))
    )
    (net (code "46") (name "/NEW_45") (class "Default")
      (node (ref "JP1103") (pin "P$2") (pinfunction "1_P$2") (pintype "passive"))
      (node (ref "JP117") (pin "1") (pinfunction "1_1") (pintype "passive"))
    )
    (net (code "47") (name "/NEW_46") (class "Default")
      (node (ref "JP1044") (pin "P$2") (pinfunction "1_P$2") (pintype "passive"))
      (node (ref "JP120") (pin "1") (pinfunction "1_1") (pintype "passive"))
    )
    (net (code "48") (name "/NEW_47") (class "Default")
      (node (ref "JP1104") (pin "P$2") (pinfunction "1_P$2") (pintype "passive"))
      (node (ref "JP119") (pin "1") (pinfunction "1_1") (pintype "passive"))
    )
    (net (code "49") (name "/NEW_48") (class "Default")
      (node (ref "JP1045") (pin "P$2") (pinfunction "1_P$2") (pintype "passive"))
      (node (ref "JP128") (pin "1") (pinfunction "1_1") (pintype "passive"))
    )
    (net (code "50") (name "/NEW_49") (class "Default")
      (node (ref "JP1105") (pin "P$2") (pinfunction "1_P$2") (pintype "passive"))
      (node (ref "JP127") (pin "1") (pinfunction "1_1") (pintype "passive"))
    )
    (net (code "51") (name "/NEW_50") (class "Default")
      (node (ref "JP1046") (pin "P$2") (pinfunction "1_P$2") (pintype "passive"))
      (node (ref "JP130") (pin "1") (pinfunction "1_1") (pintype "passive"))
    )
    (net (code "52") (name "/NEW_51") (class "Default")
      (node (ref "JP1106") (pin "P$2") (pinfunction "1_P$2") (pintype "passive"))
      (node (ref "JP129") (pin "1") (pinfunction "1_1") (pintype "passive"))
    )
    (net (code "53") (name "/NEW_52") (class "Default")
      (node (ref "JP1047") (pin "P$2") (pinfunction "1_P$2") (pintype "passive"))
      (node (ref "JP138") (pin "1") (pinfunction "1_1") (pintype "passive"))
    )
    (net (code "54") (name "/NEW_53") (class "Default")
      (node (ref "JP1107") (pin "P$2") (pinfunction "1_P$2") (pintype "passive"))
      (node (ref "JP137") (pin "1") (pinfunction "1_1") (pintype "passive"))
    )
    (net (code "55") (name "/NEW_54") (class "Default")
      (node (ref "JP1048") (pin "P$2") (pinfunction "1_P$2") (pintype "passive"))
      (node (ref "JP140") (pin "1") (pinfunction "1_1") (pintype "passive"))
    )
    (net (code "56") (name "/NEW_55") (class "Default")
      (node (ref "JP1108") (pin "P$2") (pinfunction "1_P$2") (pintype "passive"))
      (node (ref "JP139") (pin "1") (pinfunction "1_1") (pintype "passive"))
    )
    (net (code "57") (name "/NEW_56") (class "Default")
      (node (ref "JP1049") (pin "P$2") (pinfunction "1_P$2") (pintype "passive"))
      (node (ref "JP148") (pin "1") (pinfunction "1_1") (pintype "passive"))
    )
    (net (code "58") (name "/NEW_57") (class "Default")
      (node (ref "JP1109") (pin "P$2") (pinfunction "1_P$2") (pintype "passive"))
      (node (ref "JP147") (pin "1") (pinfunction "1_1") (pintype "passive"))
    )
    (net (code "59") (name "/NEW_58") (class "Default")
      (node (ref "JP1050") (pin "P$2") (pinfunction "1_P$2") (pintype "passive"))
      (node (ref "JP150") (pin "1") (pinfunction "1_1") (pintype "passive"))
    )
    (net (code "60") (name "/NEW_59") (class "Default")
      (node (ref "JP1110") (pin "P$2") (pinfunction "1_P$2") (pintype "passive"))
      (node (ref "JP149") (pin "1") (pinfunction "1_1") (pintype "passive"))
    )
    (net (code "61") (name "/NEW_60") (class "Default")
      (node (ref "JP1051") (pin "P$2") (pinfunction "1_P$2") (pintype "passive"))
      (node (ref "JP158") (pin "1") (pinfunction "1_1") (pintype "passive"))
    )
    (net (code "62") (name "/NEW_61") (class "Default")
      (node (ref "JP1111") (pin "P$2") (pinfunction "1_P$2") (pintype "passive"))
      (node (ref "JP157") (pin "1") (pinfunction "1_1") (pintype "passive"))
    )
    (net (code "63") (name "/NEW_62") (class "Default")
      (node (ref "JP1052") (pin "P$2") (pinfunction "1_P$2") (pintype "passive"))
      (node (ref "JP160") (pin "1") (pinfunction "1_1") (pintype "passive"))
    )
    (net (code "64") (name "/NEW_63") (class "Default")
      (node (ref "JP1112") (pin "P$2") (pinfunction "1_P$2") (pintype "passive"))
      (node (ref "JP159") (pin "1") (pinfunction "1_1") (pintype "passive"))
    )
    (net (code "65") (name "/NEW_64") (class "Default")
      (node (ref "JP1053") (pin "P$2") (pinfunction "1_P$2") (pintype "passive"))
      (node (ref "JP168") (pin "1") (pinfunction "1_1") (pintype "passive"))
    )
    (net (code "66") (name "/NEW_65") (class "Default")
      (node (ref "JP1113") (pin "P$2") (pinfunction "1_P$2") (pintype "passive"))
      (node (ref "JP167") (pin "1") (pinfunction "1_1") (pintype "passive"))
    )
    (net (code "67") (name "/NEW_66") (class "Default")
      (node (ref "JP1054") (pin "P$2") (pinfunction "1_P$2") (pintype "passive"))
      (node (ref "JP170") (pin "1") (pinfunction "1_1") (pintype "passive"))
    )
    (net (code "68") (name "/NEW_67") (class "Default")
      (node (ref "JP1114") (pin "P$2") (pinfunction "1_P$2") (pintype "passive"))
      (node (ref "JP169") (pin "1") (pinfunction "1_1") (pintype "passive"))
    )
    (net (code "69") (name "/NEW_68") (class "Default")
      (node (ref "JP1055") (pin "P$2") (pinfunction "1_P$2") (pintype "passive"))
      (node (ref "JP178") (pin "1") (pinfunction "1_1") (pintype "passive"))
    )
    (net (code "70") (name "/NEW_69") (class "Default")
      (node (ref "JP1115") (pin "P$2") (pinfunction "1_P$2") (pintype "passive"))
      (node (ref "JP177") (pin "1") (pinfunction "1_1") (pintype "passive"))
    )
    (net (code "71") (name "/NEW_70") (class "Default")
      (node (ref "JP1056") (pin "P$2") (pinfunction "1_P$2") (pintype "passive"))
      (node (ref "JP180") (pin "1") (pinfunction "1_1") (pintype "passive"))
    )
    (net (code "72") (name "/NEW_71") (class "Default")
      (node (ref "JP1116") (pin "P$2") (pinfunction "1_P$2") (pintype "passive"))
      (node (ref "JP179") (pin "1") (pinfunction "1_1") (pintype "passive"))
    )
    (net (code "73") (name "/NEW_72") (class "Default")
      (node (ref "JP1057") (pin "P$2") (pinfunction "1_P$2") (pintype "passive"))
      (node (ref "JP188") (pin "1") (pinfunction "1_1") (pintype "passive"))
    )
    (net (code "74") (name "/NEW_73") (class "Default")
      (node (ref "JP1117") (pin "P$2") (pinfunction "1_P$2") (pintype "passive"))
      (node (ref "JP187") (pin "1") (pinfunction "1_1") (pintype "passive"))
    )
    (net (code "75") (name "/NEW_74") (class "Default")
      (node (ref "JP1058") (pin "P$2") (pinfunction "1_P$2") (pintype "passive"))
      (node (ref "JP190") (pin "1") (pinfunction "1_1") (pintype "passive"))
    )
    (net (code "76") (name "/NEW_75") (class "Default")
      (node (ref "JP1118") (pin "P$2") (pinfunction "1_P$2") (pintype "passive"))
      (node (ref "JP189") (pin "1") (pinfunction "1_1") (pintype "passive"))
    )
    (net (code "77") (name "/NEW_76") (class "Default")
      (node (ref "JP1059") (pin "P$2") (pinfunction "1_P$2") (pintype "passive"))
      (node (ref "JP198") (pin "1") (pinfunction "1_1") (pintype "passive"))
    )
    (net (code "78") (name "/NEW_77") (class "Default")
      (node (ref "JP1119") (pin "P$2") (pinfunction "1_P$2") (pintype "passive"))
      (node (ref "JP248") (pin "1") (pinfunction "1_1") (pintype "passive"))
    )
    (net (code "79") (name "/NEW_78") (class "Default")
      (node (ref "JP1060") (pin "P$2") (pinfunction "1_P$2") (pintype "passive"))
      (node (ref "JP197") (pin "1") (pinfunction "1_1") (pintype "passive"))
    )
    (net (code "80") (name "/NEW_79") (class "Default")
      (node (ref "JP1120") (pin "P$2") (pinfunction "1_P$2") (pintype "passive"))
      (node (ref "JP258") (pin "1") (pinfunction "1_1") (pintype "passive"))
    )
    (net (code "81") (name "/NEW_80") (class "Default")
      (node (ref "JP1061") (pin "P$2") (pinfunction "1_P$2") (pintype "passive"))
      (node (ref "JP208") (pin "1") (pinfunction "1_1") (pintype "passive"))
    )
    (net (code "82") (name "/NEW_81") (class "Default")
      (node (ref "JP1121") (pin "P$2") (pinfunction "1_P$2") (pintype "passive"))
      (node (ref "JP257") (pin "1") (pinfunction "1_1") (pintype "passive"))
    )
    (net (code "83") (name "/NEW_82") (class "Default")
      (node (ref "JP1062") (pin "P$2") (pinfunction "1_P$2") (pintype "passive"))
      (node (ref "JP207") (pin "1") (pinfunction "1_1") (pintype "passive"))
    )
    (net (code "84") (name "/NEW_83") (class "Default")
      (node (ref "JP1122") (pin "P$2") (pinfunction "1_P$2") (pintype "passive"))
      (node (ref "JP268") (pin "1") (pinfunction "1_1") (pintype "passive"))
    )
    (net (code "85") (name "/NEW_84") (class "Default")
      (node (ref "JP1063") (pin "P$2") (pinfunction "1_P$2") (pintype "passive"))
      (node (ref "JP218") (pin "1") (pinfunction "1_1") (pintype "passive"))
    )
    (net (code "86") (name "/NEW_85") (class "Default")
      (node (ref "JP1123") (pin "P$2") (pinfunction "1_P$2") (pintype "passive"))
      (node (ref "JP267") (pin "1") (pinfunction "1_1") (pintype "passive"))
    )
    (net (code "87") (name "/NEW_86") (class "Default")
      (node (ref "JP1064") (pin "P$2") (pinfunction "1_P$2") (pintype "passive"))
      (node (ref "JP217") (pin "1") (pinfunction "1_1") (pintype "passive"))
    )
    (net (code "88") (name "/NEW_87") (class "Default")
      (node (ref "JP1124") (pin "P$2") (pinfunction "1_P$2") (pintype "passive"))
      (node (ref "JP278") (pin "1") (pinfunction "1_1") (pintype "passive"))
    )
    (net (code "89") (name "/NEW_88") (class "Default")
      (node (ref "JP1065") (pin "P$2") (pinfunction "1_P$2") (pintype "passive"))
      (node (ref "JP228") (pin "1") (pinfunction "1_1") (pintype "passive"))
    )
    (net (code "90") (name "/NEW_89") (class "Default")
      (node (ref "JP1125") (pin "P$2") (pinfunction "1_P$2") (pintype "passive"))
      (node (ref "JP277") (pin "1") (pinfunction "1_1") (pintype "passive"))
    )
    (net (code "91") (name "/NEW_90") (class "Default")
      (node (ref "JP1066") (pin "P$2") (pinfunction "1_P$2") (pintype "passive"))
      (node (ref "JP227") (pin "1") (pinfunction "1_1") (pintype "passive"))
    )
    (net (code "92") (name "/NEW_91") (class "Default")
      (node (ref "JP1126") (pin "P$2") (pinfunction "1_P$2") (pintype "passive"))
      (node (ref "JP287") (pin "1") (pinfunction "1_1") (pintype "passive"))
    )
    (net (code "93") (name "/NEW_92") (class "Default")
      (node (ref "JP1067") (pin "P$2") (pinfunction "1_P$2") (pintype "passive"))
      (node (ref "JP238") (pin "1") (pinfunction "1_1") (pintype "passive"))
    )
    (net (code "94") (name "/NEW_93") (class "Default")
      (node (ref "JP1127") (pin "P$2") (pinfunction "1_P$2") (pintype "passive"))
      (node (ref "JP290") (pin "1") (pinfunction "1_1") (pintype "passive"))
    )
    (net (code "95") (name "/NEW_94") (class "Default")
      (node (ref "JP1068") (pin "P$2") (pinfunction "1_P$2") (pintype "passive"))
      (node (ref "JP237") (pin "1") (pinfunction "1_1") (pintype "passive"))
    )
    (net (code "96") (name "/NEW_95") (class "Default")
      (node (ref "JP1128") (pin "P$2") (pinfunction "1_P$2") (pintype "passive"))
      (node (ref "JP297") (pin "1") (pinfunction "1_1") (pintype "passive"))
    )
    (net (code "97") (name "/NEW_96") (class "Default")
      (node (ref "JP1069") (pin "P$2") (pinfunction "1_P$2") (pintype "passive"))
      (node (ref "JP247") (pin "1") (pinfunction "1_1") (pintype "passive"))
    )
    (net (code "98") (name "/NEW_97") (class "Default")
      (node (ref "JP1129") (pin "P$2") (pinfunction "1_P$2") (pintype "passive"))
      (node (ref "JP300") (pin "1") (pinfunction "1_1") (pintype "passive"))
    )
    (net (code "99") (name "/NEW_98") (class "Default")
      (node (ref "JP1070") (pin "P$2") (pinfunction "1_P$2") (pintype "passive"))
      (node (ref "JP250") (pin "1") (pinfunction "1_1") (pintype "passive"))
    )
    (net (code "100") (name "/NEW_99") (class "Default")
      (node (ref "JP1130") (pin "P$2") (pinfunction "1_P$2") (pintype "passive"))
      (node (ref "JP249") (pin "1") (pinfunction "1_1") (pintype "passive"))
    )
    (net (code "101") (name "/NEW_100") (class "Default")
      (node (ref "JP1071") (pin "P$2") (pinfunction "1_P$2") (pintype "passive"))
      (node (ref "JP260") (pin "1") (pinfunction "1_1") (pintype "passive"))
    )
    (net (code "102") (name "/NEW_101") (class "Default")
      (node (ref "JP1131") (pin "P$2") (pinfunction "1_P$2") (pintype "passive"))
      (node (ref "JP240") (pin "1") (pinfunction "1_1") (pintype "passive"))
    )
    (net (code "103") (name "/NEW_102") (class "Default")
      (node (ref "JP1072") (pin "P$2") (pinfunction "1_P$2") (pintype "passive"))
      (node (ref "JP259") (pin "1") (pinfunction "1_1") (pintype "passive"))
    )
    (net (code "104") (name "/NEW_103") (class "Default")
      (node (ref "JP1132") (pin "P$2") (pinfunction "1_P$2") (pintype "passive"))
      (node (ref "JP239") (pin "1") (pinfunction "1_1") (pintype "passive"))
    )
    (net (code "105") (name "/NEW_104") (class "Default")
      (node (ref "JP1073") (pin "P$2") (pinfunction "1_P$2") (pintype "passive"))
      (node (ref "JP270") (pin "1") (pinfunction "1_1") (pintype "passive"))
    )
    (net (code "106") (name "/NEW_105") (class "Default")
      (node (ref "JP1133") (pin "P$2") (pinfunction "1_P$2") (pintype "passive"))
      (node (ref "JP230") (pin "1") (pinfunction "1_1") (pintype "passive"))
    )
    (net (code "107") (name "/NEW_106") (class "Default")
      (node (ref "JP1074") (pin "P$2") (pinfunction "1_P$2") (pintype "passive"))
      (node (ref "JP269") (pin "1") (pinfunction "1_1") (pintype "passive"))
    )
    (net (code "108") (name "/NEW_107") (class "Default")
      (node (ref "JP1134") (pin "P$2") (pinfunction "1_P$2") (pintype "passive"))
      (node (ref "JP229") (pin "1") (pinfunction "1_1") (pintype "passive"))
    )
    (net (code "109") (name "/NEW_108") (class "Default")
      (node (ref "JP1075") (pin "P$2") (pinfunction "1_P$2") (pintype "passive"))
      (node (ref "JP280") (pin "1") (pinfunction "1_1") (pintype "passive"))
    )
    (net (code "110") (name "/NEW_109") (class "Default")
      (node (ref "JP1135") (pin "P$2") (pinfunction "1_P$2") (pintype "passive"))
      (node (ref "JP220") (pin "1") (pinfunction "1_1") (pintype "passive"))
    )
    (net (code "111") (name "/NEW_110") (class "Default")
      (node (ref "JP1076") (pin "P$2") (pinfunction "1_P$2") (pintype "passive"))
      (node (ref "JP279") (pin "1") (pinfunction "1_1") (pintype "passive"))
    )
    (net (code "112") (name "/NEW_111") (class "Default")
      (node (ref "JP1136") (pin "P$2") (pinfunction "1_P$2") (pintype "passive"))
      (node (ref "JP219") (pin "1") (pinfunction "1_1") (pintype "passive"))
    )
    (net (code "113") (name "/NEW_112") (class "Default")
      (node (ref "JP1077") (pin "P$2") (pinfunction "1_P$2") (pintype "passive"))
      (node (ref "JP289") (pin "1") (pinfunction "1_1") (pintype "passive"))
    )
    (net (code "114") (name "/NEW_113") (class "Default")
      (node (ref "JP1137") (pin "P$2") (pinfunction "1_P$2") (pintype "passive"))
      (node (ref "JP210") (pin "1") (pinfunction "1_1") (pintype "passive"))
    )
    (net (code "115") (name "/NEW_114") (class "Default")
      (node (ref "JP1078") (pin "P$2") (pinfunction "1_P$2") (pintype "passive"))
      (node (ref "JP288") (pin "1") (pinfunction "1_1") (pintype "passive"))
    )
    (net (code "116") (name "/NEW_115") (class "Default")
      (node (ref "JP1138") (pin "P$2") (pinfunction "1_P$2") (pintype "passive"))
      (node (ref "JP209") (pin "1") (pinfunction "1_1") (pintype "passive"))
    )
    (net (code "117") (name "/NEW_116") (class "Default")
      (node (ref "JP1079") (pin "P$2") (pinfunction "1_P$2") (pintype "passive"))
      (node (ref "JP299") (pin "1") (pinfunction "1_1") (pintype "passive"))
    )
    (net (code "118") (name "/NEW_117") (class "Default")
      (node (ref "JP1139") (pin "P$2") (pinfunction "1_P$2") (pintype "passive"))
      (node (ref "JP200") (pin "1") (pinfunction "1_1") (pintype "passive"))
    )
    (net (code "119") (name "/NEW_118") (class "Default")
      (node (ref "JP1080") (pin "P$2") (pinfunction "1_P$2") (pintype "passive"))
      (node (ref "JP298") (pin "1") (pinfunction "1_1") (pintype "passive"))
    )
    (net (code "120") (name "/NEW_119") (class "Default")
      (node (ref "JP1140") (pin "P$2") (pinfunction "1_P$2") (pintype "passive"))
      (node (ref "JP199") (pin "1") (pinfunction "1_1") (pintype "passive"))
    )
    (net (code "121") (name "/NEW_120") (class "Default")
      (node (ref "JP1") (pin "1") (pinfunction "1_1") (pintype "passive"))
      (node (ref "JP961") (pin "P$2") (pinfunction "1_P$2") (pintype "passive"))
    )
    (net (code "122") (name "/NEW_121") (class "Default")
      (node (ref "JP2") (pin "1") (pinfunction "1_1") (pintype "passive"))
      (node (ref "JP901") (pin "P$2") (pinfunction "1_P$2") (pintype "passive"))
    )
    (net (code "123") (name "/NEW_122") (class "Default")
      (node (ref "JP3") (pin "1") (pinfunction "1_1") (pintype "passive"))
      (node (ref "JP962") (pin "P$2") (pinfunction "1_P$2") (pintype "passive"))
    )
    (net (code "124") (name "/NEW_123") (class "Default")
      (node (ref "JP4") (pin "1") (pinfunction "1_1") (pintype "passive"))
      (node (ref "JP902") (pin "P$2") (pinfunction "1_P$2") (pintype "passive"))
    )
    (net (code "125") (name "/NEW_124") (class "Default")
      (node (ref "JP11") (pin "1") (pinfunction "1_1") (pintype "passive"))
      (node (ref "JP963") (pin "P$2") (pinfunction "1_P$2") (pintype "passive"))
    )
    (net (code "126") (name "/NEW_125") (class "Default")
      (node (ref "JP13") (pin "1") (pinfunction "1_1") (pintype "passive"))
      (node (ref "JP903") (pin "P$2") (pinfunction "1_P$2") (pintype "passive"))
    )
    (net (code "127") (name "/NEW_126") (class "Default")
      (node (ref "JP14") (pin "1") (pinfunction "1_1") (pintype "passive"))
      (node (ref "JP964") (pin "P$2") (pinfunction "1_P$2") (pintype "passive"))
    )
    (net (code "128") (name "/NEW_127") (class "Default")
      (node (ref "JP12") (pin "1") (pinfunction "1_1") (pintype "passive"))
      (node (ref "JP904") (pin "P$2") (pinfunction "1_P$2") (pintype "passive"))
    )
    (net (code "129") (name "/NEW_128") (class "Default")
      (node (ref "JP21") (pin "1") (pinfunction "1_1") (pintype "passive"))
      (node (ref "JP965") (pin "P$2") (pinfunction "1_P$2") (pintype "passive"))
    )
    (net (code "130") (name "/NEW_129") (class "Default")
      (node (ref "JP22") (pin "1") (pinfunction "1_1") (pintype "passive"))
      (node (ref "JP905") (pin "P$2") (pinfunction "1_P$2") (pintype "passive"))
    )
    (net (code "131") (name "/NEW_130") (class "Default")
      (node (ref "JP24") (pin "1") (pinfunction "1_1") (pintype "passive"))
      (node (ref "JP966") (pin "P$2") (pinfunction "1_P$2") (pintype "passive"))
    )
    (net (code "132") (name "/NEW_131") (class "Default")
      (node (ref "JP23") (pin "1") (pinfunction "1_1") (pintype "passive"))
      (node (ref "JP906") (pin "P$2") (pinfunction "1_P$2") (pintype "passive"))
    )
    (net (code "133") (name "/NEW_132") (class "Default")
      (node (ref "JP31") (pin "1") (pinfunction "1_1") (pintype "passive"))
      (node (ref "JP967") (pin "P$2") (pinfunction "1_P$2") (pintype "passive"))
    )
    (net (code "134") (name "/NEW_133") (class "Default")
      (node (ref "JP32") (pin "1") (pinfunction "1_1") (pintype "passive"))
      (node (ref "JP907") (pin "P$2") (pinfunction "1_P$2") (pintype "passive"))
    )
    (net (code "135") (name "/NEW_134") (class "Default")
      (node (ref "JP33") (pin "1") (pinfunction "1_1") (pintype "passive"))
      (node (ref "JP968") (pin "P$2") (pinfunction "1_P$2") (pintype "passive"))
    )
    (net (code "136") (name "/NEW_135") (class "Default")
      (node (ref "JP34") (pin "1") (pinfunction "1_1") (pintype "passive"))
      (node (ref "JP908") (pin "P$2") (pinfunction "1_P$2") (pintype "passive"))
    )
    (net (code "137") (name "/NEW_136") (class "Default")
      (node (ref "JP41") (pin "1") (pinfunction "1_1") (pintype "passive"))
      (node (ref "JP969") (pin "P$2") (pinfunction "1_P$2") (pintype "passive"))
    )
    (net (code "138") (name "/NEW_137") (class "Default")
      (node (ref "JP42") (pin "1") (pinfunction "1_1") (pintype "passive"))
      (node (ref "JP909") (pin "P$2") (pinfunction "1_P$2") (pintype "passive"))
    )
    (net (code "139") (name "/NEW_138") (class "Default")
      (node (ref "JP43") (pin "1") (pinfunction "1_1") (pintype "passive"))
      (node (ref "JP970") (pin "P$2") (pinfunction "1_P$2") (pintype "passive"))
    )
    (net (code "140") (name "/NEW_139") (class "Default")
      (node (ref "JP44") (pin "1") (pinfunction "1_1") (pintype "passive"))
      (node (ref "JP910") (pin "P$2") (pinfunction "1_P$2") (pintype "passive"))
    )
    (net (code "141") (name "/NEW_140") (class "Default")
      (node (ref "JP51") (pin "1") (pinfunction "1_1") (pintype "passive"))
      (node (ref "JP971") (pin "P$2") (pinfunction "1_P$2") (pintype "passive"))
    )
    (net (code "142") (name "/NEW_141") (class "Default")
      (node (ref "JP52") (pin "1") (pinfunction "1_1") (pintype "passive"))
      (node (ref "JP911") (pin "P$2") (pinfunction "1_P$2") (pintype "passive"))
    )
    (net (code "143") (name "/NEW_142") (class "Default")
      (node (ref "JP54") (pin "1") (pinfunction "1_1") (pintype "passive"))
      (node (ref "JP972") (pin "P$2") (pinfunction "1_P$2") (pintype "passive"))
    )
    (net (code "144") (name "/NEW_143") (class "Default")
      (node (ref "JP53") (pin "1") (pinfunction "1_1") (pintype "passive"))
      (node (ref "JP912") (pin "P$2") (pinfunction "1_P$2") (pintype "passive"))
    )
    (net (code "145") (name "/NEW_144") (class "Default")
      (node (ref "JP63") (pin "1") (pinfunction "1_1") (pintype "passive"))
      (node (ref "JP973") (pin "P$2") (pinfunction "1_P$2") (pintype "passive"))
    )
    (net (code "146") (name "/NEW_145") (class "Default")
      (node (ref "JP64") (pin "1") (pinfunction "1_1") (pintype "passive"))
      (node (ref "JP913") (pin "P$2") (pinfunction "1_P$2") (pintype "passive"))
    )
    (net (code "147") (name "/NEW_146") (class "Default")
      (node (ref "JP61") (pin "1") (pinfunction "1_1") (pintype "passive"))
      (node (ref "JP974") (pin "P$2") (pinfunction "1_P$2") (pintype "passive"))
    )
    (net (code "148") (name "/NEW_147") (class "Default")
      (node (ref "JP62") (pin "1") (pinfunction "1_1") (pintype "passive"))
      (node (ref "JP914") (pin "P$2") (pinfunction "1_P$2") (pintype "passive"))
    )
    (net (code "149") (name "/NEW_148") (class "Default")
      (node (ref "JP73") (pin "1") (pinfunction "1_1") (pintype "passive"))
      (node (ref "JP975") (pin "P$2") (pinfunction "1_P$2") (pintype "passive"))
    )
    (net (code "150") (name "/NEW_149") (class "Default")
      (node (ref "JP74") (pin "1") (pinfunction "1_1") (pintype "passive"))
      (node (ref "JP915") (pin "P$2") (pinfunction "1_P$2") (pintype "passive"))
    )
    (net (code "151") (name "/NEW_150") (class "Default")
      (node (ref "JP71") (pin "1") (pinfunction "1_1") (pintype "passive"))
      (node (ref "JP976") (pin "P$2") (pinfunction "1_P$2") (pintype "passive"))
    )
    (net (code "152") (name "/NEW_151") (class "Default")
      (node (ref "JP72") (pin "1") (pinfunction "1_1") (pintype "passive"))
      (node (ref "JP916") (pin "P$2") (pinfunction "1_P$2") (pintype "passive"))
    )
    (net (code "153") (name "/NEW_152") (class "Default")
      (node (ref "JP83") (pin "1") (pinfunction "1_1") (pintype "passive"))
      (node (ref "JP977") (pin "P$2") (pinfunction "1_P$2") (pintype "passive"))
    )
    (net (code "154") (name "/NEW_153") (class "Default")
      (node (ref "JP84") (pin "1") (pinfunction "1_1") (pintype "passive"))
      (node (ref "JP917") (pin "P$2") (pinfunction "1_P$2") (pintype "passive"))
    )
    (net (code "155") (name "/NEW_154") (class "Default")
      (node (ref "JP81") (pin "1") (pinfunction "1_1") (pintype "passive"))
      (node (ref "JP978") (pin "P$2") (pinfunction "1_P$2") (pintype "passive"))
    )
    (net (code "156") (name "/NEW_155") (class "Default")
      (node (ref "JP82") (pin "1") (pinfunction "1_1") (pintype "passive"))
      (node (ref "JP918") (pin "P$2") (pinfunction "1_P$2") (pintype "passive"))
    )
    (net (code "157") (name "/NEW_156") (class "Default")
      (node (ref "JP93") (pin "1") (pinfunction "1_1") (pintype "passive"))
      (node (ref "JP979") (pin "P$2") (pinfunction "1_P$2") (pintype "passive"))
    )
    (net (code "158") (name "/NEW_157") (class "Default")
      (node (ref "JP919") (pin "P$2") (pinfunction "1_P$2") (pintype "passive"))
      (node (ref "JP94") (pin "1") (pinfunction "1_1") (pintype "passive"))
    )
    (net (code "159") (name "/NEW_158") (class "Default")
      (node (ref "JP91") (pin "1") (pinfunction "1_1") (pintype "passive"))
      (node (ref "JP980") (pin "P$2") (pinfunction "1_P$2") (pintype "passive"))
    )
    (net (code "160") (name "/NEW_159") (class "Default")
      (node (ref "JP92") (pin "1") (pinfunction "1_1") (pintype "passive"))
      (node (ref "JP920") (pin "P$2") (pinfunction "1_P$2") (pintype "passive"))
    )
    (net (code "161") (name "/NEW_160") (class "Default")
      (node (ref "JP103") (pin "1") (pinfunction "1_1") (pintype "passive"))
      (node (ref "JP981") (pin "P$2") (pinfunction "1_P$2") (pintype "passive"))
    )
    (net (code "162") (name "/NEW_161") (class "Default")
      (node (ref "JP104") (pin "1") (pinfunction "1_1") (pintype "passive"))
      (node (ref "JP921") (pin "P$2") (pinfunction "1_P$2") (pintype "passive"))
    )
    (net (code "163") (name "/NEW_162") (class "Default")
      (node (ref "JP101") (pin "1") (pinfunction "1_1") (pintype "passive"))
      (node (ref "JP982") (pin "P$2") (pinfunction "1_P$2") (pintype "passive"))
    )
    (net (code "164") (name "/NEW_163") (class "Default")
      (node (ref "JP102") (pin "1") (pinfunction "1_1") (pintype "passive"))
      (node (ref "JP922") (pin "P$2") (pinfunction "1_P$2") (pintype "passive"))
    )
    (net (code "165") (name "/NEW_164") (class "Default")
      (node (ref "JP113") (pin "1") (pinfunction "1_1") (pintype "passive"))
      (node (ref "JP983") (pin "P$2") (pinfunction "1_P$2") (pintype "passive"))
    )
    (net (code "166") (name "/NEW_165") (class "Default")
      (node (ref "JP114") (pin "1") (pinfunction "1_1") (pintype "passive"))
      (node (ref "JP923") (pin "P$2") (pinfunction "1_P$2") (pintype "passive"))
    )
    (net (code "167") (name "/NEW_166") (class "Default")
      (node (ref "JP111") (pin "1") (pinfunction "1_1") (pintype "passive"))
      (node (ref "JP984") (pin "P$2") (pinfunction "1_P$2") (pintype "passive"))
    )
    (net (code "168") (name "/NEW_167") (class "Default")
      (node (ref "JP112") (pin "1") (pinfunction "1_1") (pintype "passive"))
      (node (ref "JP924") (pin "P$2") (pinfunction "1_P$2") (pintype "passive"))
    )
    (net (code "169") (name "/NEW_168") (class "Default")
      (node (ref "JP123") (pin "1") (pinfunction "1_1") (pintype "passive"))
      (node (ref "JP985") (pin "P$2") (pinfunction "1_P$2") (pintype "passive"))
    )
    (net (code "170") (name "/NEW_169") (class "Default")
      (node (ref "JP124") (pin "1") (pinfunction "1_1") (pintype "passive"))
      (node (ref "JP925") (pin "P$2") (pinfunction "1_P$2") (pintype "passive"))
    )
    (net (code "171") (name "/NEW_170") (class "Default")
      (node (ref "JP121") (pin "1") (pinfunction "1_1") (pintype "passive"))
      (node (ref "JP986") (pin "P$2") (pinfunction "1_P$2") (pintype "passive"))
    )
    (net (code "172") (name "/NEW_171") (class "Default")
      (node (ref "JP122") (pin "1") (pinfunction "1_1") (pintype "passive"))
      (node (ref "JP926") (pin "P$2") (pinfunction "1_P$2") (pintype "passive"))
    )
    (net (code "173") (name "/NEW_172") (class "Default")
      (node (ref "JP133") (pin "1") (pinfunction "1_1") (pintype "passive"))
      (node (ref "JP987") (pin "P$2") (pinfunction "1_P$2") (pintype "passive"))
    )
    (net (code "174") (name "/NEW_173") (class "Default")
      (node (ref "JP134") (pin "1") (pinfunction "1_1") (pintype "passive"))
      (node (ref "JP927") (pin "P$2") (pinfunction "1_P$2") (pintype "passive"))
    )
    (net (code "175") (name "/NEW_174") (class "Default")
      (node (ref "JP131") (pin "1") (pinfunction "1_1") (pintype "passive"))
      (node (ref "JP988") (pin "P$2") (pinfunction "1_P$2") (pintype "passive"))
    )
    (net (code "176") (name "/NEW_175") (class "Default")
      (node (ref "JP132") (pin "1") (pinfunction "1_1") (pintype "passive"))
      (node (ref "JP928") (pin "P$2") (pinfunction "1_P$2") (pintype "passive"))
    )
    (net (code "177") (name "/NEW_176") (class "Default")
      (node (ref "JP143") (pin "1") (pinfunction "1_1") (pintype "passive"))
      (node (ref "JP989") (pin "P$2") (pinfunction "1_P$2") (pintype "passive"))
    )
    (net (code "178") (name "/NEW_177") (class "Default")
      (node (ref "JP144") (pin "1") (pinfunction "1_1") (pintype "passive"))
      (node (ref "JP929") (pin "P$2") (pinfunction "1_P$2") (pintype "passive"))
    )
    (net (code "179") (name "/NEW_178") (class "Default")
      (node (ref "JP141") (pin "1") (pinfunction "1_1") (pintype "passive"))
      (node (ref "JP990") (pin "P$2") (pinfunction "1_P$2") (pintype "passive"))
    )
    (net (code "180") (name "/NEW_179") (class "Default")
      (node (ref "JP142") (pin "1") (pinfunction "1_1") (pintype "passive"))
      (node (ref "JP930") (pin "P$2") (pinfunction "1_P$2") (pintype "passive"))
    )
    (net (code "181") (name "/NEW_180") (class "Default")
      (node (ref "JP153") (pin "1") (pinfunction "1_1") (pintype "passive"))
      (node (ref "JP991") (pin "P$2") (pinfunction "1_P$2") (pintype "passive"))
    )
    (net (code "182") (name "/NEW_181") (class "Default")
      (node (ref "JP154") (pin "1") (pinfunction "1_1") (pintype "passive"))
      (node (ref "JP931") (pin "P$2") (pinfunction "1_P$2") (pintype "passive"))
    )
    (net (code "183") (name "/NEW_182") (class "Default")
      (node (ref "JP151") (pin "1") (pinfunction "1_1") (pintype "passive"))
      (node (ref "JP992") (pin "P$2") (pinfunction "1_P$2") (pintype "passive"))
    )
    (net (code "184") (name "/NEW_183") (class "Default")
      (node (ref "JP152") (pin "1") (pinfunction "1_1") (pintype "passive"))
      (node (ref "JP932") (pin "P$2") (pinfunction "1_P$2") (pintype "passive"))
    )
    (net (code "185") (name "/NEW_184") (class "Default")
      (node (ref "JP163") (pin "1") (pinfunction "1_1") (pintype "passive"))
      (node (ref "JP993") (pin "P$2") (pinfunction "1_P$2") (pintype "passive"))
    )
    (net (code "186") (name "/NEW_185") (class "Default")
      (node (ref "JP164") (pin "1") (pinfunction "1_1") (pintype "passive"))
      (node (ref "JP933") (pin "P$2") (pinfunction "1_P$2") (pintype "passive"))
    )
    (net (code "187") (name "/NEW_186") (class "Default")
      (node (ref "JP161") (pin "1") (pinfunction "1_1") (pintype "passive"))
      (node (ref "JP994") (pin "P$2") (pinfunction "1_P$2") (pintype "passive"))
    )
    (net (code "188") (name "/NEW_187") (class "Default")
      (node (ref "JP162") (pin "1") (pinfunction "1_1") (pintype "passive"))
      (node (ref "JP934") (pin "P$2") (pinfunction "1_P$2") (pintype "passive"))
    )
    (net (code "189") (name "/NEW_188") (class "Default")
      (node (ref "JP173") (pin "1") (pinfunction "1_1") (pintype "passive"))
      (node (ref "JP995") (pin "P$2") (pinfunction "1_P$2") (pintype "passive"))
    )
    (net (code "190") (name "/NEW_189") (class "Default")
      (node (ref "JP174") (pin "1") (pinfunction "1_1") (pintype "passive"))
      (node (ref "JP935") (pin "P$2") (pinfunction "1_P$2") (pintype "passive"))
    )
    (net (code "191") (name "/NEW_190") (class "Default")
      (node (ref "JP171") (pin "1") (pinfunction "1_1") (pintype "passive"))
      (node (ref "JP996") (pin "P$2") (pinfunction "1_P$2") (pintype "passive"))
    )
    (net (code "192") (name "/NEW_191") (class "Default")
      (node (ref "JP172") (pin "1") (pinfunction "1_1") (pintype "passive"))
      (node (ref "JP936") (pin "P$2") (pinfunction "1_P$2") (pintype "passive"))
    )
    (net (code "193") (name "/NEW_192") (class "Default")
      (node (ref "JP183") (pin "1") (pinfunction "1_1") (pintype "passive"))
      (node (ref "JP997") (pin "P$2") (pinfunction "1_P$2") (pintype "passive"))
    )
    (net (code "194") (name "/NEW_193") (class "Default")
      (node (ref "JP243") (pin "1") (pinfunction "1_1") (pintype "passive"))
      (node (ref "JP937") (pin "P$2") (pinfunction "1_P$2") (pintype "passive"))
    )
    (net (code "195") (name "/NEW_194") (class "Default")
      (node (ref "JP184") (pin "1") (pinfunction "1_1") (pintype "passive"))
      (node (ref "JP998") (pin "P$2") (pinfunction "1_P$2") (pintype "passive"))
    )
    (net (code "196") (name "/NEW_195") (class "Default")
      (node (ref "JP244") (pin "1") (pinfunction "1_1") (pintype "passive"))
      (node (ref "JP938") (pin "P$2") (pinfunction "1_P$2") (pintype "passive"))
    )
    (net (code "197") (name "/NEW_196") (class "Default")
      (node (ref "JP193") (pin "1") (pinfunction "1_1") (pintype "passive"))
      (node (ref "JP999") (pin "P$2") (pinfunction "1_P$2") (pintype "passive"))
    )
    (net (code "198") (name "/NEW_197") (class "Default")
      (node (ref "JP253") (pin "1") (pinfunction "1_1") (pintype "passive"))
      (node (ref "JP939") (pin "P$2") (pinfunction "1_P$2") (pintype "passive"))
    )
    (net (code "199") (name "/NEW_198") (class "Default")
      (node (ref "JP1000") (pin "P$2") (pinfunction "1_P$2") (pintype "passive"))
      (node (ref "JP194") (pin "1") (pinfunction "1_1") (pintype "passive"))
    )
    (net (code "200") (name "/NEW_199") (class "Default")
      (node (ref "JP254") (pin "1") (pinfunction "1_1") (pintype "passive"))
      (node (ref "JP940") (pin "P$2") (pinfunction "1_P$2") (pintype "passive"))
    )
    (net (code "201") (name "/NEW_200") (class "Default")
      (node (ref "JP1001") (pin "P$2") (pinfunction "1_P$2") (pintype "passive"))
      (node (ref "JP203") (pin "1") (pinfunction "1_1") (pintype "passive"))
    )
    (net (code "202") (name "/NEW_201") (class "Default")
      (node (ref "JP264") (pin "1") (pinfunction "1_1") (pintype "passive"))
      (node (ref "JP941") (pin "P$2") (pinfunction "1_P$2") (pintype "passive"))
    )
    (net (code "203") (name "/NEW_202") (class "Default")
      (node (ref "JP1002") (pin "P$2") (pinfunction "1_P$2") (pintype "passive"))
      (node (ref "JP204") (pin "1") (pinfunction "1_1") (pintype "passive"))
    )
    (net (code "204") (name "/NEW_203") (class "Default")
      (node (ref "JP263") (pin "1") (pinfunction "1_1") (pintype "passive"))
      (node (ref "JP942") (pin "P$2") (pinfunction "1_P$2") (pintype "passive"))
    )
    (net (code "205") (name "/NEW_204") (class "Default")
      (node (ref "JP1003") (pin "P$2") (pinfunction "1_P$2") (pintype "passive"))
      (node (ref "JP213") (pin "1") (pinfunction "1_1") (pintype "passive"))
    )
    (net (code "206") (name "/NEW_205") (class "Default")
      (node (ref "JP273") (pin "1") (pinfunction "1_1") (pintype "passive"))
      (node (ref "JP943") (pin "P$2") (pinfunction "1_P$2") (pintype "passive"))
    )
    (net (code "207") (name "/NEW_206") (class "Default")
      (node (ref "JP1004") (pin "P$2") (pinfunction "1_P$2") (pintype "passive"))
      (node (ref "JP214") (pin "1") (pinfunction "1_1") (pintype "passive"))
    )
    (net (code "208") (name "/NEW_207") (class "Default")
      (node (ref "JP274") (pin "1") (pinfunction "1_1") (pintype "passive"))
      (node (ref "JP944") (pin "P$2") (pinfunction "1_P$2") (pintype "passive"))
    )
    (net (code "209") (name "/NEW_208") (class "Default")
      (node (ref "JP1005") (pin "P$2") (pinfunction "1_P$2") (pintype "passive"))
      (node (ref "JP223") (pin "1") (pinfunction "1_1") (pintype "passive"))
    )
    (net (code "210") (name "/NEW_209") (class "Default")
      (node (ref "JP284") (pin "1") (pinfunction "1_1") (pintype "passive"))
      (node (ref "JP945") (pin "P$2") (pinfunction "1_P$2") (pintype "passive"))
    )
    (net (code "211") (name "/NEW_210") (class "Default")
      (node (ref "JP1006") (pin "P$2") (pinfunction "1_P$2") (pintype "passive"))
      (node (ref "JP224") (pin "1") (pinfunction "1_1") (pintype "passive"))
    )
    (net (code "212") (name "/NEW_211") (class "Default")
      (node (ref "JP281") (pin "1") (pinfunction "1_1") (pintype "passive"))
      (node (ref "JP946") (pin "P$2") (pinfunction "1_P$2") (pintype "passive"))
    )
    (net (code "213") (name "/NEW_212") (class "Default")
      (node (ref "JP1007") (pin "P$2") (pinfunction "1_P$2") (pintype "passive"))
      (node (ref "JP233") (pin "1") (pinfunction "1_1") (pintype "passive"))
    )
    (net (code "214") (name "/NEW_213") (class "Default")
      (node (ref "JP294") (pin "1") (pinfunction "1_1") (pintype "passive"))
      (node (ref "JP947") (pin "P$2") (pinfunction "1_P$2") (pintype "passive"))
    )
    (net (code "215") (name "/NEW_214") (class "Default")
      (node (ref "JP1008") (pin "P$2") (pinfunction "1_P$2") (pintype "passive"))
      (node (ref "JP234") (pin "1") (pinfunction "1_1") (pintype "passive"))
    )
    (net (code "216") (name "/NEW_215") (class "Default")
      (node (ref "JP291") (pin "1") (pinfunction "1_1") (pintype "passive"))
      (node (ref "JP948") (pin "P$2") (pinfunction "1_P$2") (pintype "passive"))
    )
    (net (code "217") (name "/NEW_216") (class "Default")
      (node (ref "JP1009") (pin "P$2") (pinfunction "1_P$2") (pintype "passive"))
      (node (ref "JP241") (pin "1") (pinfunction "1_1") (pintype "passive"))
    )
    (net (code "218") (name "/NEW_217") (class "Default")
      (node (ref "JP231") (pin "1") (pinfunction "1_1") (pintype "passive"))
      (node (ref "JP949") (pin "P$2") (pinfunction "1_P$2") (pintype "passive"))
    )
    (net (code "219") (name "/NEW_218") (class "Default")
      (node (ref "JP1010") (pin "P$2") (pinfunction "1_P$2") (pintype "passive"))
      (node (ref "JP242") (pin "1") (pinfunction "1_1") (pintype "passive"))
    )
    (net (code "220") (name "/NEW_219") (class "Default")
      (node (ref "JP232") (pin "1") (pinfunction "1_1") (pintype "passive"))
      (node (ref "JP950") (pin "P$2") (pinfunction "1_P$2") (pintype "passive"))
    )
    (net (code "221") (name "/NEW_220") (class "Default")
      (node (ref "JP1011") (pin "P$2") (pinfunction "1_P$2") (pintype "passive"))
      (node (ref "JP251") (pin "1") (pinfunction "1_1") (pintype "passive"))
    )
    (net (code "222") (name "/NEW_221") (class "Default")
      (node (ref "JP221") (pin "1") (pinfunction "1_1") (pintype "passive"))
      (node (ref "JP951") (pin "P$2") (pinfunction "1_P$2") (pintype "passive"))
    )
    (net (code "223") (name "/NEW_222") (class "Default")
      (node (ref "JP1012") (pin "P$2") (pinfunction "1_P$2") (pintype "passive"))
      (node (ref "JP252") (pin "1") (pinfunction "1_1") (pintype "passive"))
    )
    (net (code "224") (name "/NEW_223") (class "Default")
      (node (ref "JP222") (pin "1") (pinfunction "1_1") (pintype "passive"))
      (node (ref "JP952") (pin "P$2") (pinfunction "1_P$2") (pintype "passive"))
    )
    (net (code "225") (name "/NEW_224") (class "Default")
      (node (ref "JP1013") (pin "P$2") (pinfunction "1_P$2") (pintype "passive"))
      (node (ref "JP261") (pin "1") (pinfunction "1_1") (pintype "passive"))
    )
    (net (code "226") (name "/NEW_225") (class "Default")
      (node (ref "JP211") (pin "1") (pinfunction "1_1") (pintype "passive"))
      (node (ref "JP953") (pin "P$2") (pinfunction "1_P$2") (pintype "passive"))
    )
    (net (code "227") (name "/NEW_226") (class "Default")
      (node (ref "JP1014") (pin "P$2") (pinfunction "1_P$2") (pintype "passive"))
      (node (ref "JP262") (pin "1") (pinfunction "1_1") (pintype "passive"))
    )
    (net (code "228") (name "/NEW_227") (class "Default")
      (node (ref "JP212") (pin "1") (pinfunction "1_1") (pintype "passive"))
      (node (ref "JP954") (pin "P$2") (pinfunction "1_P$2") (pintype "passive"))
    )
    (net (code "229") (name "/NEW_228") (class "Default")
      (node (ref "JP1015") (pin "P$2") (pinfunction "1_P$2") (pintype "passive"))
      (node (ref "JP271") (pin "1") (pinfunction "1_1") (pintype "passive"))
    )
    (net (code "230") (name "/NEW_229") (class "Default")
      (node (ref "JP201") (pin "1") (pinfunction "1_1") (pintype "passive"))
      (node (ref "JP955") (pin "P$2") (pinfunction "1_P$2") (pintype "passive"))
    )
    (net (code "231") (name "/NEW_230") (class "Default")
      (node (ref "JP1016") (pin "P$2") (pinfunction "1_P$2") (pintype "passive"))
      (node (ref "JP272") (pin "1") (pinfunction "1_1") (pintype "passive"))
    )
    (net (code "232") (name "/NEW_231") (class "Default")
      (node (ref "JP202") (pin "1") (pinfunction "1_1") (pintype "passive"))
      (node (ref "JP956") (pin "P$2") (pinfunction "1_P$2") (pintype "passive"))
    )
    (net (code "233") (name "/NEW_232") (class "Default")
      (node (ref "JP1017") (pin "P$2") (pinfunction "1_P$2") (pintype "passive"))
      (node (ref "JP282") (pin "1") (pinfunction "1_1") (pintype "passive"))
    )
    (net (code "234") (name "/NEW_233") (class "Default")
      (node (ref "JP191") (pin "1") (pinfunction "1_1") (pintype "passive"))
      (node (ref "JP957") (pin "P$2") (pinfunction "1_P$2") (pintype "passive"))
    )
    (net (code "235") (name "/NEW_234") (class "Default")
      (node (ref "JP1018") (pin "P$2") (pinfunction "1_P$2") (pintype "passive"))
      (node (ref "JP283") (pin "1") (pinfunction "1_1") (pintype "passive"))
    )
    (net (code "236") (name "/NEW_235") (class "Default")
      (node (ref "JP192") (pin "1") (pinfunction "1_1") (pintype "passive"))
      (node (ref "JP958") (pin "P$2") (pinfunction "1_P$2") (pintype "passive"))
    )
    (net (code "237") (name "/NEW_236") (class "Default")
      (node (ref "JP1019") (pin "P$2") (pinfunction "1_P$2") (pintype "passive"))
      (node (ref "JP292") (pin "1") (pinfunction "1_1") (pintype "passive"))
    )
    (net (code "238") (name "/NEW_237") (class "Default")
      (node (ref "JP181") (pin "1") (pinfunction "1_1") (pintype "passive"))
      (node (ref "JP959") (pin "P$2") (pinfunction "1_P$2") (pintype "passive"))
    )
    (net (code "239") (name "/NEW_238") (class "Default")
      (node (ref "JP1020") (pin "P$2") (pinfunction "1_P$2") (pintype "passive"))
      (node (ref "JP293") (pin "1") (pinfunction "1_1") (pintype "passive"))
    )
    (net (code "240") (name "/NEW_239") (class "Default")
      (node (ref "JP182") (pin "1") (pinfunction "1_1") (pintype "passive"))
      (node (ref "JP960") (pin "P$2") (pinfunction "1_P$2") (pintype "passive"))
    )
    (net (code "241") (name "/NEW_240") (class "Default")
      (node (ref "JP105") (pin "1") (pinfunction "1_1") (pintype "passive"))
      (node (ref "JP1141") (pin "P$2") (pinfunction "1_P$2") (pintype "passive"))
    )
    (net (code "242") (name "/NEW_241") (class "Default")
      (node (ref "JP1142") (pin "P$2") (pinfunction "1_P$2") (pintype "passive"))
      (node (ref "JP115") (pin "1") (pinfunction "1_1") (pintype "passive"))
    )
    (net (code "243") (name "/NEW_242") (class "Default")
      (node (ref "JP1143") (pin "P$2") (pinfunction "1_P$2") (pintype "passive"))
      (node (ref "JP125") (pin "1") (pinfunction "1_1") (pintype "passive"))
    )
    (net (code "244") (name "/NEW_243") (class "Default")
      (node (ref "JP1144") (pin "P$2") (pinfunction "1_P$2") (pintype "passive"))
      (node (ref "JP135") (pin "1") (pinfunction "1_1") (pintype "passive"))
    )
    (net (code "245") (name "/NEW_244") (class "Default")
      (node (ref "JP1145") (pin "P$2") (pinfunction "1_P$2") (pintype "passive"))
      (node (ref "JP145") (pin "1") (pinfunction "1_1") (pintype "passive"))
    )
    (net (code "246") (name "/NEW_245") (class "Default")
      (node (ref "JP1146") (pin "P$2") (pinfunction "1_P$2") (pintype "passive"))
      (node (ref "JP155") (pin "1") (pinfunction "1_1") (pintype "passive"))
    )
    (net (code "247") (name "/NEW_246") (class "Default")
      (node (ref "JP1147") (pin "P$2") (pinfunction "1_P$2") (pintype "passive"))
      (node (ref "JP165") (pin "1") (pinfunction "1_1") (pintype "passive"))
    )
    (net (code "248") (name "/NEW_247") (class "Default")
      (node (ref "JP1148") (pin "P$2") (pinfunction "1_P$2") (pintype "passive"))
      (node (ref "JP175") (pin "1") (pinfunction "1_1") (pintype "passive"))
    )
    (net (code "249") (name "/NEW_248") (class "Default")
      (node (ref "JP1149") (pin "P$2") (pinfunction "1_P$2") (pintype "passive"))
      (node (ref "JP185") (pin "1") (pinfunction "1_1") (pintype "passive"))
    )
    (net (code "250") (name "/NEW_249") (class "Default")
      (node (ref "JP1150") (pin "P$2") (pinfunction "1_P$2") (pintype "passive"))
      (node (ref "JP195") (pin "1") (pinfunction "1_1") (pintype "passive"))
    )
    (net (code "251") (name "/NEW_250") (class "Default")
      (node (ref "JP1151") (pin "P$2") (pinfunction "1_P$2") (pintype "passive"))
      (node (ref "JP5") (pin "1") (pinfunction "1_1") (pintype "passive"))
    )
    (net (code "252") (name "/NEW_251") (class "Default")
      (node (ref "JP1152") (pin "P$2") (pinfunction "1_P$2") (pintype "passive"))
      (node (ref "JP15") (pin "1") (pinfunction "1_1") (pintype "passive"))
    )
    (net (code "253") (name "/NEW_252") (class "Default")
      (node (ref "JP1153") (pin "P$2") (pinfunction "1_P$2") (pintype "passive"))
      (node (ref "JP25") (pin "1") (pinfunction "1_1") (pintype "passive"))
    )
    (net (code "254") (name "/NEW_253") (class "Default")
      (node (ref "JP1154") (pin "P$2") (pinfunction "1_P$2") (pintype "passive"))
      (node (ref "JP35") (pin "1") (pinfunction "1_1") (pintype "passive"))
    )
    (net (code "255") (name "/NEW_254") (class "Default")
      (node (ref "JP1155") (pin "P$2") (pinfunction "1_P$2") (pintype "passive"))
      (node (ref "JP45") (pin "1") (pinfunction "1_1") (pintype "passive"))
    )
    (net (code "256") (name "/NEW_255") (class "Default")
      (node (ref "JP1156") (pin "P$2") (pinfunction "1_P$2") (pintype "passive"))
      (node (ref "JP55") (pin "1") (pinfunction "1_1") (pintype "passive"))
    )
    (net (code "257") (name "/NEW_256") (class "Default")
      (node (ref "JP1157") (pin "P$2") (pinfunction "1_P$2") (pintype "passive"))
      (node (ref "JP65") (pin "1") (pinfunction "1_1") (pintype "passive"))
    )
    (net (code "258") (name "/NEW_257") (class "Default")
      (node (ref "JP1158") (pin "P$2") (pinfunction "1_P$2") (pintype "passive"))
      (node (ref "JP75") (pin "1") (pinfunction "1_1") (pintype "passive"))
    )
    (net (code "259") (name "/NEW_258") (class "Default")
      (node (ref "JP1159") (pin "P$2") (pinfunction "1_P$2") (pintype "passive"))
      (node (ref "JP85") (pin "1") (pinfunction "1_1") (pintype "passive"))
    )
    (net (code "260") (name "/NEW_259") (class "Default")
      (node (ref "JP1160") (pin "P$2") (pinfunction "1_P$2") (pintype "passive"))
      (node (ref "JP95") (pin "1") (pinfunction "1_1") (pintype "passive"))
    )
    (net (code "261") (name "/NEW_260") (class "Default")
      (node (ref "JP1181") (pin "P$2") (pinfunction "1_P$2") (pintype "passive"))
      (node (ref "JP295") (pin "1") (pinfunction "1_1") (pintype "passive"))
    )
    (net (code "262") (name "/NEW_261") (class "Default")
      (node (ref "JP1182") (pin "P$2") (pinfunction "1_P$2") (pintype "passive"))
      (node (ref "JP285") (pin "1") (pinfunction "1_1") (pintype "passive"))
    )
    (net (code "263") (name "/NEW_262") (class "Default")
      (node (ref "JP1183") (pin "P$2") (pinfunction "1_P$2") (pintype "passive"))
      (node (ref "JP275") (pin "1") (pinfunction "1_1") (pintype "passive"))
    )
    (net (code "264") (name "/NEW_263") (class "Default")
      (node (ref "JP1184") (pin "P$2") (pinfunction "1_P$2") (pintype "passive"))
      (node (ref "JP265") (pin "1") (pinfunction "1_1") (pintype "passive"))
    )
    (net (code "265") (name "/NEW_264") (class "Default")
      (node (ref "JP1185") (pin "P$2") (pinfunction "1_P$2") (pintype "passive"))
      (node (ref "JP255") (pin "1") (pinfunction "1_1") (pintype "passive"))
    )
    (net (code "266") (name "/NEW_265") (class "Default")
      (node (ref "JP1186") (pin "P$2") (pinfunction "1_P$2") (pintype "passive"))
      (node (ref "JP245") (pin "1") (pinfunction "1_1") (pintype "passive"))
    )
    (net (code "267") (name "/NEW_266") (class "Default")
      (node (ref "JP1187") (pin "P$2") (pinfunction "1_P$2") (pintype "passive"))
      (node (ref "JP235") (pin "1") (pinfunction "1_1") (pintype "passive"))
    )
    (net (code "268") (name "/NEW_267") (class "Default")
      (node (ref "JP1188") (pin "P$2") (pinfunction "1_P$2") (pintype "passive"))
      (node (ref "JP225") (pin "1") (pinfunction "1_1") (pintype "passive"))
    )
    (net (code "269") (name "/NEW_268") (class "Default")
      (node (ref "JP1189") (pin "P$2") (pinfunction "1_P$2") (pintype "passive"))
      (node (ref "JP215") (pin "1") (pinfunction "1_1") (pintype "passive"))
    )
    (net (code "270") (name "/NEW_269") (class "Default")
      (node (ref "JP1190") (pin "P$2") (pinfunction "1_P$2") (pintype "passive"))
      (node (ref "JP205") (pin "1") (pinfunction "1_1") (pintype "passive"))
    )
    (net (code "271") (name "/NEW_270") (class "Default")
      (node (ref "JP1161") (pin "P$2") (pinfunction "1_P$2") (pintype "passive"))
      (node (ref "JP196") (pin "1") (pinfunction "1_1") (pintype "passive"))
    )
    (net (code "272") (name "/NEW_271") (class "Default")
      (node (ref "JP1162") (pin "P$2") (pinfunction "1_P$2") (pintype "passive"))
      (node (ref "JP186") (pin "1") (pinfunction "1_1") (pintype "passive"))
    )
    (net (code "273") (name "/NEW_272") (class "Default")
      (node (ref "JP1163") (pin "P$2") (pinfunction "1_P$2") (pintype "passive"))
      (node (ref "JP176") (pin "1") (pinfunction "1_1") (pintype "passive"))
    )
    (net (code "274") (name "/NEW_273") (class "Default")
      (node (ref "JP1164") (pin "P$2") (pinfunction "1_P$2") (pintype "passive"))
      (node (ref "JP166") (pin "1") (pinfunction "1_1") (pintype "passive"))
    )
    (net (code "275") (name "/NEW_274") (class "Default")
      (node (ref "JP1165") (pin "P$2") (pinfunction "1_P$2") (pintype "passive"))
      (node (ref "JP156") (pin "1") (pinfunction "1_1") (pintype "passive"))
    )
    (net (code "276") (name "/NEW_275") (class "Default")
      (node (ref "JP1166") (pin "P$2") (pinfunction "1_P$2") (pintype "passive"))
      (node (ref "JP146") (pin "1") (pinfunction "1_1") (pintype "passive"))
    )
    (net (code "277") (name "/NEW_276") (class "Default")
      (node (ref "JP1167") (pin "P$2") (pinfunction "1_P$2") (pintype "passive"))
      (node (ref "JP136") (pin "1") (pinfunction "1_1") (pintype "passive"))
    )
    (net (code "278") (name "/NEW_277") (class "Default")
      (node (ref "JP1168") (pin "P$2") (pinfunction "1_P$2") (pintype "passive"))
      (node (ref "JP126") (pin "1") (pinfunction "1_1") (pintype "passive"))
    )
    (net (code "279") (name "/NEW_278") (class "Default")
      (node (ref "JP116") (pin "1") (pinfunction "1_1") (pintype "passive"))
      (node (ref "JP1169") (pin "P$2") (pinfunction "1_P$2") (pintype "passive"))
    )
    (net (code "280") (name "/NEW_279") (class "Default")
      (node (ref "JP106") (pin "1") (pinfunction "1_1") (pintype "passive"))
      (node (ref "JP1170") (pin "P$2") (pinfunction "1_P$2") (pintype "passive"))
    )
    (net (code "281") (name "/NEW_280") (class "Default")
      (node (ref "JP1171") (pin "P$2") (pinfunction "1_P$2") (pintype "passive"))
      (node (ref "JP96") (pin "1") (pinfunction "1_1") (pintype "passive"))
    )
    (net (code "282") (name "/NEW_281") (class "Default")
      (node (ref "JP1172") (pin "P$2") (pinfunction "1_P$2") (pintype "passive"))
      (node (ref "JP86") (pin "1") (pinfunction "1_1") (pintype "passive"))
    )
    (net (code "283") (name "/NEW_282") (class "Default")
      (node (ref "JP1173") (pin "P$2") (pinfunction "1_P$2") (pintype "passive"))
      (node (ref "JP76") (pin "1") (pinfunction "1_1") (pintype "passive"))
    )
    (net (code "284") (name "/NEW_283") (class "Default")
      (node (ref "JP1174") (pin "P$2") (pinfunction "1_P$2") (pintype "passive"))
      (node (ref "JP66") (pin "1") (pinfunction "1_1") (pintype "passive"))
    )
    (net (code "285") (name "/NEW_284") (class "Default")
      (node (ref "JP1175") (pin "P$2") (pinfunction "1_P$2") (pintype "passive"))
      (node (ref "JP56") (pin "1") (pinfunction "1_1") (pintype "passive"))
    )
    (net (code "286") (name "/NEW_285") (class "Default")
      (node (ref "JP1176") (pin "P$2") (pinfunction "1_P$2") (pintype "passive"))
      (node (ref "JP46") (pin "1") (pinfunction "1_1") (pintype "passive"))
    )
    (net (code "287") (name "/NEW_286") (class "Default")
      (node (ref "JP1177") (pin "P$2") (pinfunction "1_P$2") (pintype "passive"))
      (node (ref "JP36") (pin "1") (pinfunction "1_1") (pintype "passive"))
    )
    (net (code "288") (name "/NEW_287") (class "Default")
      (node (ref "JP1178") (pin "P$2") (pinfunction "1_P$2") (pintype "passive"))
      (node (ref "JP26") (pin "1") (pinfunction "1_1") (pintype "passive"))
    )
    (net (code "289") (name "/NEW_288") (class "Default")
      (node (ref "JP1179") (pin "P$2") (pinfunction "1_P$2") (pintype "passive"))
      (node (ref "JP16") (pin "1") (pinfunction "1_1") (pintype "passive"))
    )
    (net (code "290") (name "/NEW_289") (class "Default")
      (node (ref "JP1180") (pin "P$2") (pinfunction "1_P$2") (pintype "passive"))
      (node (ref "JP6") (pin "1") (pinfunction "1_1") (pintype "passive"))
    )
    (net (code "291") (name "/NEW_290") (class "Default")
      (node (ref "JP1191") (pin "P$2") (pinfunction "1_P$2") (pintype "passive"))
      (node (ref "JP206") (pin "1") (pinfunction "1_1") (pintype "passive"))
    )
    (net (code "292") (name "/NEW_291") (class "Default")
      (node (ref "JP1192") (pin "P$2") (pinfunction "1_P$2") (pintype "passive"))
      (node (ref "JP216") (pin "1") (pinfunction "1_1") (pintype "passive"))
    )
    (net (code "293") (name "/NEW_292") (class "Default")
      (node (ref "JP1193") (pin "P$2") (pinfunction "1_P$2") (pintype "passive"))
      (node (ref "JP226") (pin "1") (pinfunction "1_1") (pintype "passive"))
    )
    (net (code "294") (name "/NEW_293") (class "Default")
      (node (ref "JP1194") (pin "P$2") (pinfunction "1_P$2") (pintype "passive"))
      (node (ref "JP236") (pin "1") (pinfunction "1_1") (pintype "passive"))
    )
    (net (code "295") (name "/NEW_294") (class "Default")
      (node (ref "JP1195") (pin "P$2") (pinfunction "1_P$2") (pintype "passive"))
      (node (ref "JP246") (pin "1") (pinfunction "1_1") (pintype "passive"))
    )
    (net (code "296") (name "/NEW_295") (class "Default")
      (node (ref "JP1196") (pin "P$2") (pinfunction "1_P$2") (pintype "passive"))
      (node (ref "JP256") (pin "1") (pinfunction "1_1") (pintype "passive"))
    )
    (net (code "297") (name "/NEW_296") (class "Default")
      (node (ref "JP1197") (pin "P$2") (pinfunction "1_P$2") (pintype "passive"))
      (node (ref "JP266") (pin "1") (pinfunction "1_1") (pintype "passive"))
    )
    (net (code "298") (name "/NEW_297") (class "Default")
      (node (ref "JP1198") (pin "P$2") (pinfunction "1_P$2") (pintype "passive"))
      (node (ref "JP276") (pin "1") (pinfunction "1_1") (pintype "passive"))
    )
    (net (code "299") (name "/NEW_298") (class "Default")
      (node (ref "JP1199") (pin "P$2") (pinfunction "1_P$2") (pintype "passive"))
      (node (ref "JP286") (pin "1") (pinfunction "1_1") (pintype "passive"))
    )
    (net (code "300") (name "/NEW_299") (class "Default")
      (node (ref "JP1200") (pin "P$2") (pinfunction "1_P$2") (pintype "passive"))
      (node (ref "JP296") (pin "1") (pinfunction "1_1") (pintype "passive"))
    )
  )
)
